# 7x7RGB-IR-J010129A.net
KiCad netlist of a schematic drawn in EAGLE
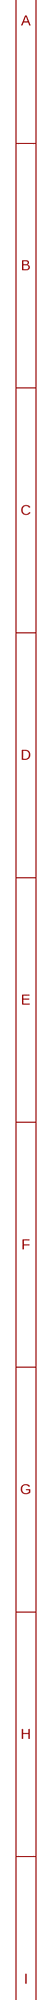
[diagram p0: schematic, sheet 1, part 1 of 2]
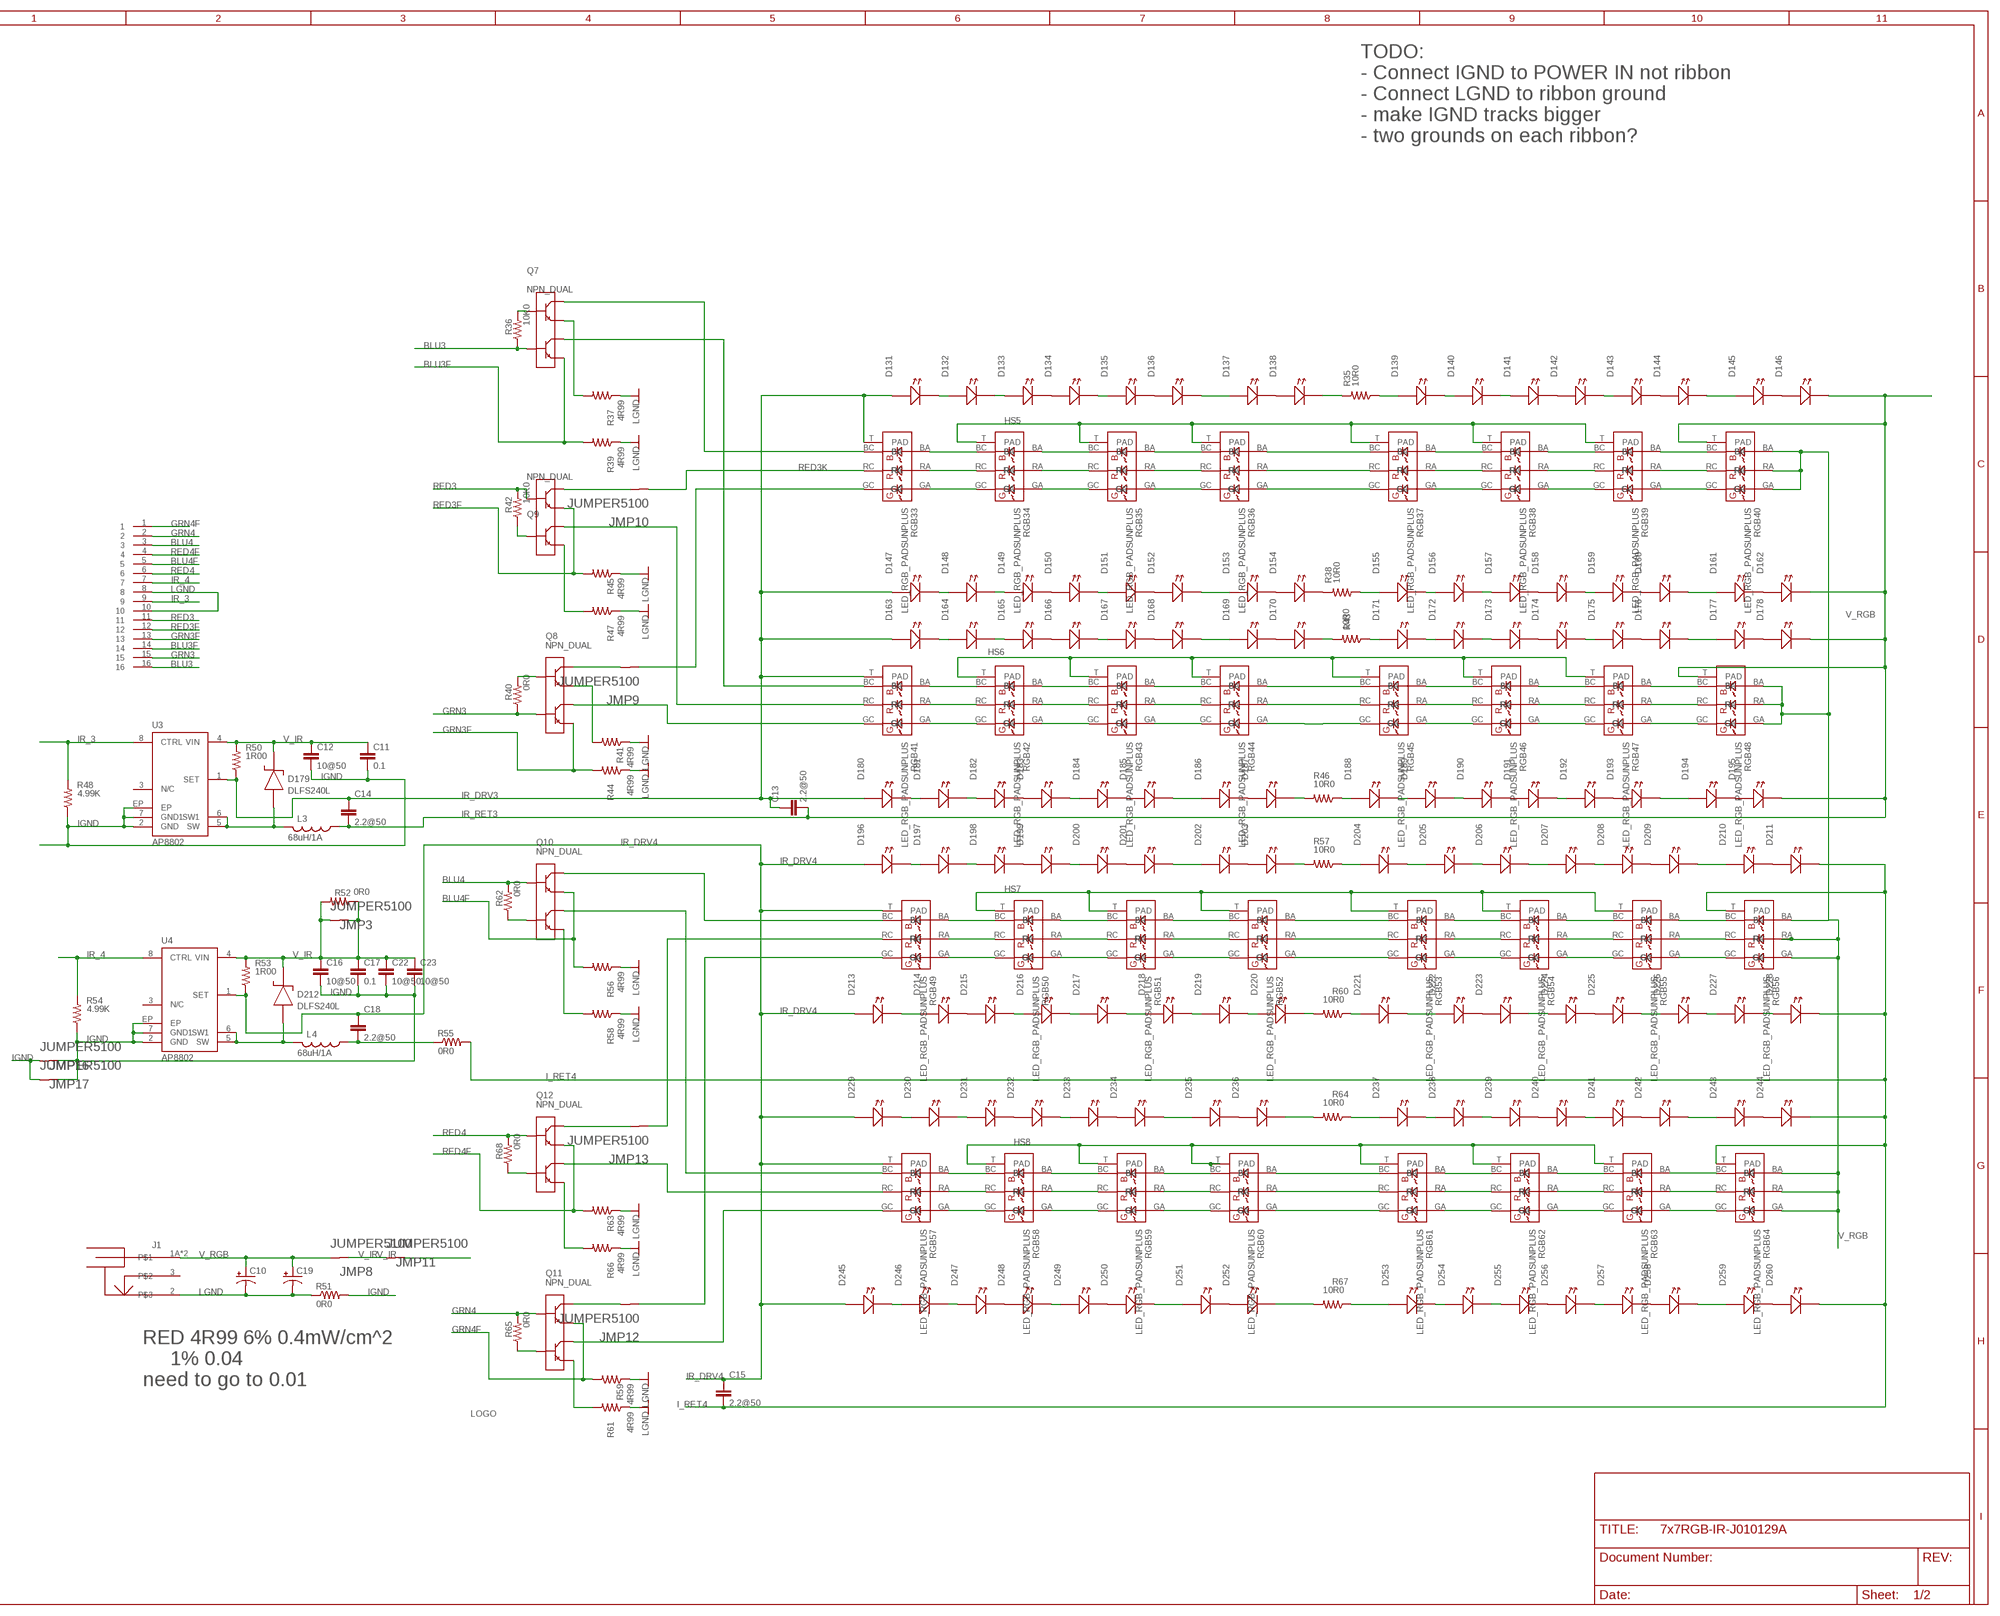
[diagram p1: schematic, sheet 1, part 2 of 2]
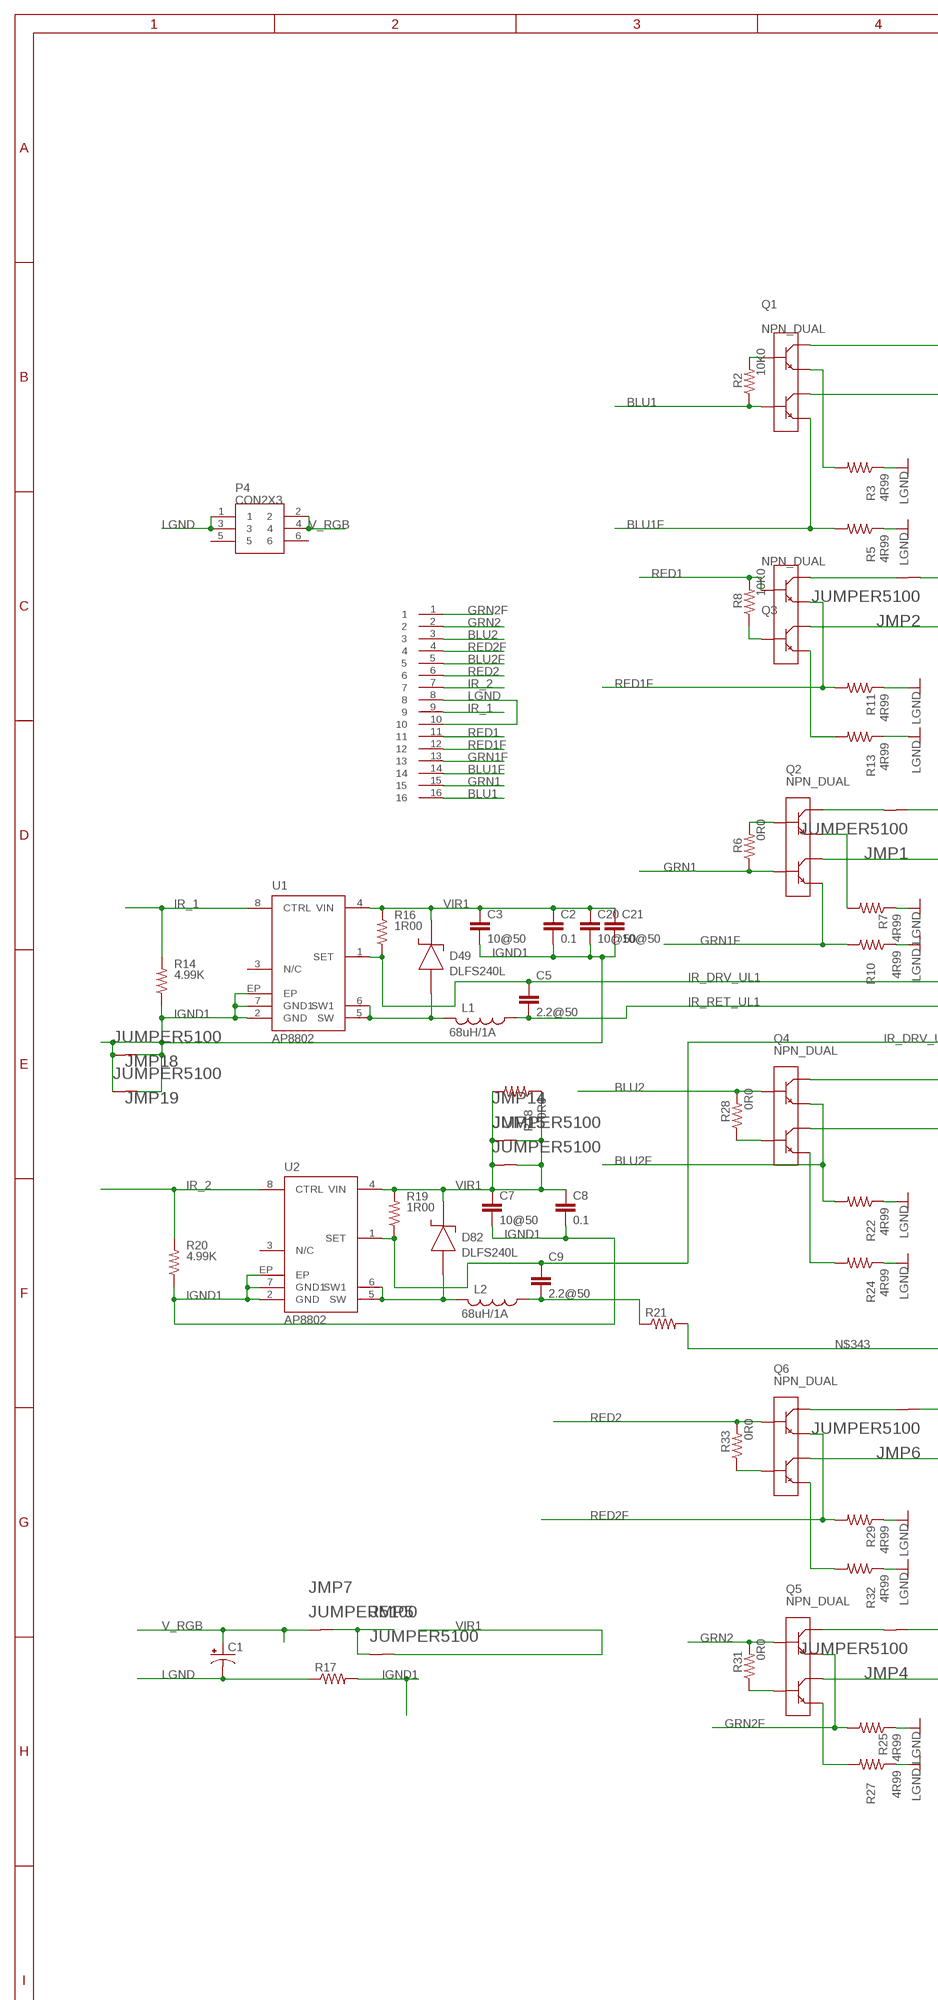
[diagram p2: schematic, sheet 2, part 1 of 2]
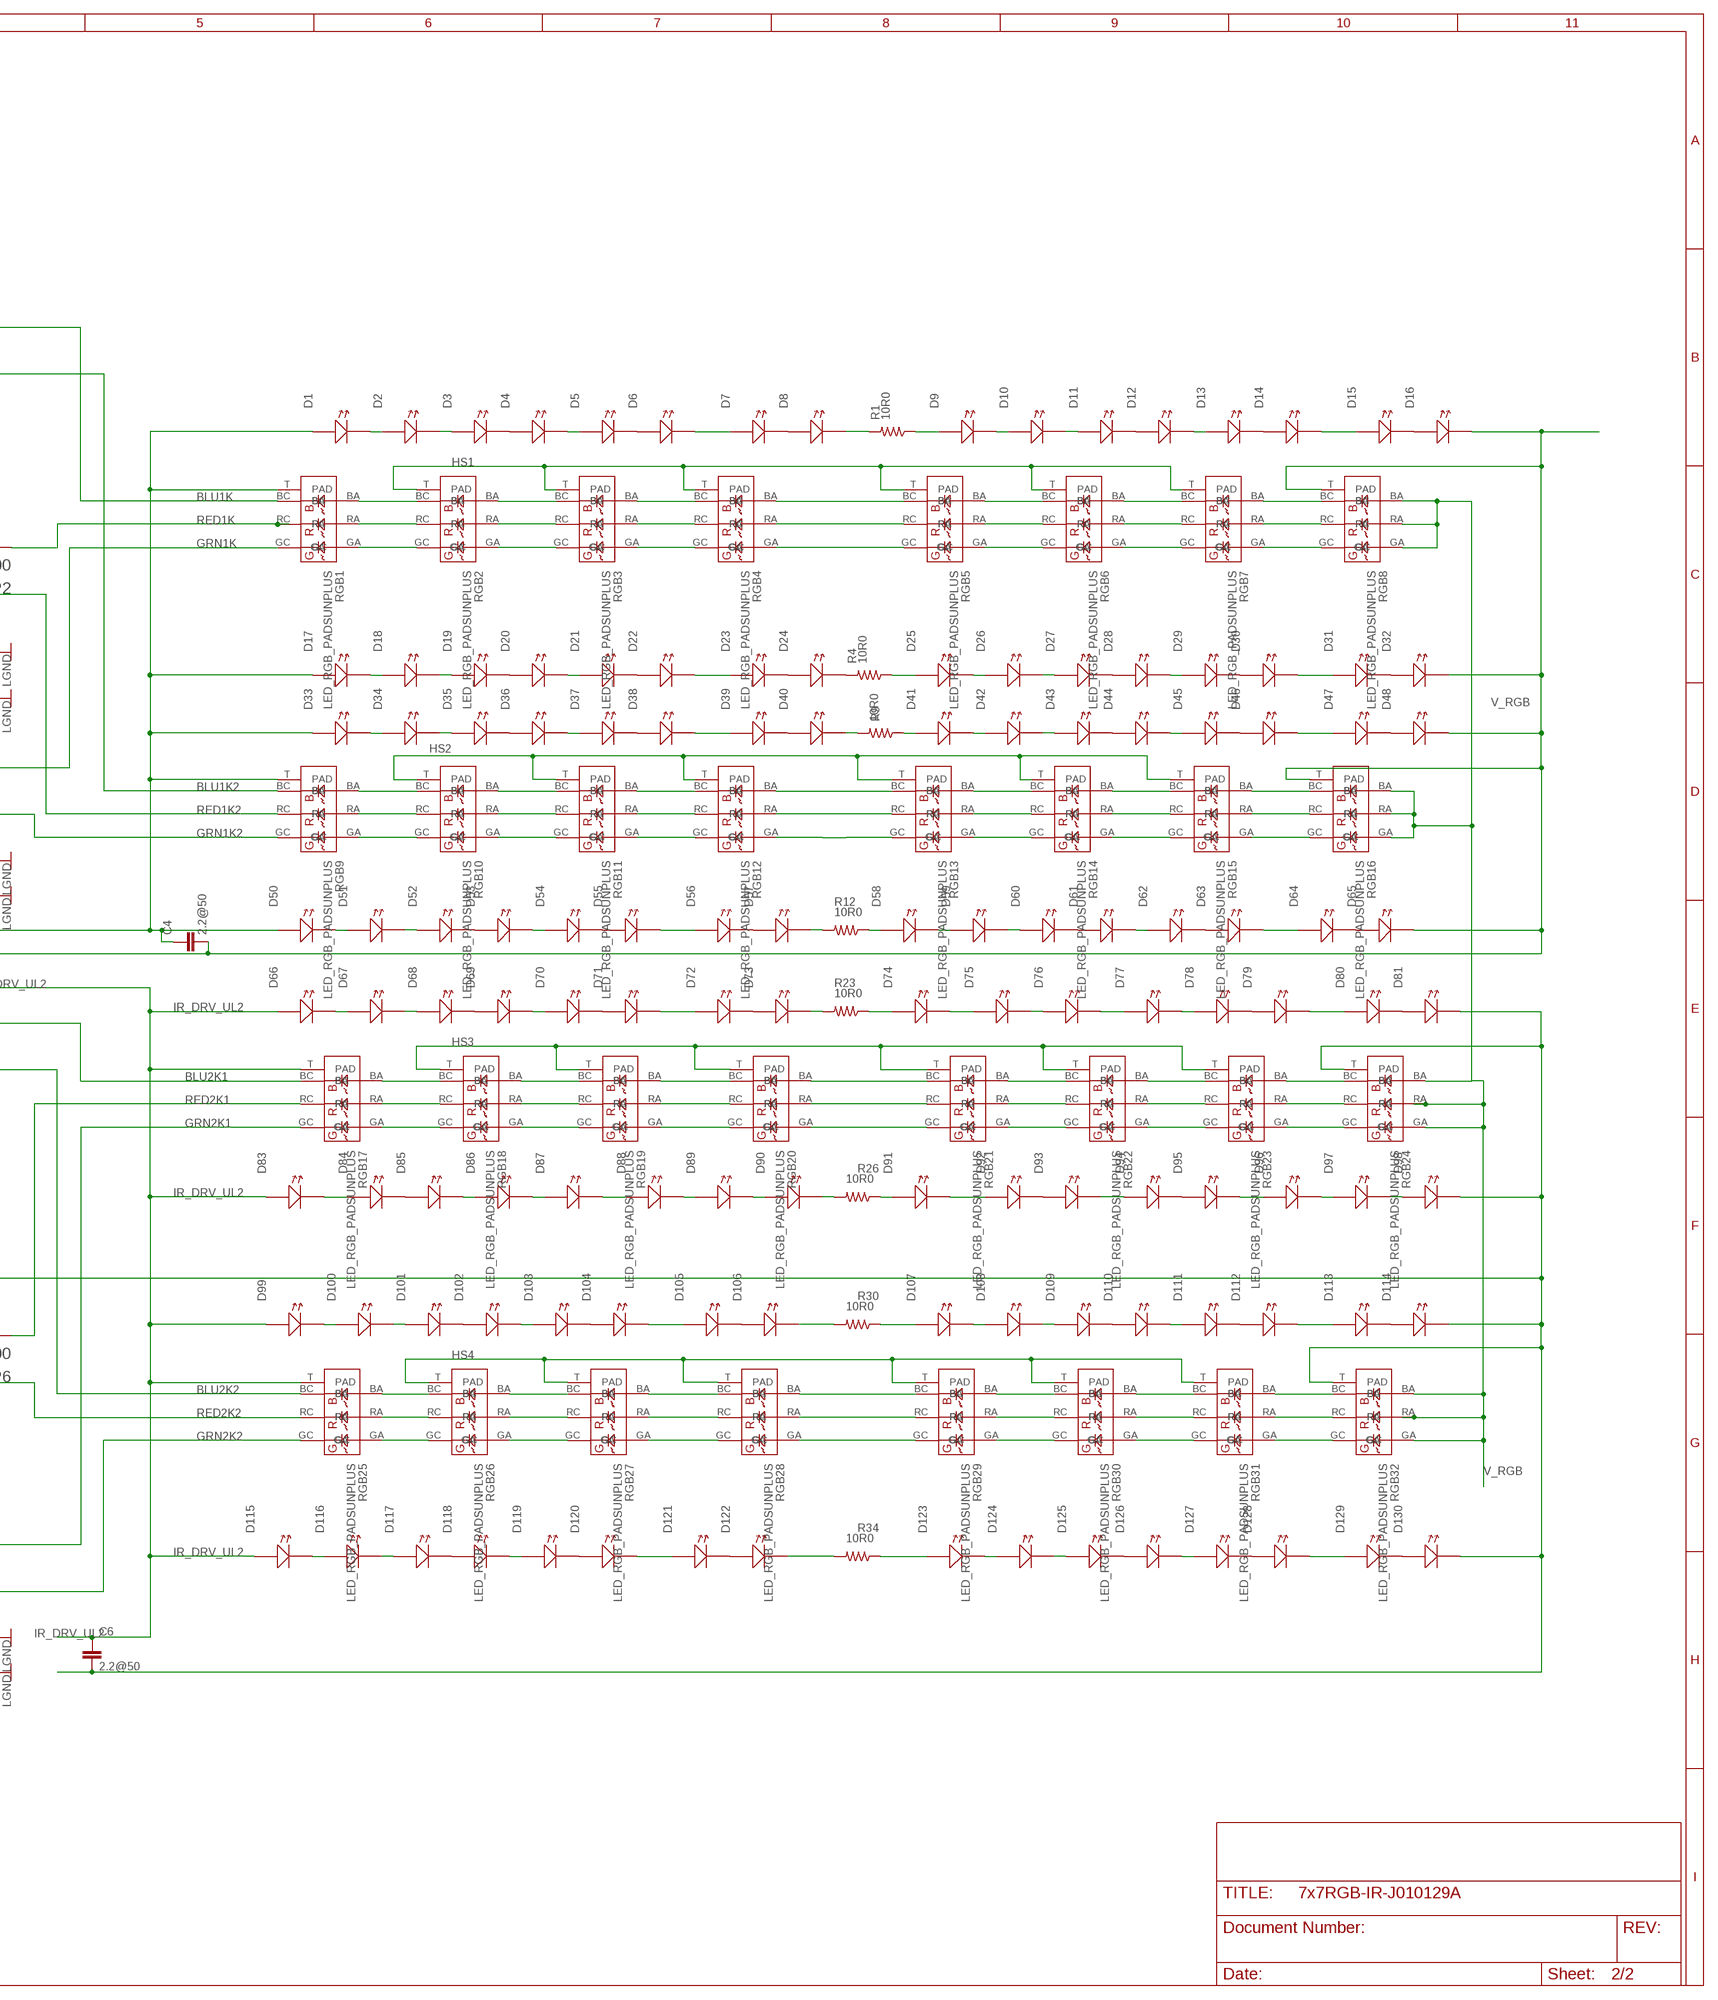
[diagram p3: schematic, sheet 2, part 2 of 2]

(export (version "E")
  (design (tool "Eeschema 10.0.6"))
  (components
    (comp (ref "C1")
      (value "CPOL-US153CLV-0810")
      (footprint "eagle-import:153CLV-0810")
      (libsource (lib "eagle-import") (part "CPOL-US153CLV-0810"))
    )
    (comp (ref "C2")
      (value "0.1")
      (footprint "eagle-import:0805S")
      (libsource (lib "eagle-import") (part "CAPS0805S"))
    )
    (comp (ref "C3")
      (value "10@50")
      (footprint "eagle-import:1210S")
      (libsource (lib "eagle-import") (part "CAPS1210S"))
    )
    (comp (ref "C4")
      (value "2.2@50")
      (footprint "eagle-import:1206S")
      (libsource (lib "eagle-import") (part "CAPS1206S"))
    )
    (comp (ref "C5")
      (value "2.2@50")
      (footprint "eagle-import:1206S")
      (libsource (lib "eagle-import") (part "CAPS1206S"))
    )
    (comp (ref "C6")
      (value "2.2@50")
      (footprint "eagle-import:1206S")
      (libsource (lib "eagle-import") (part "CAPS1206S"))
    )
    (comp (ref "C7")
      (value "10@50")
      (footprint "eagle-import:1210S")
      (libsource (lib "eagle-import") (part "CAPS1210S"))
    )
    (comp (ref "C8")
      (value "0.1")
      (footprint "eagle-import:0805S")
      (libsource (lib "eagle-import") (part "CAPS0805S"))
    )
    (comp (ref "C9")
      (value "2.2@50")
      (footprint "eagle-import:1206S")
      (libsource (lib "eagle-import") (part "CAPS1206S"))
    )
    (comp (ref "C20")
      (value "10@50")
      (footprint "eagle-import:1210S")
      (libsource (lib "eagle-import") (part "CAPS1210S"))
    )
    (comp (ref "C21")
      (value "10@50")
      (footprint "eagle-import:1210S")
      (libsource (lib "eagle-import") (part "CAPS1210S"))
    )
    (comp (ref "D1")
      (value "LEDLED_SFH4050")
      (footprint "eagle-import:LED_SFH4050")
      (libsource (lib "eagle-import") (part "LEDLED_SFH4050"))
    )
    (comp (ref "D2")
      (value "LEDLED_SFH4050")
      (footprint "eagle-import:LED_SFH4050")
      (libsource (lib "eagle-import") (part "LEDLED_SFH4050"))
    )
    (comp (ref "D3")
      (value "LEDLED_SFH4050")
      (footprint "eagle-import:LED_SFH4050")
      (libsource (lib "eagle-import") (part "LEDLED_SFH4050"))
    )
    (comp (ref "D4")
      (value "LEDLED_SFH4050")
      (footprint "eagle-import:LED_SFH4050")
      (libsource (lib "eagle-import") (part "LEDLED_SFH4050"))
    )
    (comp (ref "D5")
      (value "LEDLED_SFH4050")
      (footprint "eagle-import:LED_SFH4050")
      (libsource (lib "eagle-import") (part "LEDLED_SFH4050"))
    )
    (comp (ref "D6")
      (value "LEDLED_SFH4050")
      (footprint "eagle-import:LED_SFH4050")
      (libsource (lib "eagle-import") (part "LEDLED_SFH4050"))
    )
    (comp (ref "D7")
      (value "LEDLED_SFH4050")
      (footprint "eagle-import:LED_SFH4050")
      (libsource (lib "eagle-import") (part "LEDLED_SFH4050"))
    )
    (comp (ref "D8")
      (value "LEDLED_SFH4050")
      (footprint "eagle-import:LED_SFH4050")
      (libsource (lib "eagle-import") (part "LEDLED_SFH4050"))
    )
    (comp (ref "D9")
      (value "LEDLED_SFH4050")
      (footprint "eagle-import:LED_SFH4050")
      (libsource (lib "eagle-import") (part "LEDLED_SFH4050"))
    )
    (comp (ref "D10")
      (value "LEDLED_SFH4050")
      (footprint "eagle-import:LED_SFH4050")
      (libsource (lib "eagle-import") (part "LEDLED_SFH4050"))
    )
    (comp (ref "D11")
      (value "LEDLED_SFH4050")
      (footprint "eagle-import:LED_SFH4050")
      (libsource (lib "eagle-import") (part "LEDLED_SFH4050"))
    )
    (comp (ref "D12")
      (value "LEDLED_SFH4050")
      (footprint "eagle-import:LED_SFH4050")
      (libsource (lib "eagle-import") (part "LEDLED_SFH4050"))
    )
    (comp (ref "D13")
      (value "LEDLED_SFH4050")
      (footprint "eagle-import:LED_SFH4050")
      (libsource (lib "eagle-import") (part "LEDLED_SFH4050"))
    )
    (comp (ref "D14")
      (value "LEDLED_SFH4050")
      (footprint "eagle-import:LED_SFH4050")
      (libsource (lib "eagle-import") (part "LEDLED_SFH4050"))
    )
    (comp (ref "D15")
      (value "LEDLED_SFH4050")
      (footprint "eagle-import:LED_SFH4050")
      (libsource (lib "eagle-import") (part "LEDLED_SFH4050"))
    )
    (comp (ref "D16")
      (value "LEDLED_SFH4050")
      (footprint "eagle-import:LED_SFH4050")
      (libsource (lib "eagle-import") (part "LEDLED_SFH4050"))
    )
    (comp (ref "D17")
      (value "LEDLED_SFH4050")
      (footprint "eagle-import:LED_SFH4050")
      (libsource (lib "eagle-import") (part "LEDLED_SFH4050"))
    )
    (comp (ref "D18")
      (value "LEDLED_SFH4050")
      (footprint "eagle-import:LED_SFH4050")
      (libsource (lib "eagle-import") (part "LEDLED_SFH4050"))
    )
    (comp (ref "D19")
      (value "LEDLED_SFH4050")
      (footprint "eagle-import:LED_SFH4050")
      (libsource (lib "eagle-import") (part "LEDLED_SFH4050"))
    )
    (comp (ref "D20")
      (value "LEDLED_SFH4050")
      (footprint "eagle-import:LED_SFH4050")
      (libsource (lib "eagle-import") (part "LEDLED_SFH4050"))
    )
    (comp (ref "D21")
      (value "LEDLED_SFH4050")
      (footprint "eagle-import:LED_SFH4050")
      (libsource (lib "eagle-import") (part "LEDLED_SFH4050"))
    )
    (comp (ref "D22")
      (value "LEDLED_SFH4050")
      (footprint "eagle-import:LED_SFH4050")
      (libsource (lib "eagle-import") (part "LEDLED_SFH4050"))
    )
    (comp (ref "D23")
      (value "LEDLED_SFH4050")
      (footprint "eagle-import:LED_SFH4050")
      (libsource (lib "eagle-import") (part "LEDLED_SFH4050"))
    )
    (comp (ref "D24")
      (value "LEDLED_SFH4050")
      (footprint "eagle-import:LED_SFH4050")
      (libsource (lib "eagle-import") (part "LEDLED_SFH4050"))
    )
    (comp (ref "D25")
      (value "LEDLED_SFH4050")
      (footprint "eagle-import:LED_SFH4050")
      (libsource (lib "eagle-import") (part "LEDLED_SFH4050"))
    )
    (comp (ref "D26")
      (value "LEDLED_SFH4050")
      (footprint "eagle-import:LED_SFH4050")
      (libsource (lib "eagle-import") (part "LEDLED_SFH4050"))
    )
    (comp (ref "D27")
      (value "LEDLED_SFH4050")
      (footprint "eagle-import:LED_SFH4050")
      (libsource (lib "eagle-import") (part "LEDLED_SFH4050"))
    )
    (comp (ref "D28")
      (value "LEDLED_SFH4050")
      (footprint "eagle-import:LED_SFH4050")
      (libsource (lib "eagle-import") (part "LEDLED_SFH4050"))
    )
    (comp (ref "D29")
      (value "LEDLED_SFH4050")
      (footprint "eagle-import:LED_SFH4050")
      (libsource (lib "eagle-import") (part "LEDLED_SFH4050"))
    )
    (comp (ref "D30")
      (value "LEDLED_SFH4050")
      (footprint "eagle-import:LED_SFH4050")
      (libsource (lib "eagle-import") (part "LEDLED_SFH4050"))
    )
    (comp (ref "D31")
      (value "LEDLED_SFH4050")
      (footprint "eagle-import:LED_SFH4050")
      (libsource (lib "eagle-import") (part "LEDLED_SFH4050"))
    )
    (comp (ref "D32")
      (value "LEDLED_SFH4050")
      (footprint "eagle-import:LED_SFH4050")
      (libsource (lib "eagle-import") (part "LEDLED_SFH4050"))
    )
    (comp (ref "D33")
      (value "LEDLED_SFH4050")
      (footprint "eagle-import:LED_SFH4050")
      (libsource (lib "eagle-import") (part "LEDLED_SFH4050"))
    )
    (comp (ref "D34")
      (value "LEDLED_SFH4050")
      (footprint "eagle-import:LED_SFH4050")
      (libsource (lib "eagle-import") (part "LEDLED_SFH4050"))
    )
    (comp (ref "D35")
      (value "LEDLED_SFH4050")
      (footprint "eagle-import:LED_SFH4050")
      (libsource (lib "eagle-import") (part "LEDLED_SFH4050"))
    )
    (comp (ref "D36")
      (value "LEDLED_SFH4050")
      (footprint "eagle-import:LED_SFH4050")
      (libsource (lib "eagle-import") (part "LEDLED_SFH4050"))
    )
    (comp (ref "D37")
      (value "LEDLED_SFH4050")
      (footprint "eagle-import:LED_SFH4050")
      (libsource (lib "eagle-import") (part "LEDLED_SFH4050"))
    )
    (comp (ref "D38")
      (value "LEDLED_SFH4050")
      (footprint "eagle-import:LED_SFH4050")
      (libsource (lib "eagle-import") (part "LEDLED_SFH4050"))
    )
    (comp (ref "D39")
      (value "LEDLED_SFH4050")
      (footprint "eagle-import:LED_SFH4050")
      (libsource (lib "eagle-import") (part "LEDLED_SFH4050"))
    )
    (comp (ref "D40")
      (value "LEDLED_SFH4050")
      (footprint "eagle-import:LED_SFH4050")
      (libsource (lib "eagle-import") (part "LEDLED_SFH4050"))
    )
    (comp (ref "D41")
      (value "LEDLED_SFH4050")
      (footprint "eagle-import:LED_SFH4050")
      (libsource (lib "eagle-import") (part "LEDLED_SFH4050"))
    )
    (comp (ref "D42")
      (value "LEDLED_SFH4050")
      (footprint "eagle-import:LED_SFH4050")
      (libsource (lib "eagle-import") (part "LEDLED_SFH4050"))
    )
    (comp (ref "D43")
      (value "LEDLED_SFH4050")
      (footprint "eagle-import:LED_SFH4050")
      (libsource (lib "eagle-import") (part "LEDLED_SFH4050"))
    )
    (comp (ref "D44")
      (value "LEDLED_SFH4050")
      (footprint "eagle-import:LED_SFH4050")
      (libsource (lib "eagle-import") (part "LEDLED_SFH4050"))
    )
    (comp (ref "D45")
      (value "LEDLED_SFH4050")
      (footprint "eagle-import:LED_SFH4050")
      (libsource (lib "eagle-import") (part "LEDLED_SFH4050"))
    )
    (comp (ref "D46")
      (value "LEDLED_SFH4050")
      (footprint "eagle-import:LED_SFH4050")
      (libsource (lib "eagle-import") (part "LEDLED_SFH4050"))
    )
    (comp (ref "D47")
      (value "LEDLED_SFH4050")
      (footprint "eagle-import:LED_SFH4050")
      (libsource (lib "eagle-import") (part "LEDLED_SFH4050"))
    )
    (comp (ref "D48")
      (value "LEDLED_SFH4050")
      (footprint "eagle-import:LED_SFH4050")
      (libsource (lib "eagle-import") (part "LEDLED_SFH4050"))
    )
    (comp (ref "D49")
      (value "DLFS240L")
      (footprint "eagle-import:PWRDI-123")
      (libsource (lib "eagle-import") (part "DIODE_SCHOTTKYPWRDI-123"))
    )
    (comp (ref "D50")
      (value "LEDLED_SFH4050")
      (footprint "eagle-import:LED_SFH4050")
      (libsource (lib "eagle-import") (part "LEDLED_SFH4050"))
    )
    (comp (ref "D51")
      (value "LEDLED_SFH4050")
      (footprint "eagle-import:LED_SFH4050")
      (libsource (lib "eagle-import") (part "LEDLED_SFH4050"))
    )
    (comp (ref "D52")
      (value "LEDLED_SFH4050")
      (footprint "eagle-import:LED_SFH4050")
      (libsource (lib "eagle-import") (part "LEDLED_SFH4050"))
    )
    (comp (ref "D53")
      (value "LEDLED_SFH4050")
      (footprint "eagle-import:LED_SFH4050")
      (libsource (lib "eagle-import") (part "LEDLED_SFH4050"))
    )
    (comp (ref "D54")
      (value "LEDLED_SFH4050")
      (footprint "eagle-import:LED_SFH4050")
      (libsource (lib "eagle-import") (part "LEDLED_SFH4050"))
    )
    (comp (ref "D55")
      (value "LEDLED_SFH4050")
      (footprint "eagle-import:LED_SFH4050")
      (libsource (lib "eagle-import") (part "LEDLED_SFH4050"))
    )
    (comp (ref "D56")
      (value "LEDLED_SFH4050")
      (footprint "eagle-import:LED_SFH4050")
      (libsource (lib "eagle-import") (part "LEDLED_SFH4050"))
    )
    (comp (ref "D57")
      (value "LEDLED_SFH4050")
      (footprint "eagle-import:LED_SFH4050")
      (libsource (lib "eagle-import") (part "LEDLED_SFH4050"))
    )
    (comp (ref "D58")
      (value "LEDLED_SFH4050")
      (footprint "eagle-import:LED_SFH4050")
      (libsource (lib "eagle-import") (part "LEDLED_SFH4050"))
    )
    (comp (ref "D59")
      (value "LEDLED_SFH4050")
      (footprint "eagle-import:LED_SFH4050")
      (libsource (lib "eagle-import") (part "LEDLED_SFH4050"))
    )
    (comp (ref "D60")
      (value "LEDLED_SFH4050")
      (footprint "eagle-import:LED_SFH4050")
      (libsource (lib "eagle-import") (part "LEDLED_SFH4050"))
    )
    (comp (ref "D61")
      (value "LEDLED_SFH4050")
      (footprint "eagle-import:LED_SFH4050")
      (libsource (lib "eagle-import") (part "LEDLED_SFH4050"))
    )
    (comp (ref "D62")
      (value "LEDLED_SFH4050")
      (footprint "eagle-import:LED_SFH4050")
      (libsource (lib "eagle-import") (part "LEDLED_SFH4050"))
    )
    (comp (ref "D63")
      (value "LEDLED_SFH4050")
      (footprint "eagle-import:LED_SFH4050")
      (libsource (lib "eagle-import") (part "LEDLED_SFH4050"))
    )
    (comp (ref "D64")
      (value "LEDLED_SFH4050")
      (footprint "eagle-import:LED_SFH4050")
      (libsource (lib "eagle-import") (part "LEDLED_SFH4050"))
    )
    (comp (ref "D65")
      (value "LEDLED_SFH4050")
      (footprint "eagle-import:LED_SFH4050")
      (libsource (lib "eagle-import") (part "LEDLED_SFH4050"))
    )
    (comp (ref "D66")
      (value "LEDLED_SFH4050")
      (footprint "eagle-import:LED_SFH4050")
      (libsource (lib "eagle-import") (part "LEDLED_SFH4050"))
    )
    (comp (ref "D67")
      (value "LEDLED_SFH4050")
      (footprint "eagle-import:LED_SFH4050")
      (libsource (lib "eagle-import") (part "LEDLED_SFH4050"))
    )
    (comp (ref "D68")
      (value "LEDLED_SFH4050")
      (footprint "eagle-import:LED_SFH4050")
      (libsource (lib "eagle-import") (part "LEDLED_SFH4050"))
    )
    (comp (ref "D69")
      (value "LEDLED_SFH4050")
      (footprint "eagle-import:LED_SFH4050")
      (libsource (lib "eagle-import") (part "LEDLED_SFH4050"))
    )
    (comp (ref "D70")
      (value "LEDLED_SFH4050")
      (footprint "eagle-import:LED_SFH4050")
      (libsource (lib "eagle-import") (part "LEDLED_SFH4050"))
    )
    (comp (ref "D71")
      (value "LEDLED_SFH4050")
      (footprint "eagle-import:LED_SFH4050")
      (libsource (lib "eagle-import") (part "LEDLED_SFH4050"))
    )
    (comp (ref "D72")
      (value "LEDLED_SFH4050")
      (footprint "eagle-import:LED_SFH4050")
      (libsource (lib "eagle-import") (part "LEDLED_SFH4050"))
    )
    (comp (ref "D73")
      (value "LEDLED_SFH4050")
      (footprint "eagle-import:LED_SFH4050")
      (libsource (lib "eagle-import") (part "LEDLED_SFH4050"))
    )
    (comp (ref "D74")
      (value "LEDLED_SFH4050")
      (footprint "eagle-import:LED_SFH4050")
      (libsource (lib "eagle-import") (part "LEDLED_SFH4050"))
    )
    (comp (ref "D75")
      (value "LEDLED_SFH4050")
      (footprint "eagle-import:LED_SFH4050")
      (libsource (lib "eagle-import") (part "LEDLED_SFH4050"))
    )
    (comp (ref "D76")
      (value "LEDLED_SFH4050")
      (footprint "eagle-import:LED_SFH4050")
      (libsource (lib "eagle-import") (part "LEDLED_SFH4050"))
    )
    (comp (ref "D77")
      (value "LEDLED_SFH4050")
      (footprint "eagle-import:LED_SFH4050")
      (libsource (lib "eagle-import") (part "LEDLED_SFH4050"))
    )
    (comp (ref "D78")
      (value "LEDLED_SFH4050")
      (footprint "eagle-import:LED_SFH4050")
      (libsource (lib "eagle-import") (part "LEDLED_SFH4050"))
    )
    (comp (ref "D79")
      (value "LEDLED_SFH4050")
      (footprint "eagle-import:LED_SFH4050")
      (libsource (lib "eagle-import") (part "LEDLED_SFH4050"))
    )
    (comp (ref "D80")
      (value "LEDLED_SFH4050")
      (footprint "eagle-import:LED_SFH4050")
      (libsource (lib "eagle-import") (part "LEDLED_SFH4050"))
    )
    (comp (ref "D81")
      (value "LEDLED_SFH4050")
      (footprint "eagle-import:LED_SFH4050")
      (libsource (lib "eagle-import") (part "LEDLED_SFH4050"))
    )
    (comp (ref "D82")
      (value "DLFS240L")
      (footprint "eagle-import:PWRDI-123")
      (libsource (lib "eagle-import") (part "DIODE_SCHOTTKYPWRDI-123"))
    )
    (comp (ref "D83")
      (value "LEDLED_SFH4050")
      (footprint "eagle-import:LED_SFH4050")
      (libsource (lib "eagle-import") (part "LEDLED_SFH4050"))
    )
    (comp (ref "D84")
      (value "LEDLED_SFH4050")
      (footprint "eagle-import:LED_SFH4050")
      (libsource (lib "eagle-import") (part "LEDLED_SFH4050"))
    )
    (comp (ref "D85")
      (value "LEDLED_SFH4050")
      (footprint "eagle-import:LED_SFH4050")
      (libsource (lib "eagle-import") (part "LEDLED_SFH4050"))
    )
    (comp (ref "D86")
      (value "LEDLED_SFH4050")
      (footprint "eagle-import:LED_SFH4050")
      (libsource (lib "eagle-import") (part "LEDLED_SFH4050"))
    )
    (comp (ref "D87")
      (value "LEDLED_SFH4050")
      (footprint "eagle-import:LED_SFH4050")
      (libsource (lib "eagle-import") (part "LEDLED_SFH4050"))
    )
    (comp (ref "D88")
      (value "LEDLED_SFH4050")
      (footprint "eagle-import:LED_SFH4050")
      (libsource (lib "eagle-import") (part "LEDLED_SFH4050"))
    )
    (comp (ref "D89")
      (value "LEDLED_SFH4050")
      (footprint "eagle-import:LED_SFH4050")
      (libsource (lib "eagle-import") (part "LEDLED_SFH4050"))
    )
    (comp (ref "D90")
      (value "LEDLED_SFH4050")
      (footprint "eagle-import:LED_SFH4050")
      (libsource (lib "eagle-import") (part "LEDLED_SFH4050"))
    )
    (comp (ref "D91")
      (value "LEDLED_SFH4050")
      (footprint "eagle-import:LED_SFH4050")
      (libsource (lib "eagle-import") (part "LEDLED_SFH4050"))
    )
    (comp (ref "D92")
      (value "LEDLED_SFH4050")
      (footprint "eagle-import:LED_SFH4050")
      (libsource (lib "eagle-import") (part "LEDLED_SFH4050"))
    )
    (comp (ref "D93")
      (value "LEDLED_SFH4050")
      (footprint "eagle-import:LED_SFH4050")
      (libsource (lib "eagle-import") (part "LEDLED_SFH4050"))
    )
    (comp (ref "D94")
      (value "LEDLED_SFH4050")
      (footprint "eagle-import:LED_SFH4050")
      (libsource (lib "eagle-import") (part "LEDLED_SFH4050"))
    )
    (comp (ref "D95")
      (value "LEDLED_SFH4050")
      (footprint "eagle-import:LED_SFH4050")
      (libsource (lib "eagle-import") (part "LEDLED_SFH4050"))
    )
    (comp (ref "D96")
      (value "LEDLED_SFH4050")
      (footprint "eagle-import:LED_SFH4050")
      (libsource (lib "eagle-import") (part "LEDLED_SFH4050"))
    )
    (comp (ref "D97")
      (value "LEDLED_SFH4050")
      (footprint "eagle-import:LED_SFH4050")
      (libsource (lib "eagle-import") (part "LEDLED_SFH4050"))
    )
    (comp (ref "D98")
      (value "LEDLED_SFH4050")
      (footprint "eagle-import:LED_SFH4050")
      (libsource (lib "eagle-import") (part "LEDLED_SFH4050"))
    )
    (comp (ref "D99")
      (value "LEDLED_SFH4050")
      (footprint "eagle-import:LED_SFH4050")
      (libsource (lib "eagle-import") (part "LEDLED_SFH4050"))
    )
    (comp (ref "D100")
      (value "LEDLED_SFH4050")
      (footprint "eagle-import:LED_SFH4050")
      (libsource (lib "eagle-import") (part "LEDLED_SFH4050"))
    )
    (comp (ref "D101")
      (value "LEDLED_SFH4050")
      (footprint "eagle-import:LED_SFH4050")
      (libsource (lib "eagle-import") (part "LEDLED_SFH4050"))
    )
    (comp (ref "D102")
      (value "LEDLED_SFH4050")
      (footprint "eagle-import:LED_SFH4050")
      (libsource (lib "eagle-import") (part "LEDLED_SFH4050"))
    )
    (comp (ref "D103")
      (value "LEDLED_SFH4050")
      (footprint "eagle-import:LED_SFH4050")
      (libsource (lib "eagle-import") (part "LEDLED_SFH4050"))
    )
    (comp (ref "D104")
      (value "LEDLED_SFH4050")
      (footprint "eagle-import:LED_SFH4050")
      (libsource (lib "eagle-import") (part "LEDLED_SFH4050"))
    )
    (comp (ref "D105")
      (value "LEDLED_SFH4050")
      (footprint "eagle-import:LED_SFH4050")
      (libsource (lib "eagle-import") (part "LEDLED_SFH4050"))
    )
    (comp (ref "D106")
      (value "LEDLED_SFH4050")
      (footprint "eagle-import:LED_SFH4050")
      (libsource (lib "eagle-import") (part "LEDLED_SFH4050"))
    )
    (comp (ref "D107")
      (value "LEDLED_SFH4050")
      (footprint "eagle-import:LED_SFH4050")
      (libsource (lib "eagle-import") (part "LEDLED_SFH4050"))
    )
    (comp (ref "D108")
      (value "LEDLED_SFH4050")
      (footprint "eagle-import:LED_SFH4050")
      (libsource (lib "eagle-import") (part "LEDLED_SFH4050"))
    )
    (comp (ref "D109")
      (value "LEDLED_SFH4050")
      (footprint "eagle-import:LED_SFH4050")
      (libsource (lib "eagle-import") (part "LEDLED_SFH4050"))
    )
    (comp (ref "D110")
      (value "LEDLED_SFH4050")
      (footprint "eagle-import:LED_SFH4050")
      (libsource (lib "eagle-import") (part "LEDLED_SFH4050"))
    )
    (comp (ref "D111")
      (value "LEDLED_SFH4050")
      (footprint "eagle-import:LED_SFH4050")
      (libsource (lib "eagle-import") (part "LEDLED_SFH4050"))
    )
    (comp (ref "D112")
      (value "LEDLED_SFH4050")
      (footprint "eagle-import:LED_SFH4050")
      (libsource (lib "eagle-import") (part "LEDLED_SFH4050"))
    )
    (comp (ref "D113")
      (value "LEDLED_SFH4050")
      (footprint "eagle-import:LED_SFH4050")
      (libsource (lib "eagle-import") (part "LEDLED_SFH4050"))
    )
    (comp (ref "D114")
      (value "LEDLED_SFH4050")
      (footprint "eagle-import:LED_SFH4050")
      (libsource (lib "eagle-import") (part "LEDLED_SFH4050"))
    )
    (comp (ref "D115")
      (value "LEDLED_SFH4050")
      (footprint "eagle-import:LED_SFH4050")
      (libsource (lib "eagle-import") (part "LEDLED_SFH4050"))
    )
    (comp (ref "D116")
      (value "LEDLED_SFH4050")
      (footprint "eagle-import:LED_SFH4050")
      (libsource (lib "eagle-import") (part "LEDLED_SFH4050"))
    )
    (comp (ref "D117")
      (value "LEDLED_SFH4050")
      (footprint "eagle-import:LED_SFH4050")
      (libsource (lib "eagle-import") (part "LEDLED_SFH4050"))
    )
    (comp (ref "D118")
      (value "LEDLED_SFH4050")
      (footprint "eagle-import:LED_SFH4050")
      (libsource (lib "eagle-import") (part "LEDLED_SFH4050"))
    )
    (comp (ref "D119")
      (value "LEDLED_SFH4050")
      (footprint "eagle-import:LED_SFH4050")
      (libsource (lib "eagle-import") (part "LEDLED_SFH4050"))
    )
    (comp (ref "D120")
      (value "LEDLED_SFH4050")
      (footprint "eagle-import:LED_SFH4050")
      (libsource (lib "eagle-import") (part "LEDLED_SFH4050"))
    )
    (comp (ref "D121")
      (value "LEDLED_SFH4050")
      (footprint "eagle-import:LED_SFH4050")
      (libsource (lib "eagle-import") (part "LEDLED_SFH4050"))
    )
    (comp (ref "D122")
      (value "LEDLED_SFH4050")
      (footprint "eagle-import:LED_SFH4050")
      (libsource (lib "eagle-import") (part "LEDLED_SFH4050"))
    )
    (comp (ref "D123")
      (value "LEDLED_SFH4050")
      (footprint "eagle-import:LED_SFH4050")
      (libsource (lib "eagle-import") (part "LEDLED_SFH4050"))
    )
    (comp (ref "D124")
      (value "LEDLED_SFH4050")
      (footprint "eagle-import:LED_SFH4050")
      (libsource (lib "eagle-import") (part "LEDLED_SFH4050"))
    )
    (comp (ref "D125")
      (value "LEDLED_SFH4050")
      (footprint "eagle-import:LED_SFH4050")
      (libsource (lib "eagle-import") (part "LEDLED_SFH4050"))
    )
    (comp (ref "D126")
      (value "LEDLED_SFH4050")
      (footprint "eagle-import:LED_SFH4050")
      (libsource (lib "eagle-import") (part "LEDLED_SFH4050"))
    )
    (comp (ref "D127")
      (value "LEDLED_SFH4050")
      (footprint "eagle-import:LED_SFH4050")
      (libsource (lib "eagle-import") (part "LEDLED_SFH4050"))
    )
    (comp (ref "D128")
      (value "LEDLED_SFH4050")
      (footprint "eagle-import:LED_SFH4050")
      (libsource (lib "eagle-import") (part "LEDLED_SFH4050"))
    )
    (comp (ref "D129")
      (value "LEDLED_SFH4050")
      (footprint "eagle-import:LED_SFH4050")
      (libsource (lib "eagle-import") (part "LEDLED_SFH4050"))
    )
    (comp (ref "D130")
      (value "LEDLED_SFH4050")
      (footprint "eagle-import:LED_SFH4050")
      (libsource (lib "eagle-import") (part "LEDLED_SFH4050"))
    )
    (comp (ref "JMP1")
      (value "JUMPER5100")
      (footprint "eagle-import:5100")
      (libsource (lib "eagle-import") (part "JUMPER5100"))
    )
    (comp (ref "JMP2")
      (value "JUMPER5100")
      (footprint "eagle-import:5100")
      (libsource (lib "eagle-import") (part "JUMPER5100"))
    )
    (comp (ref "JMP4")
      (value "JUMPER5100")
      (footprint "eagle-import:5100")
      (libsource (lib "eagle-import") (part "JUMPER5100"))
    )
    (comp (ref "JMP5")
      (value "JUMPER5100")
      (footprint "eagle-import:5100")
      (libsource (lib "eagle-import") (part "JUMPER5100"))
    )
    (comp (ref "JMP6")
      (value "JUMPER5100")
      (footprint "eagle-import:5100")
      (libsource (lib "eagle-import") (part "JUMPER5100"))
    )
    (comp (ref "JMP7")
      (value "JUMPER5100")
      (footprint "eagle-import:5100")
      (libsource (lib "eagle-import") (part "JUMPER5100"))
    )
    (comp (ref "JMP14")
      (value "JUMPER5100")
      (footprint "eagle-import:5100")
      (libsource (lib "eagle-import") (part "JUMPER5100"))
    )
    (comp (ref "JMP15")
      (value "JUMPER5100")
      (footprint "eagle-import:5100")
      (libsource (lib "eagle-import") (part "JUMPER5100"))
    )
    (comp (ref "JMP18")
      (value "JUMPER5100")
      (footprint "eagle-import:5100")
      (libsource (lib "eagle-import") (part "JUMPER5100"))
    )
    (comp (ref "JMP19")
      (value "JUMPER5100")
      (footprint "eagle-import:5100")
      (libsource (lib "eagle-import") (part "JUMPER5100"))
    )
    (comp (ref "L1")
      (value "68uH/1A")
      (footprint "eagle-import:SRU8043")
      (libsource (lib "eagle-import") (part "INDUCTOR_SMSRU8043"))
    )
    (comp (ref "L2")
      (value "68uH/1A")
      (footprint "eagle-import:SRU8043")
      (libsource (lib "eagle-import") (part "INDUCTOR_SMSRU8043"))
    )
    (comp (ref "P1")
      (value "CON162X8SM-SMALL")
      (footprint "eagle-import:HEADER2X8_SM_SMALL")
      (libsource (lib "eagle-import") (part "CON162X8SM-SMALL"))
    )
    (comp (ref "P4")
      (value "CON2X3")
      (footprint "eagle-import:2X3_SHROUDED_SMT")
      (libsource (lib "eagle-import") (part "CON2X3"))
    )
    (comp (ref "Q1")
      (value "NPN_DUAL")
      (footprint "eagle-import:LFPAK56D")
      (libsource (lib "eagle-import") (part "NPN_DUAL"))
    )
    (comp (ref "Q2")
      (value "NPN_DUAL")
      (footprint "eagle-import:LFPAK56D")
      (libsource (lib "eagle-import") (part "NPN_DUAL"))
    )
    (comp (ref "Q3")
      (value "NPN_DUAL")
      (footprint "eagle-import:LFPAK56D")
      (libsource (lib "eagle-import") (part "NPN_DUAL"))
    )
    (comp (ref "Q4")
      (value "NPN_DUAL")
      (footprint "eagle-import:LFPAK56D")
      (libsource (lib "eagle-import") (part "NPN_DUAL"))
    )
    (comp (ref "Q5")
      (value "NPN_DUAL")
      (footprint "eagle-import:LFPAK56D")
      (libsource (lib "eagle-import") (part "NPN_DUAL"))
    )
    (comp (ref "Q6")
      (value "NPN_DUAL")
      (footprint "eagle-import:LFPAK56D")
      (libsource (lib "eagle-import") (part "NPN_DUAL"))
    )
    (comp (ref "R1")
      (value "10R0")
      (footprint "eagle-import:1206S")
      (libsource (lib "eagle-import") (part "RESISTOR_SM1206S"))
    )
    (comp (ref "R2")
      (value "10K0")
      (footprint "eagle-import:1206S")
      (libsource (lib "eagle-import") (part "RESISTOR_SM1206S"))
    )
    (comp (ref "R3")
      (value "4R99")
      (footprint "eagle-import:R2512")
      (libsource (lib "eagle-import") (part "R-US_R2512"))
    )
    (comp (ref "R4")
      (value "10R0")
      (footprint "eagle-import:1206S")
      (libsource (lib "eagle-import") (part "RESISTOR_SM1206S"))
    )
    (comp (ref "R5")
      (value "4R99")
      (footprint "eagle-import:R2512")
      (libsource (lib "eagle-import") (part "R-US_R2512"))
    )
    (comp (ref "R6")
      (value "0R0")
      (footprint "eagle-import:1206S")
      (libsource (lib "eagle-import") (part "RESISTOR_SM1206S"))
    )
    (comp (ref "R7")
      (value "4R99")
      (footprint "eagle-import:R2512")
      (libsource (lib "eagle-import") (part "R-US_R2512"))
    )
    (comp (ref "R8")
      (value "10K0")
      (footprint "eagle-import:1206S")
      (libsource (lib "eagle-import") (part "RESISTOR_SM1206S"))
    )
    (comp (ref "R9")
      (value "10R0")
      (footprint "eagle-import:1206S")
      (libsource (lib "eagle-import") (part "RESISTOR_SM1206S"))
    )
    (comp (ref "R10")
      (value "4R99")
      (footprint "eagle-import:R2512")
      (libsource (lib "eagle-import") (part "R-US_R2512"))
    )
    (comp (ref "R11")
      (value "4R99")
      (footprint "eagle-import:R2512")
      (libsource (lib "eagle-import") (part "R-US_R2512"))
    )
    (comp (ref "R12")
      (value "10R0")
      (footprint "eagle-import:1206S")
      (libsource (lib "eagle-import") (part "RESISTOR_SM1206S"))
    )
    (comp (ref "R13")
      (value "4R99")
      (footprint "eagle-import:R2512")
      (libsource (lib "eagle-import") (part "R-US_R2512"))
    )
    (comp (ref "R14")
      (value "4.99K")
      (footprint "eagle-import:0805S")
      (libsource (lib "eagle-import") (part "RESISTOR_SM0805S"))
    )
    (comp (ref "R16")
      (value "1R00")
      (footprint "eagle-import:1206S")
      (libsource (lib "eagle-import") (part "RESISTOR_SM1206S"))
    )
    (comp (ref "R17")
      (value "RESISTOR_SM1206S")
      (footprint "eagle-import:1206S")
      (libsource (lib "eagle-import") (part "RESISTOR_SM1206S"))
    )
    (comp (ref "R18")
      (value "0R0")
      (footprint "eagle-import:R1206")
      (libsource (lib "eagle-import") (part "R-US_R1206"))
    )
    (comp (ref "R19")
      (value "1R00")
      (footprint "eagle-import:1206S")
      (libsource (lib "eagle-import") (part "RESISTOR_SM1206S"))
    )
    (comp (ref "R20")
      (value "4.99K")
      (footprint "eagle-import:0805S")
      (libsource (lib "eagle-import") (part "RESISTOR_SM0805S"))
    )
    (comp (ref "R21")
      (value "RESISTOR_SM1206S")
      (footprint "eagle-import:1206S")
      (libsource (lib "eagle-import") (part "RESISTOR_SM1206S"))
    )
    (comp (ref "R22")
      (value "4R99")
      (footprint "eagle-import:R2512")
      (libsource (lib "eagle-import") (part "R-US_R2512"))
    )
    (comp (ref "R23")
      (value "10R0")
      (footprint "eagle-import:1206S")
      (libsource (lib "eagle-import") (part "RESISTOR_SM1206S"))
    )
    (comp (ref "R24")
      (value "4R99")
      (footprint "eagle-import:R2512")
      (libsource (lib "eagle-import") (part "R-US_R2512"))
    )
    (comp (ref "R25")
      (value "4R99")
      (footprint "eagle-import:R2512")
      (libsource (lib "eagle-import") (part "R-US_R2512"))
    )
    (comp (ref "R26")
      (value "10R0")
      (footprint "eagle-import:1206S")
      (libsource (lib "eagle-import") (part "RESISTOR_SM1206S"))
    )
    (comp (ref "R27")
      (value "4R99")
      (footprint "eagle-import:R2512")
      (libsource (lib "eagle-import") (part "R-US_R2512"))
    )
    (comp (ref "R28")
      (value "0R0")
      (footprint "eagle-import:1206S")
      (libsource (lib "eagle-import") (part "RESISTOR_SM1206S"))
    )
    (comp (ref "R29")
      (value "4R99")
      (footprint "eagle-import:R2512")
      (libsource (lib "eagle-import") (part "R-US_R2512"))
    )
    (comp (ref "R30")
      (value "10R0")
      (footprint "eagle-import:1206S")
      (libsource (lib "eagle-import") (part "RESISTOR_SM1206S"))
    )
    (comp (ref "R31")
      (value "0R0")
      (footprint "eagle-import:1206S")
      (libsource (lib "eagle-import") (part "RESISTOR_SM1206S"))
    )
    (comp (ref "R32")
      (value "4R99")
      (footprint "eagle-import:R2512")
      (libsource (lib "eagle-import") (part "R-US_R2512"))
    )
    (comp (ref "R33")
      (value "0R0")
      (footprint "eagle-import:1206S")
      (libsource (lib "eagle-import") (part "RESISTOR_SM1206S"))
    )
    (comp (ref "R34")
      (value "10R0")
      (footprint "eagle-import:1206S")
      (libsource (lib "eagle-import") (part "RESISTOR_SM1206S"))
    )
    (comp (ref "RGB1")
      (value "LED_RGB_PADSUNPLUS")
      (footprint "eagle-import:SUNPLUS_RGB")
      (libsource (lib "eagle-import") (part "LED_RGB_PADSUNPLUS"))
    )
    (comp (ref "RGB2")
      (value "LED_RGB_PADSUNPLUS")
      (footprint "eagle-import:SUNPLUS_RGB")
      (libsource (lib "eagle-import") (part "LED_RGB_PADSUNPLUS"))
    )
    (comp (ref "RGB3")
      (value "LED_RGB_PADSUNPLUS")
      (footprint "eagle-import:SUNPLUS_RGB")
      (libsource (lib "eagle-import") (part "LED_RGB_PADSUNPLUS"))
    )
    (comp (ref "RGB4")
      (value "LED_RGB_PADSUNPLUS")
      (footprint "eagle-import:SUNPLUS_RGB")
      (libsource (lib "eagle-import") (part "LED_RGB_PADSUNPLUS"))
    )
    (comp (ref "RGB5")
      (value "LED_RGB_PADSUNPLUS")
      (footprint "eagle-import:SUNPLUS_RGB")
      (libsource (lib "eagle-import") (part "LED_RGB_PADSUNPLUS"))
    )
    (comp (ref "RGB6")
      (value "LED_RGB_PADSUNPLUS")
      (footprint "eagle-import:SUNPLUS_RGB")
      (libsource (lib "eagle-import") (part "LED_RGB_PADSUNPLUS"))
    )
    (comp (ref "RGB7")
      (value "LED_RGB_PADSUNPLUS")
      (footprint "eagle-import:SUNPLUS_RGB")
      (libsource (lib "eagle-import") (part "LED_RGB_PADSUNPLUS"))
    )
    (comp (ref "RGB8")
      (value "LED_RGB_PADSUNPLUS")
      (footprint "eagle-import:SUNPLUS_RGB")
      (libsource (lib "eagle-import") (part "LED_RGB_PADSUNPLUS"))
    )
    (comp (ref "RGB9")
      (value "LED_RGB_PADSUNPLUS")
      (footprint "eagle-import:SUNPLUS_RGB")
      (libsource (lib "eagle-import") (part "LED_RGB_PADSUNPLUS"))
    )
    (comp (ref "RGB10")
      (value "LED_RGB_PADSUNPLUS")
      (footprint "eagle-import:SUNPLUS_RGB")
      (libsource (lib "eagle-import") (part "LED_RGB_PADSUNPLUS"))
    )
    (comp (ref "RGB11")
      (value "LED_RGB_PADSUNPLUS")
      (footprint "eagle-import:SUNPLUS_RGB")
      (libsource (lib "eagle-import") (part "LED_RGB_PADSUNPLUS"))
    )
    (comp (ref "RGB12")
      (value "LED_RGB_PADSUNPLUS")
      (footprint "eagle-import:SUNPLUS_RGB")
      (libsource (lib "eagle-import") (part "LED_RGB_PADSUNPLUS"))
    )
    (comp (ref "RGB13")
      (value "LED_RGB_PADSUNPLUS")
      (footprint "eagle-import:SUNPLUS_RGB")
      (libsource (lib "eagle-import") (part "LED_RGB_PADSUNPLUS"))
    )
    (comp (ref "RGB14")
      (value "LED_RGB_PADSUNPLUS")
      (footprint "eagle-import:SUNPLUS_RGB")
      (libsource (lib "eagle-import") (part "LED_RGB_PADSUNPLUS"))
    )
    (comp (ref "RGB15")
      (value "LED_RGB_PADSUNPLUS")
      (footprint "eagle-import:SUNPLUS_RGB")
      (libsource (lib "eagle-import") (part "LED_RGB_PADSUNPLUS"))
    )
    (comp (ref "RGB16")
      (value "LED_RGB_PADSUNPLUS")
      (footprint "eagle-import:SUNPLUS_RGB")
      (libsource (lib "eagle-import") (part "LED_RGB_PADSUNPLUS"))
    )
    (comp (ref "RGB17")
      (value "LED_RGB_PADSUNPLUS")
      (footprint "eagle-import:SUNPLUS_RGB")
      (libsource (lib "eagle-import") (part "LED_RGB_PADSUNPLUS"))
    )
    (comp (ref "RGB18")
      (value "LED_RGB_PADSUNPLUS")
      (footprint "eagle-import:SUNPLUS_RGB")
      (libsource (lib "eagle-import") (part "LED_RGB_PADSUNPLUS"))
    )
    (comp (ref "RGB19")
      (value "LED_RGB_PADSUNPLUS")
      (footprint "eagle-import:SUNPLUS_RGB")
      (libsource (lib "eagle-import") (part "LED_RGB_PADSUNPLUS"))
    )
    (comp (ref "RGB20")
      (value "LED_RGB_PADSUNPLUS")
      (footprint "eagle-import:SUNPLUS_RGB")
      (libsource (lib "eagle-import") (part "LED_RGB_PADSUNPLUS"))
    )
    (comp (ref "RGB21")
      (value "LED_RGB_PADSUNPLUS")
      (footprint "eagle-import:SUNPLUS_RGB")
      (libsource (lib "eagle-import") (part "LED_RGB_PADSUNPLUS"))
    )
    (comp (ref "RGB22")
      (value "LED_RGB_PADSUNPLUS")
      (footprint "eagle-import:SUNPLUS_RGB")
      (libsource (lib "eagle-import") (part "LED_RGB_PADSUNPLUS"))
    )
    (comp (ref "RGB23")
      (value "LED_RGB_PADSUNPLUS")
      (footprint "eagle-import:SUNPLUS_RGB")
      (libsource (lib "eagle-import") (part "LED_RGB_PADSUNPLUS"))
    )
    (comp (ref "RGB24")
      (value "LED_RGB_PADSUNPLUS")
      (footprint "eagle-import:SUNPLUS_RGB")
      (libsource (lib "eagle-import") (part "LED_RGB_PADSUNPLUS"))
    )
    (comp (ref "RGB25")
      (value "LED_RGB_PADSUNPLUS")
      (footprint "eagle-import:SUNPLUS_RGB")
      (libsource (lib "eagle-import") (part "LED_RGB_PADSUNPLUS"))
    )
    (comp (ref "RGB26")
      (value "LED_RGB_PADSUNPLUS")
      (footprint "eagle-import:SUNPLUS_RGB")
      (libsource (lib "eagle-import") (part "LED_RGB_PADSUNPLUS"))
    )
    (comp (ref "RGB27")
      (value "LED_RGB_PADSUNPLUS")
      (footprint "eagle-import:SUNPLUS_RGB")
      (libsource (lib "eagle-import") (part "LED_RGB_PADSUNPLUS"))
    )
    (comp (ref "RGB28")
      (value "LED_RGB_PADSUNPLUS")
      (footprint "eagle-import:SUNPLUS_RGB")
      (libsource (lib "eagle-import") (part "LED_RGB_PADSUNPLUS"))
    )
    (comp (ref "RGB29")
      (value "LED_RGB_PADSUNPLUS")
      (footprint "eagle-import:SUNPLUS_RGB")
      (libsource (lib "eagle-import") (part "LED_RGB_PADSUNPLUS"))
    )
    (comp (ref "RGB30")
      (value "LED_RGB_PADSUNPLUS")
      (footprint "eagle-import:SUNPLUS_RGB")
      (libsource (lib "eagle-import") (part "LED_RGB_PADSUNPLUS"))
    )
    (comp (ref "RGB31")
      (value "LED_RGB_PADSUNPLUS")
      (footprint "eagle-import:SUNPLUS_RGB")
      (libsource (lib "eagle-import") (part "LED_RGB_PADSUNPLUS"))
    )
    (comp (ref "RGB32")
      (value "LED_RGB_PADSUNPLUS")
      (footprint "eagle-import:SUNPLUS_RGB")
      (libsource (lib "eagle-import") (part "LED_RGB_PADSUNPLUS"))
    )
    (comp (ref "U1")
      (value "AP8802")
      (footprint "eagle-import:SOIC8-EP")
      (libsource (lib "eagle-import") (part "AP8802"))
    )
    (comp (ref "U2")
      (value "AP8802")
      (footprint "eagle-import:SOIC8-EP")
      (libsource (lib "eagle-import") (part "AP8802"))
    )
    (comp (ref "C10")
      (value "CPOL-US153CLV-0810")
      (footprint "eagle-import:153CLV-0810")
      (libsource (lib "eagle-import") (part "CPOL-US153CLV-0810"))
    )
    (comp (ref "C11")
      (value "0.1")
      (footprint "eagle-import:0805S")
      (libsource (lib "eagle-import") (part "CAPS0805S"))
    )
    (comp (ref "C12")
      (value "10@50")
      (footprint "eagle-import:1210S")
      (libsource (lib "eagle-import") (part "CAPS1210S"))
    )
    (comp (ref "C13")
      (value "2.2@50")
      (footprint "eagle-import:1206S")
      (libsource (lib "eagle-import") (part "CAPS1206S"))
    )
    (comp (ref "C14")
      (value "2.2@50")
      (footprint "eagle-import:1206S")
      (libsource (lib "eagle-import") (part "CAPS1206S"))
    )
    (comp (ref "C15")
      (value "2.2@50")
      (footprint "eagle-import:1206S")
      (libsource (lib "eagle-import") (part "CAPS1206S"))
    )
    (comp (ref "C16")
      (value "10@50")
      (footprint "eagle-import:1210S")
      (libsource (lib "eagle-import") (part "CAPS1210S"))
    )
    (comp (ref "C17")
      (value "0.1")
      (footprint "eagle-import:0805S")
      (libsource (lib "eagle-import") (part "CAPS0805S"))
    )
    (comp (ref "C18")
      (value "2.2@50")
      (footprint "eagle-import:1206S")
      (libsource (lib "eagle-import") (part "CAPS1206S"))
    )
    (comp (ref "C19")
      (value "CPOL-US153CLV-0810")
      (footprint "eagle-import:153CLV-0810")
      (libsource (lib "eagle-import") (part "CPOL-US153CLV-0810"))
    )
    (comp (ref "C22")
      (value "10@50")
      (footprint "eagle-import:1210S")
      (libsource (lib "eagle-import") (part "CAPS1210S"))
    )
    (comp (ref "C23")
      (value "10@50")
      (footprint "eagle-import:1210S")
      (libsource (lib "eagle-import") (part "CAPS1210S"))
    )
    (comp (ref "D131")
      (value "LEDLED_SFH4050")
      (footprint "eagle-import:LED_SFH4050")
      (libsource (lib "eagle-import") (part "LEDLED_SFH4050"))
    )
    (comp (ref "D132")
      (value "LEDLED_SFH4050")
      (footprint "eagle-import:LED_SFH4050")
      (libsource (lib "eagle-import") (part "LEDLED_SFH4050"))
    )
    (comp (ref "D133")
      (value "LEDLED_SFH4050")
      (footprint "eagle-import:LED_SFH4050")
      (libsource (lib "eagle-import") (part "LEDLED_SFH4050"))
    )
    (comp (ref "D134")
      (value "LEDLED_SFH4050")
      (footprint "eagle-import:LED_SFH4050")
      (libsource (lib "eagle-import") (part "LEDLED_SFH4050"))
    )
    (comp (ref "D135")
      (value "LEDLED_SFH4050")
      (footprint "eagle-import:LED_SFH4050")
      (libsource (lib "eagle-import") (part "LEDLED_SFH4050"))
    )
    (comp (ref "D136")
      (value "LEDLED_SFH4050")
      (footprint "eagle-import:LED_SFH4050")
      (libsource (lib "eagle-import") (part "LEDLED_SFH4050"))
    )
    (comp (ref "D137")
      (value "LEDLED_SFH4050")
      (footprint "eagle-import:LED_SFH4050")
      (libsource (lib "eagle-import") (part "LEDLED_SFH4050"))
    )
    (comp (ref "D138")
      (value "LEDLED_SFH4050")
      (footprint "eagle-import:LED_SFH4050")
      (libsource (lib "eagle-import") (part "LEDLED_SFH4050"))
    )
    (comp (ref "D139")
      (value "LEDLED_SFH4050")
      (footprint "eagle-import:LED_SFH4050")
      (libsource (lib "eagle-import") (part "LEDLED_SFH4050"))
    )
    (comp (ref "D140")
      (value "LEDLED_SFH4050")
      (footprint "eagle-import:LED_SFH4050")
      (libsource (lib "eagle-import") (part "LEDLED_SFH4050"))
    )
    (comp (ref "D141")
      (value "LEDLED_SFH4050")
      (footprint "eagle-import:LED_SFH4050")
      (libsource (lib "eagle-import") (part "LEDLED_SFH4050"))
    )
    (comp (ref "D142")
      (value "LEDLED_SFH4050")
      (footprint "eagle-import:LED_SFH4050")
      (libsource (lib "eagle-import") (part "LEDLED_SFH4050"))
    )
    (comp (ref "D143")
      (value "LEDLED_SFH4050")
      (footprint "eagle-import:LED_SFH4050")
      (libsource (lib "eagle-import") (part "LEDLED_SFH4050"))
    )
    (comp (ref "D144")
      (value "LEDLED_SFH4050")
      (footprint "eagle-import:LED_SFH4050")
      (libsource (lib "eagle-import") (part "LEDLED_SFH4050"))
    )
    (comp (ref "D145")
      (value "LEDLED_SFH4050")
      (footprint "eagle-import:LED_SFH4050")
      (libsource (lib "eagle-import") (part "LEDLED_SFH4050"))
    )
    (comp (ref "D146")
      (value "LEDLED_SFH4050")
      (footprint "eagle-import:LED_SFH4050")
      (libsource (lib "eagle-import") (part "LEDLED_SFH4050"))
    )
    (comp (ref "D147")
      (value "LEDLED_SFH4050")
      (footprint "eagle-import:LED_SFH4050")
      (libsource (lib "eagle-import") (part "LEDLED_SFH4050"))
    )
    (comp (ref "D148")
      (value "LEDLED_SFH4050")
      (footprint "eagle-import:LED_SFH4050")
      (libsource (lib "eagle-import") (part "LEDLED_SFH4050"))
    )
    (comp (ref "D149")
      (value "LEDLED_SFH4050")
      (footprint "eagle-import:LED_SFH4050")
      (libsource (lib "eagle-import") (part "LEDLED_SFH4050"))
    )
    (comp (ref "D150")
      (value "LEDLED_SFH4050")
      (footprint "eagle-import:LED_SFH4050")
      (libsource (lib "eagle-import") (part "LEDLED_SFH4050"))
    )
    (comp (ref "D151")
      (value "LEDLED_SFH4050")
      (footprint "eagle-import:LED_SFH4050")
      (libsource (lib "eagle-import") (part "LEDLED_SFH4050"))
    )
    (comp (ref "D152")
      (value "LEDLED_SFH4050")
      (footprint "eagle-import:LED_SFH4050")
      (libsource (lib "eagle-import") (part "LEDLED_SFH4050"))
    )
    (comp (ref "D153")
      (value "LEDLED_SFH4050")
      (footprint "eagle-import:LED_SFH4050")
      (libsource (lib "eagle-import") (part "LEDLED_SFH4050"))
    )
    (comp (ref "D154")
      (value "LEDLED_SFH4050")
      (footprint "eagle-import:LED_SFH4050")
      (libsource (lib "eagle-import") (part "LEDLED_SFH4050"))
    )
    (comp (ref "D155")
      (value "LEDLED_SFH4050")
      (footprint "eagle-import:LED_SFH4050")
      (libsource (lib "eagle-import") (part "LEDLED_SFH4050"))
    )
    (comp (ref "D156")
      (value "LEDLED_SFH4050")
      (footprint "eagle-import:LED_SFH4050")
      (libsource (lib "eagle-import") (part "LEDLED_SFH4050"))
    )
    (comp (ref "D157")
      (value "LEDLED_SFH4050")
      (footprint "eagle-import:LED_SFH4050")
      (libsource (lib "eagle-import") (part "LEDLED_SFH4050"))
    )
    (comp (ref "D158")
      (value "LEDLED_SFH4050")
      (footprint "eagle-import:LED_SFH4050")
      (libsource (lib "eagle-import") (part "LEDLED_SFH4050"))
    )
    (comp (ref "D159")
      (value "LEDLED_SFH4050")
      (footprint "eagle-import:LED_SFH4050")
      (libsource (lib "eagle-import") (part "LEDLED_SFH4050"))
    )
    (comp (ref "D160")
      (value "LEDLED_SFH4050")
      (footprint "eagle-import:LED_SFH4050")
      (libsource (lib "eagle-import") (part "LEDLED_SFH4050"))
    )
    (comp (ref "D161")
      (value "LEDLED_SFH4050")
      (footprint "eagle-import:LED_SFH4050")
      (libsource (lib "eagle-import") (part "LEDLED_SFH4050"))
    )
    (comp (ref "D162")
      (value "LEDLED_SFH4050")
      (footprint "eagle-import:LED_SFH4050")
      (libsource (lib "eagle-import") (part "LEDLED_SFH4050"))
    )
    (comp (ref "D163")
      (value "LEDLED_SFH4050")
      (footprint "eagle-import:LED_SFH4050")
      (libsource (lib "eagle-import") (part "LEDLED_SFH4050"))
    )
    (comp (ref "D164")
      (value "LEDLED_SFH4050")
      (footprint "eagle-import:LED_SFH4050")
      (libsource (lib "eagle-import") (part "LEDLED_SFH4050"))
    )
    (comp (ref "D165")
      (value "LEDLED_SFH4050")
      (footprint "eagle-import:LED_SFH4050")
      (libsource (lib "eagle-import") (part "LEDLED_SFH4050"))
    )
    (comp (ref "D166")
      (value "LEDLED_SFH4050")
      (footprint "eagle-import:LED_SFH4050")
      (libsource (lib "eagle-import") (part "LEDLED_SFH4050"))
    )
    (comp (ref "D167")
      (value "LEDLED_SFH4050")
      (footprint "eagle-import:LED_SFH4050")
      (libsource (lib "eagle-import") (part "LEDLED_SFH4050"))
    )
    (comp (ref "D168")
      (value "LEDLED_SFH4050")
      (footprint "eagle-import:LED_SFH4050")
      (libsource (lib "eagle-import") (part "LEDLED_SFH4050"))
    )
    (comp (ref "D169")
      (value "LEDLED_SFH4050")
      (footprint "eagle-import:LED_SFH4050")
      (libsource (lib "eagle-import") (part "LEDLED_SFH4050"))
    )
    (comp (ref "D170")
      (value "LEDLED_SFH4050")
      (footprint "eagle-import:LED_SFH4050")
      (libsource (lib "eagle-import") (part "LEDLED_SFH4050"))
    )
    (comp (ref "D171")
      (value "LEDLED_SFH4050")
      (footprint "eagle-import:LED_SFH4050")
      (libsource (lib "eagle-import") (part "LEDLED_SFH4050"))
    )
    (comp (ref "D172")
      (value "LEDLED_SFH4050")
      (footprint "eagle-import:LED_SFH4050")
      (libsource (lib "eagle-import") (part "LEDLED_SFH4050"))
    )
    (comp (ref "D173")
      (value "LEDLED_SFH4050")
      (footprint "eagle-import:LED_SFH4050")
      (libsource (lib "eagle-import") (part "LEDLED_SFH4050"))
    )
    (comp (ref "D174")
      (value "LEDLED_SFH4050")
      (footprint "eagle-import:LED_SFH4050")
      (libsource (lib "eagle-import") (part "LEDLED_SFH4050"))
    )
    (comp (ref "D175")
      (value "LEDLED_SFH4050")
      (footprint "eagle-import:LED_SFH4050")
      (libsource (lib "eagle-import") (part "LEDLED_SFH4050"))
    )
    (comp (ref "D176")
      (value "LEDLED_SFH4050")
      (footprint "eagle-import:LED_SFH4050")
      (libsource (lib "eagle-import") (part "LEDLED_SFH4050"))
    )
    (comp (ref "D177")
      (value "LEDLED_SFH4050")
      (footprint "eagle-import:LED_SFH4050")
      (libsource (lib "eagle-import") (part "LEDLED_SFH4050"))
    )
    (comp (ref "D178")
      (value "LEDLED_SFH4050")
      (footprint "eagle-import:LED_SFH4050")
      (libsource (lib "eagle-import") (part "LEDLED_SFH4050"))
    )
    (comp (ref "D179")
      (value "DLFS240L")
      (footprint "eagle-import:PWRDI-123")
      (libsource (lib "eagle-import") (part "DIODE_SCHOTTKYPWRDI-123"))
    )
    (comp (ref "D180")
      (value "LEDLED_SFH4050")
      (footprint "eagle-import:LED_SFH4050")
      (libsource (lib "eagle-import") (part "LEDLED_SFH4050"))
    )
    (comp (ref "D181")
      (value "LEDLED_SFH4050")
      (footprint "eagle-import:LED_SFH4050")
      (libsource (lib "eagle-import") (part "LEDLED_SFH4050"))
    )
    (comp (ref "D182")
      (value "LEDLED_SFH4050")
      (footprint "eagle-import:LED_SFH4050")
      (libsource (lib "eagle-import") (part "LEDLED_SFH4050"))
    )
    (comp (ref "D183")
      (value "LEDLED_SFH4050")
      (footprint "eagle-import:LED_SFH4050")
      (libsource (lib "eagle-import") (part "LEDLED_SFH4050"))
    )
    (comp (ref "D184")
      (value "LEDLED_SFH4050")
      (footprint "eagle-import:LED_SFH4050")
      (libsource (lib "eagle-import") (part "LEDLED_SFH4050"))
    )
    (comp (ref "D185")
      (value "LEDLED_SFH4050")
      (footprint "eagle-import:LED_SFH4050")
      (libsource (lib "eagle-import") (part "LEDLED_SFH4050"))
    )
    (comp (ref "D186")
      (value "LEDLED_SFH4050")
      (footprint "eagle-import:LED_SFH4050")
      (libsource (lib "eagle-import") (part "LEDLED_SFH4050"))
    )
    (comp (ref "D187")
      (value "LEDLED_SFH4050")
      (footprint "eagle-import:LED_SFH4050")
      (libsource (lib "eagle-import") (part "LEDLED_SFH4050"))
    )
    (comp (ref "D188")
      (value "LEDLED_SFH4050")
      (footprint "eagle-import:LED_SFH4050")
      (libsource (lib "eagle-import") (part "LEDLED_SFH4050"))
    )
    (comp (ref "D189")
      (value "LEDLED_SFH4050")
      (footprint "eagle-import:LED_SFH4050")
      (libsource (lib "eagle-import") (part "LEDLED_SFH4050"))
    )
    (comp (ref "D190")
      (value "LEDLED_SFH4050")
      (footprint "eagle-import:LED_SFH4050")
      (libsource (lib "eagle-import") (part "LEDLED_SFH4050"))
    )
    (comp (ref "D191")
      (value "LEDLED_SFH4050")
      (footprint "eagle-import:LED_SFH4050")
      (libsource (lib "eagle-import") (part "LEDLED_SFH4050"))
    )
    (comp (ref "D192")
      (value "LEDLED_SFH4050")
      (footprint "eagle-import:LED_SFH4050")
      (libsource (lib "eagle-import") (part "LEDLED_SFH4050"))
    )
    (comp (ref "D193")
      (value "LEDLED_SFH4050")
      (footprint "eagle-import:LED_SFH4050")
      (libsource (lib "eagle-import") (part "LEDLED_SFH4050"))
    )
    (comp (ref "D194")
      (value "LEDLED_SFH4050")
      (footprint "eagle-import:LED_SFH4050")
      (libsource (lib "eagle-import") (part "LEDLED_SFH4050"))
    )
    (comp (ref "D195")
      (value "LEDLED_SFH4050")
      (footprint "eagle-import:LED_SFH4050")
      (libsource (lib "eagle-import") (part "LEDLED_SFH4050"))
    )
    (comp (ref "D196")
      (value "LEDLED_SFH4050")
      (footprint "eagle-import:LED_SFH4050")
      (libsource (lib "eagle-import") (part "LEDLED_SFH4050"))
    )
    (comp (ref "D197")
      (value "LEDLED_SFH4050")
      (footprint "eagle-import:LED_SFH4050")
      (libsource (lib "eagle-import") (part "LEDLED_SFH4050"))
    )
    (comp (ref "D198")
      (value "LEDLED_SFH4050")
      (footprint "eagle-import:LED_SFH4050")
      (libsource (lib "eagle-import") (part "LEDLED_SFH4050"))
    )
    (comp (ref "D199")
      (value "LEDLED_SFH4050")
      (footprint "eagle-import:LED_SFH4050")
      (libsource (lib "eagle-import") (part "LEDLED_SFH4050"))
    )
    (comp (ref "D200")
      (value "LEDLED_SFH4050")
      (footprint "eagle-import:LED_SFH4050")
      (libsource (lib "eagle-import") (part "LEDLED_SFH4050"))
    )
    (comp (ref "D201")
      (value "LEDLED_SFH4050")
      (footprint "eagle-import:LED_SFH4050")
      (libsource (lib "eagle-import") (part "LEDLED_SFH4050"))
    )
    (comp (ref "D202")
      (value "LEDLED_SFH4050")
      (footprint "eagle-import:LED_SFH4050")
      (libsource (lib "eagle-import") (part "LEDLED_SFH4050"))
    )
    (comp (ref "D203")
      (value "LEDLED_SFH4050")
      (footprint "eagle-import:LED_SFH4050")
      (libsource (lib "eagle-import") (part "LEDLED_SFH4050"))
    )
    (comp (ref "D204")
      (value "LEDLED_SFH4050")
      (footprint "eagle-import:LED_SFH4050")
      (libsource (lib "eagle-import") (part "LEDLED_SFH4050"))
    )
    (comp (ref "D205")
      (value "LEDLED_SFH4050")
      (footprint "eagle-import:LED_SFH4050")
      (libsource (lib "eagle-import") (part "LEDLED_SFH4050"))
    )
    (comp (ref "D206")
      (value "LEDLED_SFH4050")
      (footprint "eagle-import:LED_SFH4050")
      (libsource (lib "eagle-import") (part "LEDLED_SFH4050"))
    )
    (comp (ref "D207")
      (value "LEDLED_SFH4050")
      (footprint "eagle-import:LED_SFH4050")
      (libsource (lib "eagle-import") (part "LEDLED_SFH4050"))
    )
    (comp (ref "D208")
      (value "LEDLED_SFH4050")
      (footprint "eagle-import:LED_SFH4050")
      (libsource (lib "eagle-import") (part "LEDLED_SFH4050"))
    )
    (comp (ref "D209")
      (value "LEDLED_SFH4050")
      (footprint "eagle-import:LED_SFH4050")
      (libsource (lib "eagle-import") (part "LEDLED_SFH4050"))
    )
    (comp (ref "D210")
      (value "LEDLED_SFH4050")
      (footprint "eagle-import:LED_SFH4050")
      (libsource (lib "eagle-import") (part "LEDLED_SFH4050"))
    )
    (comp (ref "D211")
      (value "LEDLED_SFH4050")
      (footprint "eagle-import:LED_SFH4050")
      (libsource (lib "eagle-import") (part "LEDLED_SFH4050"))
    )
    (comp (ref "D212")
      (value "DLFS240L")
      (footprint "eagle-import:PWRDI-123")
      (libsource (lib "eagle-import") (part "DIODE_SCHOTTKYPWRDI-123"))
    )
    (comp (ref "D213")
      (value "LEDLED_SFH4050")
      (footprint "eagle-import:LED_SFH4050")
      (libsource (lib "eagle-import") (part "LEDLED_SFH4050"))
    )
    (comp (ref "D214")
      (value "LEDLED_SFH4050")
      (footprint "eagle-import:LED_SFH4050")
      (libsource (lib "eagle-import") (part "LEDLED_SFH4050"))
    )
    (comp (ref "D215")
      (value "LEDLED_SFH4050")
      (footprint "eagle-import:LED_SFH4050")
      (libsource (lib "eagle-import") (part "LEDLED_SFH4050"))
    )
    (comp (ref "D216")
      (value "LEDLED_SFH4050")
      (footprint "eagle-import:LED_SFH4050")
      (libsource (lib "eagle-import") (part "LEDLED_SFH4050"))
    )
    (comp (ref "D217")
      (value "LEDLED_SFH4050")
      (footprint "eagle-import:LED_SFH4050")
      (libsource (lib "eagle-import") (part "LEDLED_SFH4050"))
    )
    (comp (ref "D218")
      (value "LEDLED_SFH4050")
      (footprint "eagle-import:LED_SFH4050")
      (libsource (lib "eagle-import") (part "LEDLED_SFH4050"))
    )
    (comp (ref "D219")
      (value "LEDLED_SFH4050")
      (footprint "eagle-import:LED_SFH4050")
      (libsource (lib "eagle-import") (part "LEDLED_SFH4050"))
    )
    (comp (ref "D220")
      (value "LEDLED_SFH4050")
      (footprint "eagle-import:LED_SFH4050")
      (libsource (lib "eagle-import") (part "LEDLED_SFH4050"))
    )
    (comp (ref "D221")
      (value "LEDLED_SFH4050")
      (footprint "eagle-import:LED_SFH4050")
      (libsource (lib "eagle-import") (part "LEDLED_SFH4050"))
    )
    (comp (ref "D222")
      (value "LEDLED_SFH4050")
      (footprint "eagle-import:LED_SFH4050")
      (libsource (lib "eagle-import") (part "LEDLED_SFH4050"))
    )
    (comp (ref "D223")
      (value "LEDLED_SFH4050")
      (footprint "eagle-import:LED_SFH4050")
      (libsource (lib "eagle-import") (part "LEDLED_SFH4050"))
    )
    (comp (ref "D224")
      (value "LEDLED_SFH4050")
      (footprint "eagle-import:LED_SFH4050")
      (libsource (lib "eagle-import") (part "LEDLED_SFH4050"))
    )
    (comp (ref "D225")
      (value "LEDLED_SFH4050")
      (footprint "eagle-import:LED_SFH4050")
      (libsource (lib "eagle-import") (part "LEDLED_SFH4050"))
    )
    (comp (ref "D226")
      (value "LEDLED_SFH4050")
      (footprint "eagle-import:LED_SFH4050")
      (libsource (lib "eagle-import") (part "LEDLED_SFH4050"))
    )
    (comp (ref "D227")
      (value "LEDLED_SFH4050")
      (footprint "eagle-import:LED_SFH4050")
      (libsource (lib "eagle-import") (part "LEDLED_SFH4050"))
    )
    (comp (ref "D228")
      (value "LEDLED_SFH4050")
      (footprint "eagle-import:LED_SFH4050")
      (libsource (lib "eagle-import") (part "LEDLED_SFH4050"))
    )
    (comp (ref "D229")
      (value "LEDLED_SFH4050")
      (footprint "eagle-import:LED_SFH4050")
      (libsource (lib "eagle-import") (part "LEDLED_SFH4050"))
    )
    (comp (ref "D230")
      (value "LEDLED_SFH4050")
      (footprint "eagle-import:LED_SFH4050")
      (libsource (lib "eagle-import") (part "LEDLED_SFH4050"))
    )
    (comp (ref "D231")
      (value "LEDLED_SFH4050")
      (footprint "eagle-import:LED_SFH4050")
      (libsource (lib "eagle-import") (part "LEDLED_SFH4050"))
    )
    (comp (ref "D232")
      (value "LEDLED_SFH4050")
      (footprint "eagle-import:LED_SFH4050")
      (libsource (lib "eagle-import") (part "LEDLED_SFH4050"))
    )
    (comp (ref "D233")
      (value "LEDLED_SFH4050")
      (footprint "eagle-import:LED_SFH4050")
      (libsource (lib "eagle-import") (part "LEDLED_SFH4050"))
    )
    (comp (ref "D234")
      (value "LEDLED_SFH4050")
      (footprint "eagle-import:LED_SFH4050")
      (libsource (lib "eagle-import") (part "LEDLED_SFH4050"))
    )
    (comp (ref "D235")
      (value "LEDLED_SFH4050")
      (footprint "eagle-import:LED_SFH4050")
      (libsource (lib "eagle-import") (part "LEDLED_SFH4050"))
    )
    (comp (ref "D236")
      (value "LEDLED_SFH4050")
      (footprint "eagle-import:LED_SFH4050")
      (libsource (lib "eagle-import") (part "LEDLED_SFH4050"))
    )
    (comp (ref "D237")
      (value "LEDLED_SFH4050")
      (footprint "eagle-import:LED_SFH4050")
      (libsource (lib "eagle-import") (part "LEDLED_SFH4050"))
    )
    (comp (ref "D238")
      (value "LEDLED_SFH4050")
      (footprint "eagle-import:LED_SFH4050")
      (libsource (lib "eagle-import") (part "LEDLED_SFH4050"))
    )
    (comp (ref "D239")
      (value "LEDLED_SFH4050")
      (footprint "eagle-import:LED_SFH4050")
      (libsource (lib "eagle-import") (part "LEDLED_SFH4050"))
    )
    (comp (ref "D240")
      (value "LEDLED_SFH4050")
      (footprint "eagle-import:LED_SFH4050")
      (libsource (lib "eagle-import") (part "LEDLED_SFH4050"))
    )
    (comp (ref "D241")
      (value "LEDLED_SFH4050")
      (footprint "eagle-import:LED_SFH4050")
      (libsource (lib "eagle-import") (part "LEDLED_SFH4050"))
    )
    (comp (ref "D242")
      (value "LEDLED_SFH4050")
      (footprint "eagle-import:LED_SFH4050")
      (libsource (lib "eagle-import") (part "LEDLED_SFH4050"))
    )
    (comp (ref "D243")
      (value "LEDLED_SFH4050")
      (footprint "eagle-import:LED_SFH4050")
      (libsource (lib "eagle-import") (part "LEDLED_SFH4050"))
    )
    (comp (ref "D244")
      (value "LEDLED_SFH4050")
      (footprint "eagle-import:LED_SFH4050")
      (libsource (lib "eagle-import") (part "LEDLED_SFH4050"))
    )
    (comp (ref "D245")
      (value "LEDLED_SFH4050")
      (footprint "eagle-import:LED_SFH4050")
      (libsource (lib "eagle-import") (part "LEDLED_SFH4050"))
    )
    (comp (ref "D246")
      (value "LEDLED_SFH4050")
      (footprint "eagle-import:LED_SFH4050")
      (libsource (lib "eagle-import") (part "LEDLED_SFH4050"))
    )
    (comp (ref "D247")
      (value "LEDLED_SFH4050")
      (footprint "eagle-import:LED_SFH4050")
      (libsource (lib "eagle-import") (part "LEDLED_SFH4050"))
    )
    (comp (ref "D248")
      (value "LEDLED_SFH4050")
      (footprint "eagle-import:LED_SFH4050")
      (libsource (lib "eagle-import") (part "LEDLED_SFH4050"))
    )
    (comp (ref "D249")
      (value "LEDLED_SFH4050")
      (footprint "eagle-import:LED_SFH4050")
      (libsource (lib "eagle-import") (part "LEDLED_SFH4050"))
    )
    (comp (ref "D250")
      (value "LEDLED_SFH4050")
      (footprint "eagle-import:LED_SFH4050")
      (libsource (lib "eagle-import") (part "LEDLED_SFH4050"))
    )
    (comp (ref "D251")
      (value "LEDLED_SFH4050")
      (footprint "eagle-import:LED_SFH4050")
      (libsource (lib "eagle-import") (part "LEDLED_SFH4050"))
    )
    (comp (ref "D252")
      (value "LEDLED_SFH4050")
      (footprint "eagle-import:LED_SFH4050")
      (libsource (lib "eagle-import") (part "LEDLED_SFH4050"))
    )
    (comp (ref "D253")
      (value "LEDLED_SFH4050")
      (footprint "eagle-import:LED_SFH4050")
      (libsource (lib "eagle-import") (part "LEDLED_SFH4050"))
    )
    (comp (ref "D254")
      (value "LEDLED_SFH4050")
      (footprint "eagle-import:LED_SFH4050")
      (libsource (lib "eagle-import") (part "LEDLED_SFH4050"))
    )
    (comp (ref "D255")
      (value "LEDLED_SFH4050")
      (footprint "eagle-import:LED_SFH4050")
      (libsource (lib "eagle-import") (part "LEDLED_SFH4050"))
    )
    (comp (ref "D256")
      (value "LEDLED_SFH4050")
      (footprint "eagle-import:LED_SFH4050")
      (libsource (lib "eagle-import") (part "LEDLED_SFH4050"))
    )
    (comp (ref "D257")
      (value "LEDLED_SFH4050")
      (footprint "eagle-import:LED_SFH4050")
      (libsource (lib "eagle-import") (part "LEDLED_SFH4050"))
    )
    (comp (ref "D258")
      (value "LEDLED_SFH4050")
      (footprint "eagle-import:LED_SFH4050")
      (libsource (lib "eagle-import") (part "LEDLED_SFH4050"))
    )
    (comp (ref "D259")
      (value "LEDLED_SFH4050")
      (footprint "eagle-import:LED_SFH4050")
      (libsource (lib "eagle-import") (part "LEDLED_SFH4050"))
    )
    (comp (ref "D260")
      (value "LEDLED_SFH4050")
      (footprint "eagle-import:LED_SFH4050")
      (libsource (lib "eagle-import") (part "LEDLED_SFH4050"))
    )
    (comp (ref "J1")
      (value "POWER_JACK_SHUNTPJ-002")
      (footprint "eagle-import:PJ-002")
      (libsource (lib "eagle-import") (part "POWER_JACK_SHUNTPJ-002"))
    )
    (comp (ref "JMP3")
      (value "JUMPER5100")
      (footprint "eagle-import:5100")
      (libsource (lib "eagle-import") (part "JUMPER5100"))
    )
    (comp (ref "JMP8")
      (value "JUMPER5100")
      (footprint "eagle-import:5100")
      (libsource (lib "eagle-import") (part "JUMPER5100"))
    )
    (comp (ref "JMP9")
      (value "JUMPER5100")
      (footprint "eagle-import:5100")
      (libsource (lib "eagle-import") (part "JUMPER5100"))
    )
    (comp (ref "JMP10")
      (value "JUMPER5100")
      (footprint "eagle-import:5100")
      (libsource (lib "eagle-import") (part "JUMPER5100"))
    )
    (comp (ref "JMP11")
      (value "JUMPER5100")
      (footprint "eagle-import:5100")
      (libsource (lib "eagle-import") (part "JUMPER5100"))
    )
    (comp (ref "JMP12")
      (value "JUMPER5100")
      (footprint "eagle-import:5100")
      (libsource (lib "eagle-import") (part "JUMPER5100"))
    )
    (comp (ref "JMP13")
      (value "JUMPER5100")
      (footprint "eagle-import:5100")
      (libsource (lib "eagle-import") (part "JUMPER5100"))
    )
    (comp (ref "JMP16")
      (value "JUMPER5100")
      (footprint "eagle-import:5100")
      (libsource (lib "eagle-import") (part "JUMPER5100"))
    )
    (comp (ref "JMP17")
      (value "JUMPER5100")
      (footprint "eagle-import:5100")
      (libsource (lib "eagle-import") (part "JUMPER5100"))
    )
    (comp (ref "L3")
      (value "68uH/1A")
      (footprint "eagle-import:SRU8043")
      (libsource (lib "eagle-import") (part "INDUCTOR_SMSRU8043"))
    )
    (comp (ref "L4")
      (value "68uH/1A")
      (footprint "eagle-import:SRU8043")
      (libsource (lib "eagle-import") (part "INDUCTOR_SMSRU8043"))
    )
    (comp (ref "P2")
      (value "CON162X8SM-SMALL")
      (footprint "eagle-import:HEADER2X8_SM_SMALL")
      (libsource (lib "eagle-import") (part "CON162X8SM-SMALL"))
    )
    (comp (ref "Q7")
      (value "NPN_DUAL")
      (footprint "eagle-import:LFPAK56D")
      (libsource (lib "eagle-import") (part "NPN_DUAL"))
    )
    (comp (ref "Q8")
      (value "NPN_DUAL")
      (footprint "eagle-import:LFPAK56D")
      (libsource (lib "eagle-import") (part "NPN_DUAL"))
    )
    (comp (ref "Q9")
      (value "NPN_DUAL")
      (footprint "eagle-import:LFPAK56D")
      (libsource (lib "eagle-import") (part "NPN_DUAL"))
    )
    (comp (ref "Q10")
      (value "NPN_DUAL")
      (footprint "eagle-import:LFPAK56D")
      (libsource (lib "eagle-import") (part "NPN_DUAL"))
    )
    (comp (ref "Q11")
      (value "NPN_DUAL")
      (footprint "eagle-import:LFPAK56D")
      (libsource (lib "eagle-import") (part "NPN_DUAL"))
    )
    (comp (ref "Q12")
      (value "NPN_DUAL")
      (footprint "eagle-import:LFPAK56D")
      (libsource (lib "eagle-import") (part "NPN_DUAL"))
    )
    (comp (ref "R35")
      (value "10R0")
      (footprint "eagle-import:1206S")
      (libsource (lib "eagle-import") (part "RESISTOR_SM1206S"))
    )
    (comp (ref "R36")
      (value "10K0")
      (footprint "eagle-import:1206S")
      (libsource (lib "eagle-import") (part "RESISTOR_SM1206S"))
    )
    (comp (ref "R37")
      (value "4R99")
      (footprint "eagle-import:R2512")
      (libsource (lib "eagle-import") (part "R-US_R2512"))
    )
    (comp (ref "R38")
      (value "10R0")
      (footprint "eagle-import:1206S")
      (libsource (lib "eagle-import") (part "RESISTOR_SM1206S"))
    )
    (comp (ref "R39")
      (value "4R99")
      (footprint "eagle-import:R2512")
      (libsource (lib "eagle-import") (part "R-US_R2512"))
    )
    (comp (ref "R40")
      (value "0R0")
      (footprint "eagle-import:1206S")
      (libsource (lib "eagle-import") (part "RESISTOR_SM1206S"))
    )
    (comp (ref "R41")
      (value "4R99")
      (footprint "eagle-import:R2512")
      (libsource (lib "eagle-import") (part "R-US_R2512"))
    )
    (comp (ref "R42")
      (value "10K0")
      (footprint "eagle-import:1206S")
      (libsource (lib "eagle-import") (part "RESISTOR_SM1206S"))
    )
    (comp (ref "R43")
      (value "10R0")
      (footprint "eagle-import:1206S")
      (libsource (lib "eagle-import") (part "RESISTOR_SM1206S"))
    )
    (comp (ref "R44")
      (value "4R99")
      (footprint "eagle-import:R2512")
      (libsource (lib "eagle-import") (part "R-US_R2512"))
    )
    (comp (ref "R45")
      (value "4R99")
      (footprint "eagle-import:R2512")
      (libsource (lib "eagle-import") (part "R-US_R2512"))
    )
    (comp (ref "R46")
      (value "10R0")
      (footprint "eagle-import:1206S")
      (libsource (lib "eagle-import") (part "RESISTOR_SM1206S"))
    )
    (comp (ref "R47")
      (value "4R99")
      (footprint "eagle-import:R2512")
      (libsource (lib "eagle-import") (part "R-US_R2512"))
    )
    (comp (ref "R48")
      (value "4.99K")
      (footprint "eagle-import:0805S")
      (libsource (lib "eagle-import") (part "RESISTOR_SM0805S"))
    )
    (comp (ref "R50")
      (value "1R00")
      (footprint "eagle-import:1206S")
      (libsource (lib "eagle-import") (part "RESISTOR_SM1206S"))
    )
    (comp (ref "R51")
      (value "0R0")
      (footprint "eagle-import:1206S")
      (libsource (lib "eagle-import") (part "RESISTOR_SM1206S"))
    )
    (comp (ref "R52")
      (value "0R0")
      (footprint "eagle-import:R1206")
      (libsource (lib "eagle-import") (part "R-US_R1206"))
    )
    (comp (ref "R53")
      (value "1R00")
      (footprint "eagle-import:1206S")
      (libsource (lib "eagle-import") (part "RESISTOR_SM1206S"))
    )
    (comp (ref "R54")
      (value "4.99K")
      (footprint "eagle-import:0805S")
      (libsource (lib "eagle-import") (part "RESISTOR_SM0805S"))
    )
    (comp (ref "R55")
      (value "0R0")
      (footprint "eagle-import:1206S")
      (libsource (lib "eagle-import") (part "RESISTOR_SM1206S"))
    )
    (comp (ref "R56")
      (value "4R99")
      (footprint "eagle-import:R2512")
      (libsource (lib "eagle-import") (part "R-US_R2512"))
    )
    (comp (ref "R57")
      (value "10R0")
      (footprint "eagle-import:1206S")
      (libsource (lib "eagle-import") (part "RESISTOR_SM1206S"))
    )
    (comp (ref "R58")
      (value "4R99")
      (footprint "eagle-import:R2512")
      (libsource (lib "eagle-import") (part "R-US_R2512"))
    )
    (comp (ref "R59")
      (value "4R99")
      (footprint "eagle-import:R2512")
      (libsource (lib "eagle-import") (part "R-US_R2512"))
    )
    (comp (ref "R60")
      (value "10R0")
      (footprint "eagle-import:1206S")
      (libsource (lib "eagle-import") (part "RESISTOR_SM1206S"))
    )
    (comp (ref "R61")
      (value "4R99")
      (footprint "eagle-import:R2512")
      (libsource (lib "eagle-import") (part "R-US_R2512"))
    )
    (comp (ref "R62")
      (value "0R0")
      (footprint "eagle-import:1206S")
      (libsource (lib "eagle-import") (part "RESISTOR_SM1206S"))
    )
    (comp (ref "R63")
      (value "4R99")
      (footprint "eagle-import:R2512")
      (libsource (lib "eagle-import") (part "R-US_R2512"))
    )
    (comp (ref "R64")
      (value "10R0")
      (footprint "eagle-import:1206S")
      (libsource (lib "eagle-import") (part "RESISTOR_SM1206S"))
    )
    (comp (ref "R65")
      (value "0R0")
      (footprint "eagle-import:1206S")
      (libsource (lib "eagle-import") (part "RESISTOR_SM1206S"))
    )
    (comp (ref "R66")
      (value "4R99")
      (footprint "eagle-import:R2512")
      (libsource (lib "eagle-import") (part "R-US_R2512"))
    )
    (comp (ref "R67")
      (value "10R0")
      (footprint "eagle-import:1206S")
      (libsource (lib "eagle-import") (part "RESISTOR_SM1206S"))
    )
    (comp (ref "R68")
      (value "0R0")
      (footprint "eagle-import:1206S")
      (libsource (lib "eagle-import") (part "RESISTOR_SM1206S"))
    )
    (comp (ref "RGB33")
      (value "LED_RGB_PADSUNPLUS")
      (footprint "eagle-import:SUNPLUS_RGB")
      (libsource (lib "eagle-import") (part "LED_RGB_PADSUNPLUS"))
    )
    (comp (ref "RGB34")
      (value "LED_RGB_PADSUNPLUS")
      (footprint "eagle-import:SUNPLUS_RGB")
      (libsource (lib "eagle-import") (part "LED_RGB_PADSUNPLUS"))
    )
    (comp (ref "RGB35")
      (value "LED_RGB_PADSUNPLUS")
      (footprint "eagle-import:SUNPLUS_RGB")
      (libsource (lib "eagle-import") (part "LED_RGB_PADSUNPLUS"))
    )
    (comp (ref "RGB36")
      (value "LED_RGB_PADSUNPLUS")
      (footprint "eagle-import:SUNPLUS_RGB")
      (libsource (lib "eagle-import") (part "LED_RGB_PADSUNPLUS"))
    )
    (comp (ref "RGB37")
      (value "LED_RGB_PADSUNPLUS")
      (footprint "eagle-import:SUNPLUS_RGB")
      (libsource (lib "eagle-import") (part "LED_RGB_PADSUNPLUS"))
    )
    (comp (ref "RGB38")
      (value "LED_RGB_PADSUNPLUS")
      (footprint "eagle-import:SUNPLUS_RGB")
      (libsource (lib "eagle-import") (part "LED_RGB_PADSUNPLUS"))
    )
    (comp (ref "RGB39")
      (value "LED_RGB_PADSUNPLUS")
      (footprint "eagle-import:SUNPLUS_RGB")
      (libsource (lib "eagle-import") (part "LED_RGB_PADSUNPLUS"))
    )
    (comp (ref "RGB40")
      (value "LED_RGB_PADSUNPLUS")
      (footprint "eagle-import:SUNPLUS_RGB")
      (libsource (lib "eagle-import") (part "LED_RGB_PADSUNPLUS"))
    )
    (comp (ref "RGB41")
      (value "LED_RGB_PADSUNPLUS")
      (footprint "eagle-import:SUNPLUS_RGB")
      (libsource (lib "eagle-import") (part "LED_RGB_PADSUNPLUS"))
    )
    (comp (ref "RGB42")
      (value "LED_RGB_PADSUNPLUS")
      (footprint "eagle-import:SUNPLUS_RGB")
      (libsource (lib "eagle-import") (part "LED_RGB_PADSUNPLUS"))
    )
    (comp (ref "RGB43")
      (value "LED_RGB_PADSUNPLUS")
      (footprint "eagle-import:SUNPLUS_RGB")
      (libsource (lib "eagle-import") (part "LED_RGB_PADSUNPLUS"))
    )
    (comp (ref "RGB44")
      (value "LED_RGB_PADSUNPLUS")
      (footprint "eagle-import:SUNPLUS_RGB")
      (libsource (lib "eagle-import") (part "LED_RGB_PADSUNPLUS"))
    )
    (comp (ref "RGB45")
      (value "LED_RGB_PADSUNPLUS")
      (footprint "eagle-import:SUNPLUS_RGB")
      (libsource (lib "eagle-import") (part "LED_RGB_PADSUNPLUS"))
    )
    (comp (ref "RGB46")
      (value "LED_RGB_PADSUNPLUS")
      (footprint "eagle-import:SUNPLUS_RGB")
      (libsource (lib "eagle-import") (part "LED_RGB_PADSUNPLUS"))
    )
    (comp (ref "RGB47")
      (value "LED_RGB_PADSUNPLUS")
      (footprint "eagle-import:SUNPLUS_RGB")
      (libsource (lib "eagle-import") (part "LED_RGB_PADSUNPLUS"))
    )
    (comp (ref "RGB48")
      (value "LED_RGB_PADSUNPLUS")
      (footprint "eagle-import:SUNPLUS_RGB")
      (libsource (lib "eagle-import") (part "LED_RGB_PADSUNPLUS"))
    )
    (comp (ref "RGB49")
      (value "LED_RGB_PADSUNPLUS")
      (footprint "eagle-import:SUNPLUS_RGB")
      (libsource (lib "eagle-import") (part "LED_RGB_PADSUNPLUS"))
    )
    (comp (ref "RGB50")
      (value "LED_RGB_PADSUNPLUS")
      (footprint "eagle-import:SUNPLUS_RGB")
      (libsource (lib "eagle-import") (part "LED_RGB_PADSUNPLUS"))
    )
    (comp (ref "RGB51")
      (value "LED_RGB_PADSUNPLUS")
      (footprint "eagle-import:SUNPLUS_RGB")
      (libsource (lib "eagle-import") (part "LED_RGB_PADSUNPLUS"))
    )
    (comp (ref "RGB52")
      (value "LED_RGB_PADSUNPLUS")
      (footprint "eagle-import:SUNPLUS_RGB")
      (libsource (lib "eagle-import") (part "LED_RGB_PADSUNPLUS"))
    )
    (comp (ref "RGB53")
      (value "LED_RGB_PADSUNPLUS")
      (footprint "eagle-import:SUNPLUS_RGB")
      (libsource (lib "eagle-import") (part "LED_RGB_PADSUNPLUS"))
    )
    (comp (ref "RGB54")
      (value "LED_RGB_PADSUNPLUS")
      (footprint "eagle-import:SUNPLUS_RGB")
      (libsource (lib "eagle-import") (part "LED_RGB_PADSUNPLUS"))
    )
    (comp (ref "RGB55")
      (value "LED_RGB_PADSUNPLUS")
      (footprint "eagle-import:SUNPLUS_RGB")
      (libsource (lib "eagle-import") (part "LED_RGB_PADSUNPLUS"))
    )
    (comp (ref "RGB56")
      (value "LED_RGB_PADSUNPLUS")
      (footprint "eagle-import:SUNPLUS_RGB")
      (libsource (lib "eagle-import") (part "LED_RGB_PADSUNPLUS"))
    )
    (comp (ref "RGB57")
      (value "LED_RGB_PADSUNPLUS")
      (footprint "eagle-import:SUNPLUS_RGB")
      (libsource (lib "eagle-import") (part "LED_RGB_PADSUNPLUS"))
    )
    (comp (ref "RGB58")
      (value "LED_RGB_PADSUNPLUS")
      (footprint "eagle-import:SUNPLUS_RGB")
      (libsource (lib "eagle-import") (part "LED_RGB_PADSUNPLUS"))
    )
    (comp (ref "RGB59")
      (value "LED_RGB_PADSUNPLUS")
      (footprint "eagle-import:SUNPLUS_RGB")
      (libsource (lib "eagle-import") (part "LED_RGB_PADSUNPLUS"))
    )
    (comp (ref "RGB60")
      (value "LED_RGB_PADSUNPLUS")
      (footprint "eagle-import:SUNPLUS_RGB")
      (libsource (lib "eagle-import") (part "LED_RGB_PADSUNPLUS"))
    )
    (comp (ref "RGB61")
      (value "LED_RGB_PADSUNPLUS")
      (footprint "eagle-import:SUNPLUS_RGB")
      (libsource (lib "eagle-import") (part "LED_RGB_PADSUNPLUS"))
    )
    (comp (ref "RGB62")
      (value "LED_RGB_PADSUNPLUS")
      (footprint "eagle-import:SUNPLUS_RGB")
      (libsource (lib "eagle-import") (part "LED_RGB_PADSUNPLUS"))
    )
    (comp (ref "RGB63")
      (value "LED_RGB_PADSUNPLUS")
      (footprint "eagle-import:SUNPLUS_RGB")
      (libsource (lib "eagle-import") (part "LED_RGB_PADSUNPLUS"))
    )
    (comp (ref "RGB64")
      (value "LED_RGB_PADSUNPLUS")
      (footprint "eagle-import:SUNPLUS_RGB")
      (libsource (lib "eagle-import") (part "LED_RGB_PADSUNPLUS"))
    )
    (comp (ref "U$19")
      (value "JFRC-LOGOLOGO_OP")
      (footprint "eagle-import:LOGO_BMP_OP")
      (libsource (lib "eagle-import") (part "JFRC-LOGOLOGO_OP"))
    )
    (comp (ref "U3")
      (value "AP8802")
      (footprint "eagle-import:SOIC8-EP")
      (libsource (lib "eagle-import") (part "AP8802"))
    )
    (comp (ref "U4")
      (value "AP8802")
      (footprint "eagle-import:SOIC8-EP")
      (libsource (lib "eagle-import") (part "AP8802"))
    )
  )
  (nets
    (net (code "1") (name "BLU1") (class "Default")
      (node (ref "P1") (pin "16") (pinfunction "16_16") (pintype "bidirectional"))
      (node (ref "Q1") (pin "4") (pinfunction "B2_4") (pintype "bidirectional"))
      (node (ref "R2") (pin "1") (pinfunction "1_1") (pintype "passive"))
    )
    (net (code "2") (name "BLU1F") (class "Default")
      (node (ref "P1") (pin "14") (pinfunction "14_14") (pintype "bidirectional"))
      (node (ref "Q1") (pin "3") (pinfunction "E2_3") (pintype "bidirectional"))
      (node (ref "R5") (pin "2") (pinfunction "2_2") (pintype "passive"))
    )
    (net (code "3") (name "BLU1K") (class "Default")
      (node (ref "Q1") (pin "7") (pinfunction "C1_7") (pintype "bidirectional"))
      (node (ref "Q1") (pin "78") (pinfunction "C1_78") (pintype "bidirectional"))
      (node (ref "Q1") (pin "8") (pinfunction "C1_8") (pintype "bidirectional"))
      (node (ref "RGB1") (pin "BC") (pinfunction "BC_BC") (pintype "bidirectional"))
    )
    (net (code "4") (name "BLU1K2") (class "Default")
      (node (ref "Q1") (pin "5") (pinfunction "C2_5") (pintype "bidirectional"))
      (node (ref "Q1") (pin "56") (pinfunction "C2_56") (pintype "bidirectional"))
      (node (ref "Q1") (pin "6") (pinfunction "C2_6") (pintype "bidirectional"))
      (node (ref "RGB9") (pin "BC") (pinfunction "BC_BC") (pintype "bidirectional"))
    )
    (net (code "5") (name "BLU2") (class "Default")
      (node (ref "P1") (pin "3") (pinfunction "3_3") (pintype "bidirectional"))
      (node (ref "Q4") (pin "2") (pinfunction "B1_2") (pintype "bidirectional"))
      (node (ref "R28") (pin "2") (pinfunction "2_2") (pintype "passive"))
    )
    (net (code "6") (name "BLU2F") (class "Default")
      (node (ref "P1") (pin "5") (pinfunction "5_5") (pintype "bidirectional"))
      (node (ref "Q4") (pin "1") (pinfunction "E1_1") (pintype "bidirectional"))
      (node (ref "R22") (pin "2") (pinfunction "2_2") (pintype "passive"))
    )
    (net (code "7") (name "BLU2K1") (class "Default")
      (node (ref "Q4") (pin "7") (pinfunction "C1_7") (pintype "bidirectional"))
      (node (ref "Q4") (pin "78") (pinfunction "C1_78") (pintype "bidirectional"))
      (node (ref "Q4") (pin "8") (pinfunction "C1_8") (pintype "bidirectional"))
      (node (ref "RGB17") (pin "BC") (pinfunction "BC_BC") (pintype "bidirectional"))
    )
    (net (code "8") (name "BLU2K2") (class "Default")
      (node (ref "Q4") (pin "5") (pinfunction "C2_5") (pintype "bidirectional"))
      (node (ref "Q4") (pin "56") (pinfunction "C2_56") (pintype "bidirectional"))
      (node (ref "Q4") (pin "6") (pinfunction "C2_6") (pintype "bidirectional"))
      (node (ref "RGB25") (pin "BC") (pinfunction "BC_BC") (pintype "bidirectional"))
    )
    (net (code "9") (name "BLU3") (class "Default")
      (node (ref "P2") (pin "16") (pinfunction "16_16") (pintype "bidirectional"))
      (node (ref "Q7") (pin "4") (pinfunction "B2_4") (pintype "bidirectional"))
      (node (ref "R36") (pin "1") (pinfunction "1_1") (pintype "passive"))
    )
    (net (code "10") (name "BLU3F") (class "Default")
      (node (ref "P2") (pin "14") (pinfunction "14_14") (pintype "bidirectional"))
      (node (ref "Q7") (pin "3") (pinfunction "E2_3") (pintype "bidirectional"))
      (node (ref "R39") (pin "2") (pinfunction "2_2") (pintype "passive"))
    )
    (net (code "11") (name "BLU4") (class "Default")
      (node (ref "P2") (pin "3") (pinfunction "3_3") (pintype "bidirectional"))
      (node (ref "Q10") (pin "2") (pinfunction "B1_2") (pintype "bidirectional"))
      (node (ref "R62") (pin "2") (pinfunction "2_2") (pintype "passive"))
    )
    (net (code "12") (name "BLU4F") (class "Default")
      (node (ref "P2") (pin "5") (pinfunction "5_5") (pintype "bidirectional"))
      (node (ref "Q10") (pin "1") (pinfunction "E1_1") (pintype "bidirectional"))
      (node (ref "R56") (pin "2") (pinfunction "2_2") (pintype "passive"))
    )
    (net (code "13") (name "GRN1") (class "Default")
      (node (ref "P1") (pin "15") (pinfunction "15_15") (pintype "bidirectional"))
      (node (ref "Q2") (pin "4") (pinfunction "B2_4") (pintype "bidirectional"))
      (node (ref "R6") (pin "1") (pinfunction "1_1") (pintype "passive"))
    )
    (net (code "14") (name "GRN1F") (class "Default")
      (node (ref "P1") (pin "13") (pinfunction "13_13") (pintype "bidirectional"))
      (node (ref "Q2") (pin "3") (pinfunction "E2_3") (pintype "bidirectional"))
      (node (ref "R10") (pin "2") (pinfunction "2_2") (pintype "passive"))
    )
    (net (code "15") (name "GRN1K") (class "Default")
      (node (ref "JMP1") (pin "1") (pinfunction "1_1") (pintype "bidirectional"))
      (node (ref "RGB1") (pin "GC") (pinfunction "GC_GC") (pintype "bidirectional"))
    )
    (net (code "16") (name "GRN1K2") (class "Default")
      (node (ref "Q2") (pin "5") (pinfunction "C2_5") (pintype "bidirectional"))
      (node (ref "Q2") (pin "56") (pinfunction "C2_56") (pintype "bidirectional"))
      (node (ref "Q2") (pin "6") (pinfunction "C2_6") (pintype "bidirectional"))
      (node (ref "RGB9") (pin "GC") (pinfunction "GC_GC") (pintype "bidirectional"))
    )
    (net (code "17") (name "GRN2") (class "Default")
      (node (ref "P1") (pin "2") (pinfunction "2_2") (pintype "bidirectional"))
      (node (ref "Q5") (pin "2") (pinfunction "B1_2") (pintype "bidirectional"))
      (node (ref "R31") (pin "2") (pinfunction "2_2") (pintype "passive"))
    )
    (net (code "18") (name "GRN2F") (class "Default")
      (node (ref "P1") (pin "1") (pinfunction "1_1") (pintype "bidirectional"))
      (node (ref "Q5") (pin "1") (pinfunction "E1_1") (pintype "bidirectional"))
      (node (ref "R25") (pin "2") (pinfunction "2_2") (pintype "passive"))
    )
    (net (code "19") (name "GRN2K1") (class "Default")
      (node (ref "JMP4") (pin "1") (pinfunction "1_1") (pintype "bidirectional"))
      (node (ref "RGB17") (pin "GC") (pinfunction "GC_GC") (pintype "bidirectional"))
    )
    (net (code "20") (name "GRN2K2") (class "Default")
      (node (ref "Q5") (pin "5") (pinfunction "C2_5") (pintype "bidirectional"))
      (node (ref "Q5") (pin "56") (pinfunction "C2_56") (pintype "bidirectional"))
      (node (ref "Q5") (pin "6") (pinfunction "C2_6") (pintype "bidirectional"))
      (node (ref "RGB25") (pin "GC") (pinfunction "GC_GC") (pintype "bidirectional"))
    )
    (net (code "21") (name "GRN3") (class "Default")
      (node (ref "P2") (pin "15") (pinfunction "15_15") (pintype "bidirectional"))
      (node (ref "Q8") (pin "4") (pinfunction "B2_4") (pintype "bidirectional"))
      (node (ref "R40") (pin "1") (pinfunction "1_1") (pintype "passive"))
    )
    (net (code "22") (name "GRN3F") (class "Default")
      (node (ref "P2") (pin "13") (pinfunction "13_13") (pintype "bidirectional"))
      (node (ref "Q8") (pin "3") (pinfunction "E2_3") (pintype "bidirectional"))
      (node (ref "R44") (pin "2") (pinfunction "2_2") (pintype "passive"))
    )
    (net (code "23") (name "GRN4") (class "Default")
      (node (ref "P2") (pin "2") (pinfunction "2_2") (pintype "bidirectional"))
      (node (ref "Q11") (pin "2") (pinfunction "B1_2") (pintype "bidirectional"))
      (node (ref "R65") (pin "2") (pinfunction "2_2") (pintype "passive"))
    )
    (net (code "24") (name "GRN4F") (class "Default")
      (node (ref "P2") (pin "1") (pinfunction "1_1") (pintype "bidirectional"))
      (node (ref "Q11") (pin "1") (pinfunction "E1_1") (pintype "bidirectional"))
      (node (ref "R59") (pin "2") (pinfunction "2_2") (pintype "passive"))
    )
    (net (code "25") (name "HS1") (class "Default")
      (node (ref "RGB2") (pin "T") (pinfunction "PAD_T") (pintype "bidirectional"))
      (node (ref "RGB3") (pin "T") (pinfunction "PAD_T") (pintype "bidirectional"))
      (node (ref "RGB4") (pin "T") (pinfunction "PAD_T") (pintype "bidirectional"))
      (node (ref "RGB5") (pin "T") (pinfunction "PAD_T") (pintype "bidirectional"))
      (node (ref "RGB6") (pin "T") (pinfunction "PAD_T") (pintype "bidirectional"))
      (node (ref "RGB7") (pin "T") (pinfunction "PAD_T") (pintype "bidirectional"))
    )
    (net (code "26") (name "HS2") (class "Default")
      (node (ref "RGB10") (pin "T") (pinfunction "PAD_T") (pintype "bidirectional"))
      (node (ref "RGB11") (pin "T") (pinfunction "PAD_T") (pintype "bidirectional"))
      (node (ref "RGB12") (pin "T") (pinfunction "PAD_T") (pintype "bidirectional"))
      (node (ref "RGB13") (pin "T") (pinfunction "PAD_T") (pintype "bidirectional"))
      (node (ref "RGB14") (pin "T") (pinfunction "PAD_T") (pintype "bidirectional"))
      (node (ref "RGB15") (pin "T") (pinfunction "PAD_T") (pintype "bidirectional"))
    )
    (net (code "27") (name "HS3") (class "Default")
      (node (ref "RGB18") (pin "T") (pinfunction "PAD_T") (pintype "bidirectional"))
      (node (ref "RGB19") (pin "T") (pinfunction "PAD_T") (pintype "bidirectional"))
      (node (ref "RGB20") (pin "T") (pinfunction "PAD_T") (pintype "bidirectional"))
      (node (ref "RGB21") (pin "T") (pinfunction "PAD_T") (pintype "bidirectional"))
      (node (ref "RGB22") (pin "T") (pinfunction "PAD_T") (pintype "bidirectional"))
      (node (ref "RGB23") (pin "T") (pinfunction "PAD_T") (pintype "bidirectional"))
    )
    (net (code "28") (name "HS4") (class "Default")
      (node (ref "RGB26") (pin "T") (pinfunction "PAD_T") (pintype "bidirectional"))
      (node (ref "RGB27") (pin "T") (pinfunction "PAD_T") (pintype "bidirectional"))
      (node (ref "RGB28") (pin "T") (pinfunction "PAD_T") (pintype "bidirectional"))
      (node (ref "RGB29") (pin "T") (pinfunction "PAD_T") (pintype "bidirectional"))
      (node (ref "RGB30") (pin "T") (pinfunction "PAD_T") (pintype "bidirectional"))
      (node (ref "RGB31") (pin "T") (pinfunction "PAD_T") (pintype "bidirectional"))
    )
    (net (code "29") (name "HS5") (class "Default")
      (node (ref "RGB34") (pin "T") (pinfunction "PAD_T") (pintype "bidirectional"))
      (node (ref "RGB35") (pin "T") (pinfunction "PAD_T") (pintype "bidirectional"))
      (node (ref "RGB36") (pin "T") (pinfunction "PAD_T") (pintype "bidirectional"))
      (node (ref "RGB37") (pin "T") (pinfunction "PAD_T") (pintype "bidirectional"))
      (node (ref "RGB38") (pin "T") (pinfunction "PAD_T") (pintype "bidirectional"))
      (node (ref "RGB39") (pin "T") (pinfunction "PAD_T") (pintype "bidirectional"))
    )
    (net (code "30") (name "HS6") (class "Default")
      (node (ref "RGB42") (pin "T") (pinfunction "PAD_T") (pintype "bidirectional"))
      (node (ref "RGB43") (pin "T") (pinfunction "PAD_T") (pintype "bidirectional"))
      (node (ref "RGB44") (pin "T") (pinfunction "PAD_T") (pintype "bidirectional"))
      (node (ref "RGB45") (pin "T") (pinfunction "PAD_T") (pintype "bidirectional"))
      (node (ref "RGB46") (pin "T") (pinfunction "PAD_T") (pintype "bidirectional"))
      (node (ref "RGB47") (pin "T") (pinfunction "PAD_T") (pintype "bidirectional"))
    )
    (net (code "31") (name "HS7") (class "Default")
      (node (ref "RGB50") (pin "T") (pinfunction "PAD_T") (pintype "bidirectional"))
      (node (ref "RGB51") (pin "T") (pinfunction "PAD_T") (pintype "bidirectional"))
      (node (ref "RGB52") (pin "T") (pinfunction "PAD_T") (pintype "bidirectional"))
      (node (ref "RGB53") (pin "T") (pinfunction "PAD_T") (pintype "bidirectional"))
      (node (ref "RGB54") (pin "T") (pinfunction "PAD_T") (pintype "bidirectional"))
      (node (ref "RGB55") (pin "T") (pinfunction "PAD_T") (pintype "bidirectional"))
    )
    (net (code "32") (name "HS8") (class "Default")
      (node (ref "RGB58") (pin "T") (pinfunction "PAD_T") (pintype "bidirectional"))
      (node (ref "RGB59") (pin "T") (pinfunction "PAD_T") (pintype "bidirectional"))
      (node (ref "RGB60") (pin "T") (pinfunction "PAD_T") (pintype "bidirectional"))
      (node (ref "RGB61") (pin "T") (pinfunction "PAD_T") (pintype "bidirectional"))
      (node (ref "RGB62") (pin "T") (pinfunction "PAD_T") (pintype "bidirectional"))
      (node (ref "RGB63") (pin "T") (pinfunction "PAD_T") (pintype "bidirectional"))
    )
    (net (code "33") (name "IGND") (class "Default")
      (node (ref "C11") (pin "2") (pinfunction "2_2") (pintype "passive"))
      (node (ref "C12") (pin "2") (pinfunction "2_2") (pintype "passive"))
      (node (ref "C16") (pin "2") (pinfunction "2_2") (pintype "passive"))
      (node (ref "C17") (pin "2") (pinfunction "2_2") (pintype "passive"))
      (node (ref "C22") (pin "2") (pinfunction "2_2") (pintype "passive"))
      (node (ref "C23") (pin "2") (pinfunction "2_2") (pintype "passive"))
      (node (ref "JMP16") (pin "1") (pinfunction "1_1") (pintype "bidirectional"))
      (node (ref "JMP16") (pin "2") (pinfunction "2_2") (pintype "bidirectional"))
      (node (ref "JMP17") (pin "1") (pinfunction "1_1") (pintype "bidirectional"))
      (node (ref "JMP17") (pin "2") (pinfunction "2_2") (pintype "bidirectional"))
      (node (ref "R48") (pin "1") (pinfunction "1_1") (pintype "passive"))
      (node (ref "R51") (pin "2") (pinfunction "2_2") (pintype "passive"))
      (node (ref "R54") (pin "1") (pinfunction "1_1") (pintype "passive"))
      (node (ref "U3") (pin "2") (pinfunction "GND_2") (pintype "bidirectional"))
      (node (ref "U3") (pin "7") (pinfunction "GND1_7") (pintype "bidirectional"))
      (node (ref "U3") (pin "EP") (pinfunction "EP_EP") (pintype "bidirectional"))
      (node (ref "U4") (pin "2") (pinfunction "GND_2") (pintype "bidirectional"))
      (node (ref "U4") (pin "7") (pinfunction "GND1_7") (pintype "bidirectional"))
      (node (ref "U4") (pin "EP") (pinfunction "EP_EP") (pintype "bidirectional"))
    )
    (net (code "34") (name "IGND1") (class "Default")
      (node (ref "C2") (pin "2") (pinfunction "2_2") (pintype "passive"))
      (node (ref "C20") (pin "2") (pinfunction "2_2") (pintype "passive"))
      (node (ref "C21") (pin "2") (pinfunction "2_2") (pintype "passive"))
      (node (ref "C3") (pin "2") (pinfunction "2_2") (pintype "passive"))
      (node (ref "C7") (pin "2") (pinfunction "2_2") (pintype "passive"))
      (node (ref "C8") (pin "2") (pinfunction "2_2") (pintype "passive"))
      (node (ref "JMP18") (pin "1") (pinfunction "1_1") (pintype "bidirectional"))
      (node (ref "JMP18") (pin "2") (pinfunction "2_2") (pintype "bidirectional"))
      (node (ref "JMP19") (pin "1") (pinfunction "1_1") (pintype "bidirectional"))
      (node (ref "JMP19") (pin "2") (pinfunction "2_2") (pintype "bidirectional"))
      (node (ref "R14") (pin "1") (pinfunction "1_1") (pintype "passive"))
      (node (ref "R17") (pin "2") (pinfunction "2_2") (pintype "passive"))
      (node (ref "R20") (pin "1") (pinfunction "1_1") (pintype "passive"))
      (node (ref "U1") (pin "2") (pinfunction "GND_2") (pintype "bidirectional"))
      (node (ref "U1") (pin "7") (pinfunction "GND1_7") (pintype "bidirectional"))
      (node (ref "U1") (pin "EP") (pinfunction "EP_EP") (pintype "bidirectional"))
      (node (ref "U2") (pin "2") (pinfunction "GND_2") (pintype "bidirectional"))
      (node (ref "U2") (pin "7") (pinfunction "GND1_7") (pintype "bidirectional"))
      (node (ref "U2") (pin "EP") (pinfunction "EP_EP") (pintype "bidirectional"))
    )
    (net (code "35") (name "IR_1") (class "Default")
      (node (ref "P1") (pin "9") (pinfunction "9_9") (pintype "bidirectional"))
      (node (ref "R14") (pin "2") (pinfunction "2_2") (pintype "passive"))
      (node (ref "U1") (pin "8") (pinfunction "CTRL_8") (pintype "bidirectional"))
    )
    (net (code "36") (name "IR_2") (class "Default")
      (node (ref "P1") (pin "7") (pinfunction "7_7") (pintype "bidirectional"))
      (node (ref "R20") (pin "2") (pinfunction "2_2") (pintype "passive"))
      (node (ref "U2") (pin "8") (pinfunction "CTRL_8") (pintype "bidirectional"))
    )
    (net (code "37") (name "IR_3") (class "Default")
      (node (ref "P2") (pin "9") (pinfunction "9_9") (pintype "bidirectional"))
      (node (ref "R48") (pin "2") (pinfunction "2_2") (pintype "passive"))
      (node (ref "U3") (pin "8") (pinfunction "CTRL_8") (pintype "bidirectional"))
    )
    (net (code "38") (name "IR_4") (class "Default")
      (node (ref "P2") (pin "7") (pinfunction "7_7") (pintype "bidirectional"))
      (node (ref "R54") (pin "2") (pinfunction "2_2") (pintype "passive"))
      (node (ref "U4") (pin "8") (pinfunction "CTRL_8") (pintype "bidirectional"))
    )
    (net (code "39") (name "IR_DRV3") (class "Default")
      (node (ref "C13") (pin "1") (pinfunction "1_1") (pintype "passive"))
      (node (ref "C14") (pin "1") (pinfunction "1_1") (pintype "passive"))
      (node (ref "D131") (pin "A") (pinfunction "A_A") (pintype "bidirectional"))
      (node (ref "D147") (pin "A") (pinfunction "A_A") (pintype "bidirectional"))
      (node (ref "D163") (pin "A") (pinfunction "A_A") (pintype "bidirectional"))
      (node (ref "D180") (pin "A") (pinfunction "A_A") (pintype "bidirectional"))
      (node (ref "R50") (pin "1") (pinfunction "1_1") (pintype "passive"))
      (node (ref "RGB33") (pin "T") (pinfunction "PAD_T") (pintype "bidirectional"))
      (node (ref "RGB41") (pin "T") (pinfunction "PAD_T") (pintype "bidirectional"))
      (node (ref "U3") (pin "1") (pinfunction "SET_1") (pintype "bidirectional"))
    )
    (net (code "40") (name "IR_DRV4") (class "Default")
      (node (ref "C15") (pin "1") (pinfunction "1_1") (pintype "passive"))
      (node (ref "C18") (pin "1") (pinfunction "1_1") (pintype "passive"))
      (node (ref "D196") (pin "A") (pinfunction "A_A") (pintype "bidirectional"))
      (node (ref "D213") (pin "A") (pinfunction "A_A") (pintype "bidirectional"))
      (node (ref "D229") (pin "A") (pinfunction "A_A") (pintype "bidirectional"))
      (node (ref "D245") (pin "A") (pinfunction "A_A") (pintype "bidirectional"))
      (node (ref "R53") (pin "1") (pinfunction "1_1") (pintype "passive"))
      (node (ref "RGB49") (pin "T") (pinfunction "PAD_T") (pintype "bidirectional"))
      (node (ref "RGB57") (pin "T") (pinfunction "PAD_T") (pintype "bidirectional"))
      (node (ref "U4") (pin "1") (pinfunction "SET_1") (pintype "bidirectional"))
    )
    (net (code "41") (name "IR_DRV_UL1") (class "Default")
      (node (ref "C4") (pin "1") (pinfunction "1_1") (pintype "passive"))
      (node (ref "C5") (pin "1") (pinfunction "1_1") (pintype "passive"))
      (node (ref "D1") (pin "A") (pinfunction "A_A") (pintype "bidirectional"))
      (node (ref "D17") (pin "A") (pinfunction "A_A") (pintype "bidirectional"))
      (node (ref "D33") (pin "A") (pinfunction "A_A") (pintype "bidirectional"))
      (node (ref "D50") (pin "A") (pinfunction "A_A") (pintype "bidirectional"))
      (node (ref "R16") (pin "1") (pinfunction "1_1") (pintype "passive"))
      (node (ref "RGB1") (pin "T") (pinfunction "PAD_T") (pintype "bidirectional"))
      (node (ref "RGB9") (pin "T") (pinfunction "PAD_T") (pintype "bidirectional"))
      (node (ref "U1") (pin "1") (pinfunction "SET_1") (pintype "bidirectional"))
    )
    (net (code "42") (name "IR_DRV_UL2") (class "Default")
      (node (ref "C6") (pin "1") (pinfunction "1_1") (pintype "passive"))
      (node (ref "C9") (pin "1") (pinfunction "1_1") (pintype "passive"))
      (node (ref "D115") (pin "A") (pinfunction "A_A") (pintype "bidirectional"))
      (node (ref "D66") (pin "A") (pinfunction "A_A") (pintype "bidirectional"))
      (node (ref "D83") (pin "A") (pinfunction "A_A") (pintype "bidirectional"))
      (node (ref "D99") (pin "A") (pinfunction "A_A") (pintype "bidirectional"))
      (node (ref "R19") (pin "1") (pinfunction "1_1") (pintype "passive"))
      (node (ref "RGB17") (pin "T") (pinfunction "PAD_T") (pintype "bidirectional"))
      (node (ref "RGB25") (pin "T") (pinfunction "PAD_T") (pintype "bidirectional"))
      (node (ref "U2") (pin "1") (pinfunction "SET_1") (pintype "bidirectional"))
    )
    (net (code "43") (name "IR_RET3") (class "Default")
      (node (ref "C13") (pin "2") (pinfunction "2_2") (pintype "passive"))
      (node (ref "C14") (pin "2") (pinfunction "2_2") (pintype "passive"))
      (node (ref "D146") (pin "C") (pinfunction "K_C") (pintype "bidirectional"))
      (node (ref "D162") (pin "C") (pinfunction "K_C") (pintype "bidirectional"))
      (node (ref "D178") (pin "C") (pinfunction "K_C") (pintype "bidirectional"))
      (node (ref "D195") (pin "C") (pinfunction "K_C") (pintype "bidirectional"))
      (node (ref "L3") (pin "1") (pinfunction "1_1") (pintype "passive"))
      (node (ref "RGB40") (pin "T") (pinfunction "PAD_T") (pintype "bidirectional"))
      (node (ref "RGB48") (pin "T") (pinfunction "PAD_T") (pintype "bidirectional"))
    )
    (net (code "44") (name "IR_RET_UL1") (class "Default")
      (node (ref "C4") (pin "2") (pinfunction "2_2") (pintype "passive"))
      (node (ref "C5") (pin "2") (pinfunction "2_2") (pintype "passive"))
      (node (ref "D16") (pin "C") (pinfunction "K_C") (pintype "bidirectional"))
      (node (ref "D32") (pin "C") (pinfunction "K_C") (pintype "bidirectional"))
      (node (ref "D48") (pin "C") (pinfunction "K_C") (pintype "bidirectional"))
      (node (ref "D65") (pin "C") (pinfunction "K_C") (pintype "bidirectional"))
      (node (ref "L1") (pin "1") (pinfunction "1_1") (pintype "passive"))
      (node (ref "RGB16") (pin "T") (pinfunction "PAD_T") (pintype "bidirectional"))
      (node (ref "RGB8") (pin "T") (pinfunction "PAD_T") (pintype "bidirectional"))
    )
    (net (code "45") (name "I_RET4") (class "Default")
      (node (ref "C15") (pin "2") (pinfunction "2_2") (pintype "passive"))
      (node (ref "D211") (pin "C") (pinfunction "K_C") (pintype "bidirectional"))
      (node (ref "D228") (pin "C") (pinfunction "K_C") (pintype "bidirectional"))
      (node (ref "D244") (pin "C") (pinfunction "K_C") (pintype "bidirectional"))
      (node (ref "D260") (pin "C") (pinfunction "K_C") (pintype "bidirectional"))
      (node (ref "R55") (pin "2") (pinfunction "2_2") (pintype "passive"))
      (node (ref "RGB56") (pin "T") (pinfunction "PAD_T") (pintype "bidirectional"))
      (node (ref "RGB64") (pin "T") (pinfunction "PAD_T") (pintype "bidirectional"))
    )
    (net (code "46") (name "LGND") (class "Default")
      (node (ref "C1") (pin "-") (pinfunction "-_-") (pintype "passive"))
      (node (ref "C10") (pin "-") (pinfunction "-_-") (pintype "passive"))
      (node (ref "C19") (pin "-") (pinfunction "-_-") (pintype "passive"))
      (node (ref "J1") (pin "2") (pinfunction "P$3_2") (pintype "bidirectional"))
      (node (ref "P1") (pin "10") (pinfunction "10_10") (pintype "bidirectional"))
      (node (ref "P1") (pin "8") (pinfunction "8_8") (pintype "bidirectional"))
      (node (ref "P2") (pin "10") (pinfunction "10_10") (pintype "bidirectional"))
      (node (ref "P2") (pin "8") (pinfunction "8_8") (pintype "bidirectional"))
      (node (ref "P4") (pin "1") (pinfunction "1_1") (pintype "bidirectional"))
      (node (ref "P4") (pin "3") (pinfunction "3_3") (pintype "bidirectional"))
      (node (ref "R10") (pin "1") (pinfunction "1_1") (pintype "passive"))
      (node (ref "R11") (pin "1") (pinfunction "1_1") (pintype "passive"))
      (node (ref "R13") (pin "1") (pinfunction "1_1") (pintype "passive"))
      (node (ref "R17") (pin "1") (pinfunction "1_1") (pintype "passive"))
      (node (ref "R22") (pin "1") (pinfunction "1_1") (pintype "passive"))
      (node (ref "R24") (pin "1") (pinfunction "1_1") (pintype "passive"))
      (node (ref "R25") (pin "1") (pinfunction "1_1") (pintype "passive"))
      (node (ref "R27") (pin "1") (pinfunction "1_1") (pintype "passive"))
      (node (ref "R29") (pin "1") (pinfunction "1_1") (pintype "passive"))
      (node (ref "R3") (pin "1") (pinfunction "1_1") (pintype "passive"))
      (node (ref "R32") (pin "1") (pinfunction "1_1") (pintype "passive"))
      (node (ref "R37") (pin "1") (pinfunction "1_1") (pintype "passive"))
      (node (ref "R39") (pin "1") (pinfunction "1_1") (pintype "passive"))
      (node (ref "R41") (pin "1") (pinfunction "1_1") (pintype "passive"))
      (node (ref "R44") (pin "1") (pinfunction "1_1") (pintype "passive"))
      (node (ref "R45") (pin "1") (pinfunction "1_1") (pintype "passive"))
      (node (ref "R47") (pin "1") (pinfunction "1_1") (pintype "passive"))
      (node (ref "R5") (pin "1") (pinfunction "1_1") (pintype "passive"))
      (node (ref "R51") (pin "1") (pinfunction "1_1") (pintype "passive"))
      (node (ref "R56") (pin "1") (pinfunction "1_1") (pintype "passive"))
      (node (ref "R58") (pin "1") (pinfunction "1_1") (pintype "passive"))
      (node (ref "R59") (pin "1") (pinfunction "1_1") (pintype "passive"))
      (node (ref "R61") (pin "1") (pinfunction "1_1") (pintype "passive"))
      (node (ref "R63") (pin "1") (pinfunction "1_1") (pintype "passive"))
      (node (ref "R66") (pin "1") (pinfunction "1_1") (pintype "passive"))
      (node (ref "R7") (pin "1") (pinfunction "1_1") (pintype "passive"))
    )
    (net (code "47") (name "N$343") (class "Default")
      (node (ref "C6") (pin "2") (pinfunction "2_2") (pintype "passive"))
      (node (ref "D114") (pin "C") (pinfunction "K_C") (pintype "bidirectional"))
      (node (ref "D130") (pin "C") (pinfunction "K_C") (pintype "bidirectional"))
      (node (ref "D81") (pin "C") (pinfunction "K_C") (pintype "bidirectional"))
      (node (ref "D98") (pin "C") (pinfunction "K_C") (pintype "bidirectional"))
      (node (ref "R21") (pin "2") (pinfunction "2_2") (pintype "passive"))
      (node (ref "RGB24") (pin "T") (pinfunction "PAD_T") (pintype "bidirectional"))
      (node (ref "RGB32") (pin "T") (pinfunction "PAD_T") (pintype "bidirectional"))
    )
    (net (code "48") (name "Net-(C9-Pad2)") (class "Default")
      (node (ref "C9") (pin "2") (pinfunction "2_2") (pintype "passive"))
      (node (ref "L2") (pin "1") (pinfunction "1_1") (pintype "passive"))
      (node (ref "R21") (pin "1") (pinfunction "1_1") (pintype "passive"))
    )
    (net (code "49") (name "Net-(C18-Pad2)") (class "Default")
      (node (ref "C18") (pin "2") (pinfunction "2_2") (pintype "passive"))
      (node (ref "L4") (pin "1") (pinfunction "1_1") (pintype "passive"))
      (node (ref "R55") (pin "1") (pinfunction "1_1") (pintype "passive"))
    )
    (net (code "50") (name "Net-(D1-K)") (class "Default")
      (node (ref "D1") (pin "C") (pinfunction "K_C") (pintype "bidirectional"))
      (node (ref "D2") (pin "A") (pinfunction "A_A") (pintype "bidirectional"))
    )
    (net (code "51") (name "Net-(D2-K)") (class "Default")
      (node (ref "D2") (pin "C") (pinfunction "K_C") (pintype "bidirectional"))
      (node (ref "D3") (pin "A") (pinfunction "A_A") (pintype "bidirectional"))
    )
    (net (code "52") (name "Net-(D3-K)") (class "Default")
      (node (ref "D3") (pin "C") (pinfunction "K_C") (pintype "bidirectional"))
      (node (ref "D4") (pin "A") (pinfunction "A_A") (pintype "bidirectional"))
    )
    (net (code "53") (name "Net-(D4-K)") (class "Default")
      (node (ref "D4") (pin "C") (pinfunction "K_C") (pintype "bidirectional"))
      (node (ref "D5") (pin "A") (pinfunction "A_A") (pintype "bidirectional"))
    )
    (net (code "54") (name "Net-(D5-K)") (class "Default")
      (node (ref "D5") (pin "C") (pinfunction "K_C") (pintype "bidirectional"))
      (node (ref "D6") (pin "A") (pinfunction "A_A") (pintype "bidirectional"))
    )
    (net (code "55") (name "Net-(D6-K)") (class "Default")
      (node (ref "D6") (pin "C") (pinfunction "K_C") (pintype "bidirectional"))
      (node (ref "D7") (pin "A") (pinfunction "A_A") (pintype "bidirectional"))
    )
    (net (code "56") (name "Net-(D7-K)") (class "Default")
      (node (ref "D7") (pin "C") (pinfunction "K_C") (pintype "bidirectional"))
      (node (ref "D8") (pin "A") (pinfunction "A_A") (pintype "bidirectional"))
    )
    (net (code "57") (name "Net-(D8-K)") (class "Default")
      (node (ref "D8") (pin "C") (pinfunction "K_C") (pintype "bidirectional"))
      (node (ref "R1") (pin "2") (pinfunction "2_2") (pintype "passive"))
    )
    (net (code "58") (name "Net-(D9-K)") (class "Default")
      (node (ref "D10") (pin "A") (pinfunction "A_A") (pintype "bidirectional"))
      (node (ref "D9") (pin "C") (pinfunction "K_C") (pintype "bidirectional"))
    )
    (net (code "59") (name "Net-(D9-PadA)") (class "Default")
      (node (ref "D9") (pin "A") (pinfunction "A_A") (pintype "bidirectional"))
      (node (ref "R1") (pin "1") (pinfunction "1_1") (pintype "passive"))
    )
    (net (code "60") (name "Net-(D10-K)") (class "Default")
      (node (ref "D10") (pin "C") (pinfunction "K_C") (pintype "bidirectional"))
      (node (ref "D11") (pin "A") (pinfunction "A_A") (pintype "bidirectional"))
    )
    (net (code "61") (name "Net-(D11-K)") (class "Default")
      (node (ref "D11") (pin "C") (pinfunction "K_C") (pintype "bidirectional"))
      (node (ref "D12") (pin "A") (pinfunction "A_A") (pintype "bidirectional"))
    )
    (net (code "62") (name "Net-(D12-K)") (class "Default")
      (node (ref "D12") (pin "C") (pinfunction "K_C") (pintype "bidirectional"))
      (node (ref "D13") (pin "A") (pinfunction "A_A") (pintype "bidirectional"))
    )
    (net (code "63") (name "Net-(D13-K)") (class "Default")
      (node (ref "D13") (pin "C") (pinfunction "K_C") (pintype "bidirectional"))
      (node (ref "D14") (pin "A") (pinfunction "A_A") (pintype "bidirectional"))
    )
    (net (code "64") (name "Net-(D14-K)") (class "Default")
      (node (ref "D14") (pin "C") (pinfunction "K_C") (pintype "bidirectional"))
      (node (ref "D15") (pin "A") (pinfunction "A_A") (pintype "bidirectional"))
    )
    (net (code "65") (name "Net-(D15-K)") (class "Default")
      (node (ref "D15") (pin "C") (pinfunction "K_C") (pintype "bidirectional"))
      (node (ref "D16") (pin "A") (pinfunction "A_A") (pintype "bidirectional"))
    )
    (net (code "66") (name "Net-(D17-K)") (class "Default")
      (node (ref "D17") (pin "C") (pinfunction "K_C") (pintype "bidirectional"))
      (node (ref "D18") (pin "A") (pinfunction "A_A") (pintype "bidirectional"))
    )
    (net (code "67") (name "Net-(D18-K)") (class "Default")
      (node (ref "D18") (pin "C") (pinfunction "K_C") (pintype "bidirectional"))
      (node (ref "D19") (pin "A") (pinfunction "A_A") (pintype "bidirectional"))
    )
    (net (code "68") (name "Net-(D19-K)") (class "Default")
      (node (ref "D19") (pin "C") (pinfunction "K_C") (pintype "bidirectional"))
      (node (ref "D20") (pin "A") (pinfunction "A_A") (pintype "bidirectional"))
    )
    (net (code "69") (name "Net-(D20-K)") (class "Default")
      (node (ref "D20") (pin "C") (pinfunction "K_C") (pintype "bidirectional"))
      (node (ref "D21") (pin "A") (pinfunction "A_A") (pintype "bidirectional"))
    )
    (net (code "70") (name "Net-(D21-K)") (class "Default")
      (node (ref "D21") (pin "C") (pinfunction "K_C") (pintype "bidirectional"))
      (node (ref "D22") (pin "A") (pinfunction "A_A") (pintype "bidirectional"))
    )
    (net (code "71") (name "Net-(D22-K)") (class "Default")
      (node (ref "D22") (pin "C") (pinfunction "K_C") (pintype "bidirectional"))
      (node (ref "D23") (pin "A") (pinfunction "A_A") (pintype "bidirectional"))
    )
    (net (code "72") (name "Net-(D23-K)") (class "Default")
      (node (ref "D23") (pin "C") (pinfunction "K_C") (pintype "bidirectional"))
      (node (ref "D24") (pin "A") (pinfunction "A_A") (pintype "bidirectional"))
    )
    (net (code "73") (name "Net-(D24-K)") (class "Default")
      (node (ref "D24") (pin "C") (pinfunction "K_C") (pintype "bidirectional"))
      (node (ref "R4") (pin "2") (pinfunction "2_2") (pintype "passive"))
    )
    (net (code "74") (name "Net-(D25-K)") (class "Default")
      (node (ref "D25") (pin "C") (pinfunction "K_C") (pintype "bidirectional"))
      (node (ref "D26") (pin "A") (pinfunction "A_A") (pintype "bidirectional"))
    )
    (net (code "75") (name "Net-(D25-PadA)") (class "Default")
      (node (ref "D25") (pin "A") (pinfunction "A_A") (pintype "bidirectional"))
      (node (ref "R4") (pin "1") (pinfunction "1_1") (pintype "passive"))
    )
    (net (code "76") (name "Net-(D26-K)") (class "Default")
      (node (ref "D26") (pin "C") (pinfunction "K_C") (pintype "bidirectional"))
      (node (ref "D27") (pin "A") (pinfunction "A_A") (pintype "bidirectional"))
    )
    (net (code "77") (name "Net-(D27-K)") (class "Default")
      (node (ref "D27") (pin "C") (pinfunction "K_C") (pintype "bidirectional"))
      (node (ref "D28") (pin "A") (pinfunction "A_A") (pintype "bidirectional"))
    )
    (net (code "78") (name "Net-(D28-K)") (class "Default")
      (node (ref "D28") (pin "C") (pinfunction "K_C") (pintype "bidirectional"))
      (node (ref "D29") (pin "A") (pinfunction "A_A") (pintype "bidirectional"))
    )
    (net (code "79") (name "Net-(D29-K)") (class "Default")
      (node (ref "D29") (pin "C") (pinfunction "K_C") (pintype "bidirectional"))
      (node (ref "D30") (pin "A") (pinfunction "A_A") (pintype "bidirectional"))
    )
    (net (code "80") (name "Net-(D30-K)") (class "Default")
      (node (ref "D30") (pin "C") (pinfunction "K_C") (pintype "bidirectional"))
      (node (ref "D31") (pin "A") (pinfunction "A_A") (pintype "bidirectional"))
    )
    (net (code "81") (name "Net-(D31-K)") (class "Default")
      (node (ref "D31") (pin "C") (pinfunction "K_C") (pintype "bidirectional"))
      (node (ref "D32") (pin "A") (pinfunction "A_A") (pintype "bidirectional"))
    )
    (net (code "82") (name "Net-(D33-K)") (class "Default")
      (node (ref "D33") (pin "C") (pinfunction "K_C") (pintype "bidirectional"))
      (node (ref "D34") (pin "A") (pinfunction "A_A") (pintype "bidirectional"))
    )
    (net (code "83") (name "Net-(D34-K)") (class "Default")
      (node (ref "D34") (pin "C") (pinfunction "K_C") (pintype "bidirectional"))
      (node (ref "D35") (pin "A") (pinfunction "A_A") (pintype "bidirectional"))
    )
    (net (code "84") (name "Net-(D35-K)") (class "Default")
      (node (ref "D35") (pin "C") (pinfunction "K_C") (pintype "bidirectional"))
      (node (ref "D36") (pin "A") (pinfunction "A_A") (pintype "bidirectional"))
    )
    (net (code "85") (name "Net-(D36-K)") (class "Default")
      (node (ref "D36") (pin "C") (pinfunction "K_C") (pintype "bidirectional"))
      (node (ref "D37") (pin "A") (pinfunction "A_A") (pintype "bidirectional"))
    )
    (net (code "86") (name "Net-(D37-K)") (class "Default")
      (node (ref "D37") (pin "C") (pinfunction "K_C") (pintype "bidirectional"))
      (node (ref "D38") (pin "A") (pinfunction "A_A") (pintype "bidirectional"))
    )
    (net (code "87") (name "Net-(D38-K)") (class "Default")
      (node (ref "D38") (pin "C") (pinfunction "K_C") (pintype "bidirectional"))
      (node (ref "D39") (pin "A") (pinfunction "A_A") (pintype "bidirectional"))
    )
    (net (code "88") (name "Net-(D39-K)") (class "Default")
      (node (ref "D39") (pin "C") (pinfunction "K_C") (pintype "bidirectional"))
      (node (ref "D40") (pin "A") (pinfunction "A_A") (pintype "bidirectional"))
    )
    (net (code "89") (name "Net-(D40-K)") (class "Default")
      (node (ref "D40") (pin "C") (pinfunction "K_C") (pintype "bidirectional"))
      (node (ref "R9") (pin "2") (pinfunction "2_2") (pintype "passive"))
    )
    (net (code "90") (name "Net-(D41-K)") (class "Default")
      (node (ref "D41") (pin "C") (pinfunction "K_C") (pintype "bidirectional"))
      (node (ref "D42") (pin "A") (pinfunction "A_A") (pintype "bidirectional"))
    )
    (net (code "91") (name "Net-(D41-PadA)") (class "Default")
      (node (ref "D41") (pin "A") (pinfunction "A_A") (pintype "bidirectional"))
      (node (ref "R9") (pin "1") (pinfunction "1_1") (pintype "passive"))
    )
    (net (code "92") (name "Net-(D42-K)") (class "Default")
      (node (ref "D42") (pin "C") (pinfunction "K_C") (pintype "bidirectional"))
      (node (ref "D43") (pin "A") (pinfunction "A_A") (pintype "bidirectional"))
    )
    (net (code "93") (name "Net-(D43-K)") (class "Default")
      (node (ref "D43") (pin "C") (pinfunction "K_C") (pintype "bidirectional"))
      (node (ref "D44") (pin "A") (pinfunction "A_A") (pintype "bidirectional"))
    )
    (net (code "94") (name "Net-(D44-K)") (class "Default")
      (node (ref "D44") (pin "C") (pinfunction "K_C") (pintype "bidirectional"))
      (node (ref "D45") (pin "A") (pinfunction "A_A") (pintype "bidirectional"))
    )
    (net (code "95") (name "Net-(D45-K)") (class "Default")
      (node (ref "D45") (pin "C") (pinfunction "K_C") (pintype "bidirectional"))
      (node (ref "D46") (pin "A") (pinfunction "A_A") (pintype "bidirectional"))
    )
    (net (code "96") (name "Net-(D46-K)") (class "Default")
      (node (ref "D46") (pin "C") (pinfunction "K_C") (pintype "bidirectional"))
      (node (ref "D47") (pin "A") (pinfunction "A_A") (pintype "bidirectional"))
    )
    (net (code "97") (name "Net-(D47-K)") (class "Default")
      (node (ref "D47") (pin "C") (pinfunction "K_C") (pintype "bidirectional"))
      (node (ref "D48") (pin "A") (pinfunction "A_A") (pintype "bidirectional"))
    )
    (net (code "98") (name "Net-(D50-K)") (class "Default")
      (node (ref "D50") (pin "C") (pinfunction "K_C") (pintype "bidirectional"))
      (node (ref "D51") (pin "A") (pinfunction "A_A") (pintype "bidirectional"))
    )
    (net (code "99") (name "Net-(D51-K)") (class "Default")
      (node (ref "D51") (pin "C") (pinfunction "K_C") (pintype "bidirectional"))
      (node (ref "D52") (pin "A") (pinfunction "A_A") (pintype "bidirectional"))
    )
    (net (code "100") (name "Net-(D52-K)") (class "Default")
      (node (ref "D52") (pin "C") (pinfunction "K_C") (pintype "bidirectional"))
      (node (ref "D53") (pin "A") (pinfunction "A_A") (pintype "bidirectional"))
    )
    (net (code "101") (name "Net-(D53-K)") (class "Default")
      (node (ref "D53") (pin "C") (pinfunction "K_C") (pintype "bidirectional"))
      (node (ref "D54") (pin "A") (pinfunction "A_A") (pintype "bidirectional"))
    )
    (net (code "102") (name "Net-(D54-K)") (class "Default")
      (node (ref "D54") (pin "C") (pinfunction "K_C") (pintype "bidirectional"))
      (node (ref "D55") (pin "A") (pinfunction "A_A") (pintype "bidirectional"))
    )
    (net (code "103") (name "Net-(D55-K)") (class "Default")
      (node (ref "D55") (pin "C") (pinfunction "K_C") (pintype "bidirectional"))
      (node (ref "D56") (pin "A") (pinfunction "A_A") (pintype "bidirectional"))
    )
    (net (code "104") (name "Net-(D56-K)") (class "Default")
      (node (ref "D56") (pin "C") (pinfunction "K_C") (pintype "bidirectional"))
      (node (ref "D57") (pin "A") (pinfunction "A_A") (pintype "bidirectional"))
    )
    (net (code "105") (name "Net-(D57-K)") (class "Default")
      (node (ref "D57") (pin "C") (pinfunction "K_C") (pintype "bidirectional"))
      (node (ref "R12") (pin "2") (pinfunction "2_2") (pintype "passive"))
    )
    (net (code "106") (name "Net-(D58-K)") (class "Default")
      (node (ref "D58") (pin "C") (pinfunction "K_C") (pintype "bidirectional"))
      (node (ref "D59") (pin "A") (pinfunction "A_A") (pintype "bidirectional"))
    )
    (net (code "107") (name "Net-(D58-PadA)") (class "Default")
      (node (ref "D58") (pin "A") (pinfunction "A_A") (pintype "bidirectional"))
      (node (ref "R12") (pin "1") (pinfunction "1_1") (pintype "passive"))
    )
    (net (code "108") (name "Net-(D59-K)") (class "Default")
      (node (ref "D59") (pin "C") (pinfunction "K_C") (pintype "bidirectional"))
      (node (ref "D60") (pin "A") (pinfunction "A_A") (pintype "bidirectional"))
    )
    (net (code "109") (name "Net-(D60-K)") (class "Default")
      (node (ref "D60") (pin "C") (pinfunction "K_C") (pintype "bidirectional"))
      (node (ref "D61") (pin "A") (pinfunction "A_A") (pintype "bidirectional"))
    )
    (net (code "110") (name "Net-(D61-K)") (class "Default")
      (node (ref "D61") (pin "C") (pinfunction "K_C") (pintype "bidirectional"))
      (node (ref "D62") (pin "A") (pinfunction "A_A") (pintype "bidirectional"))
    )
    (net (code "111") (name "Net-(D62-K)") (class "Default")
      (node (ref "D62") (pin "C") (pinfunction "K_C") (pintype "bidirectional"))
      (node (ref "D63") (pin "A") (pinfunction "A_A") (pintype "bidirectional"))
    )
    (net (code "112") (name "Net-(D63-K)") (class "Default")
      (node (ref "D63") (pin "C") (pinfunction "K_C") (pintype "bidirectional"))
      (node (ref "D64") (pin "A") (pinfunction "A_A") (pintype "bidirectional"))
    )
    (net (code "113") (name "Net-(D64-K)") (class "Default")
      (node (ref "D64") (pin "C") (pinfunction "K_C") (pintype "bidirectional"))
      (node (ref "D65") (pin "A") (pinfunction "A_A") (pintype "bidirectional"))
    )
    (net (code "114") (name "Net-(D66-K)") (class "Default")
      (node (ref "D66") (pin "C") (pinfunction "K_C") (pintype "bidirectional"))
      (node (ref "D67") (pin "A") (pinfunction "A_A") (pintype "bidirectional"))
    )
    (net (code "115") (name "Net-(D67-K)") (class "Default")
      (node (ref "D67") (pin "C") (pinfunction "K_C") (pintype "bidirectional"))
      (node (ref "D68") (pin "A") (pinfunction "A_A") (pintype "bidirectional"))
    )
    (net (code "116") (name "Net-(D68-K)") (class "Default")
      (node (ref "D68") (pin "C") (pinfunction "K_C") (pintype "bidirectional"))
      (node (ref "D69") (pin "A") (pinfunction "A_A") (pintype "bidirectional"))
    )
    (net (code "117") (name "Net-(D69-K)") (class "Default")
      (node (ref "D69") (pin "C") (pinfunction "K_C") (pintype "bidirectional"))
      (node (ref "D70") (pin "A") (pinfunction "A_A") (pintype "bidirectional"))
    )
    (net (code "118") (name "Net-(D70-K)") (class "Default")
      (node (ref "D70") (pin "C") (pinfunction "K_C") (pintype "bidirectional"))
      (node (ref "D71") (pin "A") (pinfunction "A_A") (pintype "bidirectional"))
    )
    (net (code "119") (name "Net-(D71-K)") (class "Default")
      (node (ref "D71") (pin "C") (pinfunction "K_C") (pintype "bidirectional"))
      (node (ref "D72") (pin "A") (pinfunction "A_A") (pintype "bidirectional"))
    )
    (net (code "120") (name "Net-(D72-K)") (class "Default")
      (node (ref "D72") (pin "C") (pinfunction "K_C") (pintype "bidirectional"))
      (node (ref "D73") (pin "A") (pinfunction "A_A") (pintype "bidirectional"))
    )
    (net (code "121") (name "Net-(D73-K)") (class "Default")
      (node (ref "D73") (pin "C") (pinfunction "K_C") (pintype "bidirectional"))
      (node (ref "R23") (pin "2") (pinfunction "2_2") (pintype "passive"))
    )
    (net (code "122") (name "Net-(D74-K)") (class "Default")
      (node (ref "D74") (pin "C") (pinfunction "K_C") (pintype "bidirectional"))
      (node (ref "D75") (pin "A") (pinfunction "A_A") (pintype "bidirectional"))
    )
    (net (code "123") (name "Net-(D74-PadA)") (class "Default")
      (node (ref "D74") (pin "A") (pinfunction "A_A") (pintype "bidirectional"))
      (node (ref "R23") (pin "1") (pinfunction "1_1") (pintype "passive"))
    )
    (net (code "124") (name "Net-(D75-K)") (class "Default")
      (node (ref "D75") (pin "C") (pinfunction "K_C") (pintype "bidirectional"))
      (node (ref "D76") (pin "A") (pinfunction "A_A") (pintype "bidirectional"))
    )
    (net (code "125") (name "Net-(D76-K)") (class "Default")
      (node (ref "D76") (pin "C") (pinfunction "K_C") (pintype "bidirectional"))
      (node (ref "D77") (pin "A") (pinfunction "A_A") (pintype "bidirectional"))
    )
    (net (code "126") (name "Net-(D77-K)") (class "Default")
      (node (ref "D77") (pin "C") (pinfunction "K_C") (pintype "bidirectional"))
      (node (ref "D78") (pin "A") (pinfunction "A_A") (pintype "bidirectional"))
    )
    (net (code "127") (name "Net-(D78-K)") (class "Default")
      (node (ref "D78") (pin "C") (pinfunction "K_C") (pintype "bidirectional"))
      (node (ref "D79") (pin "A") (pinfunction "A_A") (pintype "bidirectional"))
    )
    (net (code "128") (name "Net-(D79-K)") (class "Default")
      (node (ref "D79") (pin "C") (pinfunction "K_C") (pintype "bidirectional"))
      (node (ref "D80") (pin "A") (pinfunction "A_A") (pintype "bidirectional"))
    )
    (net (code "129") (name "Net-(D80-K)") (class "Default")
      (node (ref "D80") (pin "C") (pinfunction "K_C") (pintype "bidirectional"))
      (node (ref "D81") (pin "A") (pinfunction "A_A") (pintype "bidirectional"))
    )
    (net (code "130") (name "Net-(D83-K)") (class "Default")
      (node (ref "D83") (pin "C") (pinfunction "K_C") (pintype "bidirectional"))
      (node (ref "D84") (pin "A") (pinfunction "A_A") (pintype "bidirectional"))
    )
    (net (code "131") (name "Net-(D84-K)") (class "Default")
      (node (ref "D84") (pin "C") (pinfunction "K_C") (pintype "bidirectional"))
      (node (ref "D85") (pin "A") (pinfunction "A_A") (pintype "bidirectional"))
    )
    (net (code "132") (name "Net-(D85-K)") (class "Default")
      (node (ref "D85") (pin "C") (pinfunction "K_C") (pintype "bidirectional"))
      (node (ref "D86") (pin "A") (pinfunction "A_A") (pintype "bidirectional"))
    )
    (net (code "133") (name "Net-(D86-K)") (class "Default")
      (node (ref "D86") (pin "C") (pinfunction "K_C") (pintype "bidirectional"))
      (node (ref "D87") (pin "A") (pinfunction "A_A") (pintype "bidirectional"))
    )
    (net (code "134") (name "Net-(D87-K)") (class "Default")
      (node (ref "D87") (pin "C") (pinfunction "K_C") (pintype "bidirectional"))
      (node (ref "D88") (pin "A") (pinfunction "A_A") (pintype "bidirectional"))
    )
    (net (code "135") (name "Net-(D88-K)") (class "Default")
      (node (ref "D88") (pin "C") (pinfunction "K_C") (pintype "bidirectional"))
      (node (ref "D89") (pin "A") (pinfunction "A_A") (pintype "bidirectional"))
    )
    (net (code "136") (name "Net-(D89-K)") (class "Default")
      (node (ref "D89") (pin "C") (pinfunction "K_C") (pintype "bidirectional"))
      (node (ref "D90") (pin "A") (pinfunction "A_A") (pintype "bidirectional"))
    )
    (net (code "137") (name "Net-(D90-K)") (class "Default")
      (node (ref "D90") (pin "C") (pinfunction "K_C") (pintype "bidirectional"))
      (node (ref "R26") (pin "2") (pinfunction "2_2") (pintype "passive"))
    )
    (net (code "138") (name "Net-(D91-K)") (class "Default")
      (node (ref "D91") (pin "C") (pinfunction "K_C") (pintype "bidirectional"))
      (node (ref "D92") (pin "A") (pinfunction "A_A") (pintype "bidirectional"))
    )
    (net (code "139") (name "Net-(D91-PadA)") (class "Default")
      (node (ref "D91") (pin "A") (pinfunction "A_A") (pintype "bidirectional"))
      (node (ref "R26") (pin "1") (pinfunction "1_1") (pintype "passive"))
    )
    (net (code "140") (name "Net-(D92-K)") (class "Default")
      (node (ref "D92") (pin "C") (pinfunction "K_C") (pintype "bidirectional"))
      (node (ref "D93") (pin "A") (pinfunction "A_A") (pintype "bidirectional"))
    )
    (net (code "141") (name "Net-(D93-K)") (class "Default")
      (node (ref "D93") (pin "C") (pinfunction "K_C") (pintype "bidirectional"))
      (node (ref "D94") (pin "A") (pinfunction "A_A") (pintype "bidirectional"))
    )
    (net (code "142") (name "Net-(D94-K)") (class "Default")
      (node (ref "D94") (pin "C") (pinfunction "K_C") (pintype "bidirectional"))
      (node (ref "D95") (pin "A") (pinfunction "A_A") (pintype "bidirectional"))
    )
    (net (code "143") (name "Net-(D95-K)") (class "Default")
      (node (ref "D95") (pin "C") (pinfunction "K_C") (pintype "bidirectional"))
      (node (ref "D96") (pin "A") (pinfunction "A_A") (pintype "bidirectional"))
    )
    (net (code "144") (name "Net-(D96-K)") (class "Default")
      (node (ref "D96") (pin "C") (pinfunction "K_C") (pintype "bidirectional"))
      (node (ref "D97") (pin "A") (pinfunction "A_A") (pintype "bidirectional"))
    )
    (net (code "145") (name "Net-(D97-K)") (class "Default")
      (node (ref "D97") (pin "C") (pinfunction "K_C") (pintype "bidirectional"))
      (node (ref "D98") (pin "A") (pinfunction "A_A") (pintype "bidirectional"))
    )
    (net (code "146") (name "Net-(D99-K)") (class "Default")
      (node (ref "D100") (pin "A") (pinfunction "A_A") (pintype "bidirectional"))
      (node (ref "D99") (pin "C") (pinfunction "K_C") (pintype "bidirectional"))
    )
    (net (code "147") (name "Net-(D100-K)") (class "Default")
      (node (ref "D100") (pin "C") (pinfunction "K_C") (pintype "bidirectional"))
      (node (ref "D101") (pin "A") (pinfunction "A_A") (pintype "bidirectional"))
    )
    (net (code "148") (name "Net-(D101-K)") (class "Default")
      (node (ref "D101") (pin "C") (pinfunction "K_C") (pintype "bidirectional"))
      (node (ref "D102") (pin "A") (pinfunction "A_A") (pintype "bidirectional"))
    )
    (net (code "149") (name "Net-(D102-K)") (class "Default")
      (node (ref "D102") (pin "C") (pinfunction "K_C") (pintype "bidirectional"))
      (node (ref "D103") (pin "A") (pinfunction "A_A") (pintype "bidirectional"))
    )
    (net (code "150") (name "Net-(D103-K)") (class "Default")
      (node (ref "D103") (pin "C") (pinfunction "K_C") (pintype "bidirectional"))
      (node (ref "D104") (pin "A") (pinfunction "A_A") (pintype "bidirectional"))
    )
    (net (code "151") (name "Net-(D104-K)") (class "Default")
      (node (ref "D104") (pin "C") (pinfunction "K_C") (pintype "bidirectional"))
      (node (ref "D105") (pin "A") (pinfunction "A_A") (pintype "bidirectional"))
    )
    (net (code "152") (name "Net-(D105-K)") (class "Default")
      (node (ref "D105") (pin "C") (pinfunction "K_C") (pintype "bidirectional"))
      (node (ref "D106") (pin "A") (pinfunction "A_A") (pintype "bidirectional"))
    )
    (net (code "153") (name "Net-(D106-K)") (class "Default")
      (node (ref "D106") (pin "C") (pinfunction "K_C") (pintype "bidirectional"))
      (node (ref "R30") (pin "2") (pinfunction "2_2") (pintype "passive"))
    )
    (net (code "154") (name "Net-(D107-K)") (class "Default")
      (node (ref "D107") (pin "C") (pinfunction "K_C") (pintype "bidirectional"))
      (node (ref "D108") (pin "A") (pinfunction "A_A") (pintype "bidirectional"))
    )
    (net (code "155") (name "Net-(D107-PadA)") (class "Default")
      (node (ref "D107") (pin "A") (pinfunction "A_A") (pintype "bidirectional"))
      (node (ref "R30") (pin "1") (pinfunction "1_1") (pintype "passive"))
    )
    (net (code "156") (name "Net-(D108-K)") (class "Default")
      (node (ref "D108") (pin "C") (pinfunction "K_C") (pintype "bidirectional"))
      (node (ref "D109") (pin "A") (pinfunction "A_A") (pintype "bidirectional"))
    )
    (net (code "157") (name "Net-(D109-K)") (class "Default")
      (node (ref "D109") (pin "C") (pinfunction "K_C") (pintype "bidirectional"))
      (node (ref "D110") (pin "A") (pinfunction "A_A") (pintype "bidirectional"))
    )
    (net (code "158") (name "Net-(D110-K)") (class "Default")
      (node (ref "D110") (pin "C") (pinfunction "K_C") (pintype "bidirectional"))
      (node (ref "D111") (pin "A") (pinfunction "A_A") (pintype "bidirectional"))
    )
    (net (code "159") (name "Net-(D111-K)") (class "Default")
      (node (ref "D111") (pin "C") (pinfunction "K_C") (pintype "bidirectional"))
      (node (ref "D112") (pin "A") (pinfunction "A_A") (pintype "bidirectional"))
    )
    (net (code "160") (name "Net-(D112-K)") (class "Default")
      (node (ref "D112") (pin "C") (pinfunction "K_C") (pintype "bidirectional"))
      (node (ref "D113") (pin "A") (pinfunction "A_A") (pintype "bidirectional"))
    )
    (net (code "161") (name "Net-(D113-K)") (class "Default")
      (node (ref "D113") (pin "C") (pinfunction "K_C") (pintype "bidirectional"))
      (node (ref "D114") (pin "A") (pinfunction "A_A") (pintype "bidirectional"))
    )
    (net (code "162") (name "Net-(D115-K)") (class "Default")
      (node (ref "D115") (pin "C") (pinfunction "K_C") (pintype "bidirectional"))
      (node (ref "D116") (pin "A") (pinfunction "A_A") (pintype "bidirectional"))
    )
    (net (code "163") (name "Net-(D116-K)") (class "Default")
      (node (ref "D116") (pin "C") (pinfunction "K_C") (pintype "bidirectional"))
      (node (ref "D117") (pin "A") (pinfunction "A_A") (pintype "bidirectional"))
    )
    (net (code "164") (name "Net-(D117-K)") (class "Default")
      (node (ref "D117") (pin "C") (pinfunction "K_C") (pintype "bidirectional"))
      (node (ref "D118") (pin "A") (pinfunction "A_A") (pintype "bidirectional"))
    )
    (net (code "165") (name "Net-(D118-K)") (class "Default")
      (node (ref "D118") (pin "C") (pinfunction "K_C") (pintype "bidirectional"))
      (node (ref "D119") (pin "A") (pinfunction "A_A") (pintype "bidirectional"))
    )
    (net (code "166") (name "Net-(D119-K)") (class "Default")
      (node (ref "D119") (pin "C") (pinfunction "K_C") (pintype "bidirectional"))
      (node (ref "D120") (pin "A") (pinfunction "A_A") (pintype "bidirectional"))
    )
    (net (code "167") (name "Net-(D120-K)") (class "Default")
      (node (ref "D120") (pin "C") (pinfunction "K_C") (pintype "bidirectional"))
      (node (ref "D121") (pin "A") (pinfunction "A_A") (pintype "bidirectional"))
    )
    (net (code "168") (name "Net-(D121-K)") (class "Default")
      (node (ref "D121") (pin "C") (pinfunction "K_C") (pintype "bidirectional"))
      (node (ref "D122") (pin "A") (pinfunction "A_A") (pintype "bidirectional"))
    )
    (net (code "169") (name "Net-(D122-K)") (class "Default")
      (node (ref "D122") (pin "C") (pinfunction "K_C") (pintype "bidirectional"))
      (node (ref "R34") (pin "2") (pinfunction "2_2") (pintype "passive"))
    )
    (net (code "170") (name "Net-(D123-K)") (class "Default")
      (node (ref "D123") (pin "C") (pinfunction "K_C") (pintype "bidirectional"))
      (node (ref "D124") (pin "A") (pinfunction "A_A") (pintype "bidirectional"))
    )
    (net (code "171") (name "Net-(D123-PadA)") (class "Default")
      (node (ref "D123") (pin "A") (pinfunction "A_A") (pintype "bidirectional"))
      (node (ref "R34") (pin "1") (pinfunction "1_1") (pintype "passive"))
    )
    (net (code "172") (name "Net-(D124-K)") (class "Default")
      (node (ref "D124") (pin "C") (pinfunction "K_C") (pintype "bidirectional"))
      (node (ref "D125") (pin "A") (pinfunction "A_A") (pintype "bidirectional"))
    )
    (net (code "173") (name "Net-(D125-K)") (class "Default")
      (node (ref "D125") (pin "C") (pinfunction "K_C") (pintype "bidirectional"))
      (node (ref "D126") (pin "A") (pinfunction "A_A") (pintype "bidirectional"))
    )
    (net (code "174") (name "Net-(D126-K)") (class "Default")
      (node (ref "D126") (pin "C") (pinfunction "K_C") (pintype "bidirectional"))
      (node (ref "D127") (pin "A") (pinfunction "A_A") (pintype "bidirectional"))
    )
    (net (code "175") (name "Net-(D127-K)") (class "Default")
      (node (ref "D127") (pin "C") (pinfunction "K_C") (pintype "bidirectional"))
      (node (ref "D128") (pin "A") (pinfunction "A_A") (pintype "bidirectional"))
    )
    (net (code "176") (name "Net-(D128-K)") (class "Default")
      (node (ref "D128") (pin "C") (pinfunction "K_C") (pintype "bidirectional"))
      (node (ref "D129") (pin "A") (pinfunction "A_A") (pintype "bidirectional"))
    )
    (net (code "177") (name "Net-(D129-K)") (class "Default")
      (node (ref "D129") (pin "C") (pinfunction "K_C") (pintype "bidirectional"))
      (node (ref "D130") (pin "A") (pinfunction "A_A") (pintype "bidirectional"))
    )
    (net (code "178") (name "Net-(D131-K)") (class "Default")
      (node (ref "D131") (pin "C") (pinfunction "K_C") (pintype "bidirectional"))
      (node (ref "D132") (pin "A") (pinfunction "A_A") (pintype "bidirectional"))
    )
    (net (code "179") (name "Net-(D132-K)") (class "Default")
      (node (ref "D132") (pin "C") (pinfunction "K_C") (pintype "bidirectional"))
      (node (ref "D133") (pin "A") (pinfunction "A_A") (pintype "bidirectional"))
    )
    (net (code "180") (name "Net-(D133-K)") (class "Default")
      (node (ref "D133") (pin "C") (pinfunction "K_C") (pintype "bidirectional"))
      (node (ref "D134") (pin "A") (pinfunction "A_A") (pintype "bidirectional"))
    )
    (net (code "181") (name "Net-(D134-K)") (class "Default")
      (node (ref "D134") (pin "C") (pinfunction "K_C") (pintype "bidirectional"))
      (node (ref "D135") (pin "A") (pinfunction "A_A") (pintype "bidirectional"))
    )
    (net (code "182") (name "Net-(D135-K)") (class "Default")
      (node (ref "D135") (pin "C") (pinfunction "K_C") (pintype "bidirectional"))
      (node (ref "D136") (pin "A") (pinfunction "A_A") (pintype "bidirectional"))
    )
    (net (code "183") (name "Net-(D136-K)") (class "Default")
      (node (ref "D136") (pin "C") (pinfunction "K_C") (pintype "bidirectional"))
      (node (ref "D137") (pin "A") (pinfunction "A_A") (pintype "bidirectional"))
    )
    (net (code "184") (name "Net-(D137-K)") (class "Default")
      (node (ref "D137") (pin "C") (pinfunction "K_C") (pintype "bidirectional"))
      (node (ref "D138") (pin "A") (pinfunction "A_A") (pintype "bidirectional"))
    )
    (net (code "185") (name "Net-(D138-K)") (class "Default")
      (node (ref "D138") (pin "C") (pinfunction "K_C") (pintype "bidirectional"))
      (node (ref "R35") (pin "2") (pinfunction "2_2") (pintype "passive"))
    )
    (net (code "186") (name "Net-(D139-K)") (class "Default")
      (node (ref "D139") (pin "C") (pinfunction "K_C") (pintype "bidirectional"))
      (node (ref "D140") (pin "A") (pinfunction "A_A") (pintype "bidirectional"))
    )
    (net (code "187") (name "Net-(D139-PadA)") (class "Default")
      (node (ref "D139") (pin "A") (pinfunction "A_A") (pintype "bidirectional"))
      (node (ref "R35") (pin "1") (pinfunction "1_1") (pintype "passive"))
    )
    (net (code "188") (name "Net-(D140-K)") (class "Default")
      (node (ref "D140") (pin "C") (pinfunction "K_C") (pintype "bidirectional"))
      (node (ref "D141") (pin "A") (pinfunction "A_A") (pintype "bidirectional"))
    )
    (net (code "189") (name "Net-(D141-K)") (class "Default")
      (node (ref "D141") (pin "C") (pinfunction "K_C") (pintype "bidirectional"))
      (node (ref "D142") (pin "A") (pinfunction "A_A") (pintype "bidirectional"))
    )
    (net (code "190") (name "Net-(D142-K)") (class "Default")
      (node (ref "D142") (pin "C") (pinfunction "K_C") (pintype "bidirectional"))
      (node (ref "D143") (pin "A") (pinfunction "A_A") (pintype "bidirectional"))
    )
    (net (code "191") (name "Net-(D143-K)") (class "Default")
      (node (ref "D143") (pin "C") (pinfunction "K_C") (pintype "bidirectional"))
      (node (ref "D144") (pin "A") (pinfunction "A_A") (pintype "bidirectional"))
    )
    (net (code "192") (name "Net-(D144-K)") (class "Default")
      (node (ref "D144") (pin "C") (pinfunction "K_C") (pintype "bidirectional"))
      (node (ref "D145") (pin "A") (pinfunction "A_A") (pintype "bidirectional"))
    )
    (net (code "193") (name "Net-(D145-K)") (class "Default")
      (node (ref "D145") (pin "C") (pinfunction "K_C") (pintype "bidirectional"))
      (node (ref "D146") (pin "A") (pinfunction "A_A") (pintype "bidirectional"))
    )
    (net (code "194") (name "Net-(D147-K)") (class "Default")
      (node (ref "D147") (pin "C") (pinfunction "K_C") (pintype "bidirectional"))
      (node (ref "D148") (pin "A") (pinfunction "A_A") (pintype "bidirectional"))
    )
    (net (code "195") (name "Net-(D148-K)") (class "Default")
      (node (ref "D148") (pin "C") (pinfunction "K_C") (pintype "bidirectional"))
      (node (ref "D149") (pin "A") (pinfunction "A_A") (pintype "bidirectional"))
    )
    (net (code "196") (name "Net-(D149-K)") (class "Default")
      (node (ref "D149") (pin "C") (pinfunction "K_C") (pintype "bidirectional"))
      (node (ref "D150") (pin "A") (pinfunction "A_A") (pintype "bidirectional"))
    )
    (net (code "197") (name "Net-(D150-K)") (class "Default")
      (node (ref "D150") (pin "C") (pinfunction "K_C") (pintype "bidirectional"))
      (node (ref "D151") (pin "A") (pinfunction "A_A") (pintype "bidirectional"))
    )
    (net (code "198") (name "Net-(D151-K)") (class "Default")
      (node (ref "D151") (pin "C") (pinfunction "K_C") (pintype "bidirectional"))
      (node (ref "D152") (pin "A") (pinfunction "A_A") (pintype "bidirectional"))
    )
    (net (code "199") (name "Net-(D152-K)") (class "Default")
      (node (ref "D152") (pin "C") (pinfunction "K_C") (pintype "bidirectional"))
      (node (ref "D153") (pin "A") (pinfunction "A_A") (pintype "bidirectional"))
    )
    (net (code "200") (name "Net-(D153-K)") (class "Default")
      (node (ref "D153") (pin "C") (pinfunction "K_C") (pintype "bidirectional"))
      (node (ref "D154") (pin "A") (pinfunction "A_A") (pintype "bidirectional"))
    )
    (net (code "201") (name "Net-(D154-K)") (class "Default")
      (node (ref "D154") (pin "C") (pinfunction "K_C") (pintype "bidirectional"))
      (node (ref "R38") (pin "2") (pinfunction "2_2") (pintype "passive"))
    )
    (net (code "202") (name "Net-(D155-K)") (class "Default")
      (node (ref "D155") (pin "C") (pinfunction "K_C") (pintype "bidirectional"))
      (node (ref "D156") (pin "A") (pinfunction "A_A") (pintype "bidirectional"))
    )
    (net (code "203") (name "Net-(D155-PadA)") (class "Default")
      (node (ref "D155") (pin "A") (pinfunction "A_A") (pintype "bidirectional"))
      (node (ref "R38") (pin "1") (pinfunction "1_1") (pintype "passive"))
    )
    (net (code "204") (name "Net-(D156-K)") (class "Default")
      (node (ref "D156") (pin "C") (pinfunction "K_C") (pintype "bidirectional"))
      (node (ref "D157") (pin "A") (pinfunction "A_A") (pintype "bidirectional"))
    )
    (net (code "205") (name "Net-(D157-K)") (class "Default")
      (node (ref "D157") (pin "C") (pinfunction "K_C") (pintype "bidirectional"))
      (node (ref "D158") (pin "A") (pinfunction "A_A") (pintype "bidirectional"))
    )
    (net (code "206") (name "Net-(D158-K)") (class "Default")
      (node (ref "D158") (pin "C") (pinfunction "K_C") (pintype "bidirectional"))
      (node (ref "D159") (pin "A") (pinfunction "A_A") (pintype "bidirectional"))
    )
    (net (code "207") (name "Net-(D159-K)") (class "Default")
      (node (ref "D159") (pin "C") (pinfunction "K_C") (pintype "bidirectional"))
      (node (ref "D160") (pin "A") (pinfunction "A_A") (pintype "bidirectional"))
    )
    (net (code "208") (name "Net-(D160-K)") (class "Default")
      (node (ref "D160") (pin "C") (pinfunction "K_C") (pintype "bidirectional"))
      (node (ref "D161") (pin "A") (pinfunction "A_A") (pintype "bidirectional"))
    )
    (net (code "209") (name "Net-(D161-K)") (class "Default")
      (node (ref "D161") (pin "C") (pinfunction "K_C") (pintype "bidirectional"))
      (node (ref "D162") (pin "A") (pinfunction "A_A") (pintype "bidirectional"))
    )
    (net (code "210") (name "Net-(D163-K)") (class "Default")
      (node (ref "D163") (pin "C") (pinfunction "K_C") (pintype "bidirectional"))
      (node (ref "D164") (pin "A") (pinfunction "A_A") (pintype "bidirectional"))
    )
    (net (code "211") (name "Net-(D164-K)") (class "Default")
      (node (ref "D164") (pin "C") (pinfunction "K_C") (pintype "bidirectional"))
      (node (ref "D165") (pin "A") (pinfunction "A_A") (pintype "bidirectional"))
    )
    (net (code "212") (name "Net-(D165-K)") (class "Default")
      (node (ref "D165") (pin "C") (pinfunction "K_C") (pintype "bidirectional"))
      (node (ref "D166") (pin "A") (pinfunction "A_A") (pintype "bidirectional"))
    )
    (net (code "213") (name "Net-(D166-K)") (class "Default")
      (node (ref "D166") (pin "C") (pinfunction "K_C") (pintype "bidirectional"))
      (node (ref "D167") (pin "A") (pinfunction "A_A") (pintype "bidirectional"))
    )
    (net (code "214") (name "Net-(D167-K)") (class "Default")
      (node (ref "D167") (pin "C") (pinfunction "K_C") (pintype "bidirectional"))
      (node (ref "D168") (pin "A") (pinfunction "A_A") (pintype "bidirectional"))
    )
    (net (code "215") (name "Net-(D168-K)") (class "Default")
      (node (ref "D168") (pin "C") (pinfunction "K_C") (pintype "bidirectional"))
      (node (ref "D169") (pin "A") (pinfunction "A_A") (pintype "bidirectional"))
    )
    (net (code "216") (name "Net-(D169-K)") (class "Default")
      (node (ref "D169") (pin "C") (pinfunction "K_C") (pintype "bidirectional"))
      (node (ref "D170") (pin "A") (pinfunction "A_A") (pintype "bidirectional"))
    )
    (net (code "217") (name "Net-(D170-K)") (class "Default")
      (node (ref "D170") (pin "C") (pinfunction "K_C") (pintype "bidirectional"))
      (node (ref "R43") (pin "2") (pinfunction "2_2") (pintype "passive"))
    )
    (net (code "218") (name "Net-(D171-K)") (class "Default")
      (node (ref "D171") (pin "C") (pinfunction "K_C") (pintype "bidirectional"))
      (node (ref "D172") (pin "A") (pinfunction "A_A") (pintype "bidirectional"))
    )
    (net (code "219") (name "Net-(D171-PadA)") (class "Default")
      (node (ref "D171") (pin "A") (pinfunction "A_A") (pintype "bidirectional"))
      (node (ref "R43") (pin "1") (pinfunction "1_1") (pintype "passive"))
    )
    (net (code "220") (name "Net-(D172-K)") (class "Default")
      (node (ref "D172") (pin "C") (pinfunction "K_C") (pintype "bidirectional"))
      (node (ref "D173") (pin "A") (pinfunction "A_A") (pintype "bidirectional"))
    )
    (net (code "221") (name "Net-(D173-K)") (class "Default")
      (node (ref "D173") (pin "C") (pinfunction "K_C") (pintype "bidirectional"))
      (node (ref "D174") (pin "A") (pinfunction "A_A") (pintype "bidirectional"))
    )
    (net (code "222") (name "Net-(D174-K)") (class "Default")
      (node (ref "D174") (pin "C") (pinfunction "K_C") (pintype "bidirectional"))
      (node (ref "D175") (pin "A") (pinfunction "A_A") (pintype "bidirectional"))
    )
    (net (code "223") (name "Net-(D175-K)") (class "Default")
      (node (ref "D175") (pin "C") (pinfunction "K_C") (pintype "bidirectional"))
      (node (ref "D176") (pin "A") (pinfunction "A_A") (pintype "bidirectional"))
    )
    (net (code "224") (name "Net-(D176-K)") (class "Default")
      (node (ref "D176") (pin "C") (pinfunction "K_C") (pintype "bidirectional"))
      (node (ref "D177") (pin "A") (pinfunction "A_A") (pintype "bidirectional"))
    )
    (net (code "225") (name "Net-(D177-K)") (class "Default")
      (node (ref "D177") (pin "C") (pinfunction "K_C") (pintype "bidirectional"))
      (node (ref "D178") (pin "A") (pinfunction "A_A") (pintype "bidirectional"))
    )
    (net (code "226") (name "Net-(D180-K)") (class "Default")
      (node (ref "D180") (pin "C") (pinfunction "K_C") (pintype "bidirectional"))
      (node (ref "D181") (pin "A") (pinfunction "A_A") (pintype "bidirectional"))
    )
    (net (code "227") (name "Net-(D181-K)") (class "Default")
      (node (ref "D181") (pin "C") (pinfunction "K_C") (pintype "bidirectional"))
      (node (ref "D182") (pin "A") (pinfunction "A_A") (pintype "bidirectional"))
    )
    (net (code "228") (name "Net-(D182-K)") (class "Default")
      (node (ref "D182") (pin "C") (pinfunction "K_C") (pintype "bidirectional"))
      (node (ref "D183") (pin "A") (pinfunction "A_A") (pintype "bidirectional"))
    )
    (net (code "229") (name "Net-(D183-K)") (class "Default")
      (node (ref "D183") (pin "C") (pinfunction "K_C") (pintype "bidirectional"))
      (node (ref "D184") (pin "A") (pinfunction "A_A") (pintype "bidirectional"))
    )
    (net (code "230") (name "Net-(D184-K)") (class "Default")
      (node (ref "D184") (pin "C") (pinfunction "K_C") (pintype "bidirectional"))
      (node (ref "D185") (pin "A") (pinfunction "A_A") (pintype "bidirectional"))
    )
    (net (code "231") (name "Net-(D185-K)") (class "Default")
      (node (ref "D185") (pin "C") (pinfunction "K_C") (pintype "bidirectional"))
      (node (ref "D186") (pin "A") (pinfunction "A_A") (pintype "bidirectional"))
    )
    (net (code "232") (name "Net-(D186-K)") (class "Default")
      (node (ref "D186") (pin "C") (pinfunction "K_C") (pintype "bidirectional"))
      (node (ref "D187") (pin "A") (pinfunction "A_A") (pintype "bidirectional"))
    )
    (net (code "233") (name "Net-(D187-K)") (class "Default")
      (node (ref "D187") (pin "C") (pinfunction "K_C") (pintype "bidirectional"))
      (node (ref "R46") (pin "2") (pinfunction "2_2") (pintype "passive"))
    )
    (net (code "234") (name "Net-(D188-K)") (class "Default")
      (node (ref "D188") (pin "C") (pinfunction "K_C") (pintype "bidirectional"))
      (node (ref "D189") (pin "A") (pinfunction "A_A") (pintype "bidirectional"))
    )
    (net (code "235") (name "Net-(D188-PadA)") (class "Default")
      (node (ref "D188") (pin "A") (pinfunction "A_A") (pintype "bidirectional"))
      (node (ref "R46") (pin "1") (pinfunction "1_1") (pintype "passive"))
    )
    (net (code "236") (name "Net-(D189-K)") (class "Default")
      (node (ref "D189") (pin "C") (pinfunction "K_C") (pintype "bidirectional"))
      (node (ref "D190") (pin "A") (pinfunction "A_A") (pintype "bidirectional"))
    )
    (net (code "237") (name "Net-(D190-K)") (class "Default")
      (node (ref "D190") (pin "C") (pinfunction "K_C") (pintype "bidirectional"))
      (node (ref "D191") (pin "A") (pinfunction "A_A") (pintype "bidirectional"))
    )
    (net (code "238") (name "Net-(D191-K)") (class "Default")
      (node (ref "D191") (pin "C") (pinfunction "K_C") (pintype "bidirectional"))
      (node (ref "D192") (pin "A") (pinfunction "A_A") (pintype "bidirectional"))
    )
    (net (code "239") (name "Net-(D192-K)") (class "Default")
      (node (ref "D192") (pin "C") (pinfunction "K_C") (pintype "bidirectional"))
      (node (ref "D193") (pin "A") (pinfunction "A_A") (pintype "bidirectional"))
    )
    (net (code "240") (name "Net-(D193-K)") (class "Default")
      (node (ref "D193") (pin "C") (pinfunction "K_C") (pintype "bidirectional"))
      (node (ref "D194") (pin "A") (pinfunction "A_A") (pintype "bidirectional"))
    )
    (net (code "241") (name "Net-(D194-K)") (class "Default")
      (node (ref "D194") (pin "C") (pinfunction "K_C") (pintype "bidirectional"))
      (node (ref "D195") (pin "A") (pinfunction "A_A") (pintype "bidirectional"))
    )
    (net (code "242") (name "Net-(D196-K)") (class "Default")
      (node (ref "D196") (pin "C") (pinfunction "K_C") (pintype "bidirectional"))
      (node (ref "D197") (pin "A") (pinfunction "A_A") (pintype "bidirectional"))
    )
    (net (code "243") (name "Net-(D197-K)") (class "Default")
      (node (ref "D197") (pin "C") (pinfunction "K_C") (pintype "bidirectional"))
      (node (ref "D198") (pin "A") (pinfunction "A_A") (pintype "bidirectional"))
    )
    (net (code "244") (name "Net-(D198-K)") (class "Default")
      (node (ref "D198") (pin "C") (pinfunction "K_C") (pintype "bidirectional"))
      (node (ref "D199") (pin "A") (pinfunction "A_A") (pintype "bidirectional"))
    )
    (net (code "245") (name "Net-(D199-K)") (class "Default")
      (node (ref "D199") (pin "C") (pinfunction "K_C") (pintype "bidirectional"))
      (node (ref "D200") (pin "A") (pinfunction "A_A") (pintype "bidirectional"))
    )
    (net (code "246") (name "Net-(D200-K)") (class "Default")
      (node (ref "D200") (pin "C") (pinfunction "K_C") (pintype "bidirectional"))
      (node (ref "D201") (pin "A") (pinfunction "A_A") (pintype "bidirectional"))
    )
    (net (code "247") (name "Net-(D201-K)") (class "Default")
      (node (ref "D201") (pin "C") (pinfunction "K_C") (pintype "bidirectional"))
      (node (ref "D202") (pin "A") (pinfunction "A_A") (pintype "bidirectional"))
    )
    (net (code "248") (name "Net-(D202-K)") (class "Default")
      (node (ref "D202") (pin "C") (pinfunction "K_C") (pintype "bidirectional"))
      (node (ref "D203") (pin "A") (pinfunction "A_A") (pintype "bidirectional"))
    )
    (net (code "249") (name "Net-(D203-K)") (class "Default")
      (node (ref "D203") (pin "C") (pinfunction "K_C") (pintype "bidirectional"))
      (node (ref "R57") (pin "2") (pinfunction "2_2") (pintype "passive"))
    )
    (net (code "250") (name "Net-(D204-K)") (class "Default")
      (node (ref "D204") (pin "C") (pinfunction "K_C") (pintype "bidirectional"))
      (node (ref "D205") (pin "A") (pinfunction "A_A") (pintype "bidirectional"))
    )
    (net (code "251") (name "Net-(D204-PadA)") (class "Default")
      (node (ref "D204") (pin "A") (pinfunction "A_A") (pintype "bidirectional"))
      (node (ref "R57") (pin "1") (pinfunction "1_1") (pintype "passive"))
    )
    (net (code "252") (name "Net-(D205-K)") (class "Default")
      (node (ref "D205") (pin "C") (pinfunction "K_C") (pintype "bidirectional"))
      (node (ref "D206") (pin "A") (pinfunction "A_A") (pintype "bidirectional"))
    )
    (net (code "253") (name "Net-(D206-K)") (class "Default")
      (node (ref "D206") (pin "C") (pinfunction "K_C") (pintype "bidirectional"))
      (node (ref "D207") (pin "A") (pinfunction "A_A") (pintype "bidirectional"))
    )
    (net (code "254") (name "Net-(D207-K)") (class "Default")
      (node (ref "D207") (pin "C") (pinfunction "K_C") (pintype "bidirectional"))
      (node (ref "D208") (pin "A") (pinfunction "A_A") (pintype "bidirectional"))
    )
    (net (code "255") (name "Net-(D208-K)") (class "Default")
      (node (ref "D208") (pin "C") (pinfunction "K_C") (pintype "bidirectional"))
      (node (ref "D209") (pin "A") (pinfunction "A_A") (pintype "bidirectional"))
    )
    (net (code "256") (name "Net-(D209-K)") (class "Default")
      (node (ref "D209") (pin "C") (pinfunction "K_C") (pintype "bidirectional"))
      (node (ref "D210") (pin "A") (pinfunction "A_A") (pintype "bidirectional"))
    )
    (net (code "257") (name "Net-(D210-K)") (class "Default")
      (node (ref "D210") (pin "C") (pinfunction "K_C") (pintype "bidirectional"))
      (node (ref "D211") (pin "A") (pinfunction "A_A") (pintype "bidirectional"))
    )
    (net (code "258") (name "Net-(D213-K)") (class "Default")
      (node (ref "D213") (pin "C") (pinfunction "K_C") (pintype "bidirectional"))
      (node (ref "D214") (pin "A") (pinfunction "A_A") (pintype "bidirectional"))
    )
    (net (code "259") (name "Net-(D214-K)") (class "Default")
      (node (ref "D214") (pin "C") (pinfunction "K_C") (pintype "bidirectional"))
      (node (ref "D215") (pin "A") (pinfunction "A_A") (pintype "bidirectional"))
    )
    (net (code "260") (name "Net-(D215-K)") (class "Default")
      (node (ref "D215") (pin "C") (pinfunction "K_C") (pintype "bidirectional"))
      (node (ref "D216") (pin "A") (pinfunction "A_A") (pintype "bidirectional"))
    )
    (net (code "261") (name "Net-(D216-K)") (class "Default")
      (node (ref "D216") (pin "C") (pinfunction "K_C") (pintype "bidirectional"))
      (node (ref "D217") (pin "A") (pinfunction "A_A") (pintype "bidirectional"))
    )
    (net (code "262") (name "Net-(D217-K)") (class "Default")
      (node (ref "D217") (pin "C") (pinfunction "K_C") (pintype "bidirectional"))
      (node (ref "D218") (pin "A") (pinfunction "A_A") (pintype "bidirectional"))
    )
    (net (code "263") (name "Net-(D218-K)") (class "Default")
      (node (ref "D218") (pin "C") (pinfunction "K_C") (pintype "bidirectional"))
      (node (ref "D219") (pin "A") (pinfunction "A_A") (pintype "bidirectional"))
    )
    (net (code "264") (name "Net-(D219-K)") (class "Default")
      (node (ref "D219") (pin "C") (pinfunction "K_C") (pintype "bidirectional"))
      (node (ref "D220") (pin "A") (pinfunction "A_A") (pintype "bidirectional"))
    )
    (net (code "265") (name "Net-(D220-K)") (class "Default")
      (node (ref "D220") (pin "C") (pinfunction "K_C") (pintype "bidirectional"))
      (node (ref "R60") (pin "2") (pinfunction "2_2") (pintype "passive"))
    )
    (net (code "266") (name "Net-(D221-K)") (class "Default")
      (node (ref "D221") (pin "C") (pinfunction "K_C") (pintype "bidirectional"))
      (node (ref "D222") (pin "A") (pinfunction "A_A") (pintype "bidirectional"))
    )
    (net (code "267") (name "Net-(D221-PadA)") (class "Default")
      (node (ref "D221") (pin "A") (pinfunction "A_A") (pintype "bidirectional"))
      (node (ref "R60") (pin "1") (pinfunction "1_1") (pintype "passive"))
    )
    (net (code "268") (name "Net-(D222-K)") (class "Default")
      (node (ref "D222") (pin "C") (pinfunction "K_C") (pintype "bidirectional"))
      (node (ref "D223") (pin "A") (pinfunction "A_A") (pintype "bidirectional"))
    )
    (net (code "269") (name "Net-(D223-K)") (class "Default")
      (node (ref "D223") (pin "C") (pinfunction "K_C") (pintype "bidirectional"))
      (node (ref "D224") (pin "A") (pinfunction "A_A") (pintype "bidirectional"))
    )
    (net (code "270") (name "Net-(D224-K)") (class "Default")
      (node (ref "D224") (pin "C") (pinfunction "K_C") (pintype "bidirectional"))
      (node (ref "D225") (pin "A") (pinfunction "A_A") (pintype "bidirectional"))
    )
    (net (code "271") (name "Net-(D225-K)") (class "Default")
      (node (ref "D225") (pin "C") (pinfunction "K_C") (pintype "bidirectional"))
      (node (ref "D226") (pin "A") (pinfunction "A_A") (pintype "bidirectional"))
    )
    (net (code "272") (name "Net-(D226-K)") (class "Default")
      (node (ref "D226") (pin "C") (pinfunction "K_C") (pintype "bidirectional"))
      (node (ref "D227") (pin "A") (pinfunction "A_A") (pintype "bidirectional"))
    )
    (net (code "273") (name "Net-(D227-K)") (class "Default")
      (node (ref "D227") (pin "C") (pinfunction "K_C") (pintype "bidirectional"))
      (node (ref "D228") (pin "A") (pinfunction "A_A") (pintype "bidirectional"))
    )
    (net (code "274") (name "Net-(D229-K)") (class "Default")
      (node (ref "D229") (pin "C") (pinfunction "K_C") (pintype "bidirectional"))
      (node (ref "D230") (pin "A") (pinfunction "A_A") (pintype "bidirectional"))
    )
    (net (code "275") (name "Net-(D230-K)") (class "Default")
      (node (ref "D230") (pin "C") (pinfunction "K_C") (pintype "bidirectional"))
      (node (ref "D231") (pin "A") (pinfunction "A_A") (pintype "bidirectional"))
    )
    (net (code "276") (name "Net-(D231-K)") (class "Default")
      (node (ref "D231") (pin "C") (pinfunction "K_C") (pintype "bidirectional"))
      (node (ref "D232") (pin "A") (pinfunction "A_A") (pintype "bidirectional"))
    )
    (net (code "277") (name "Net-(D232-K)") (class "Default")
      (node (ref "D232") (pin "C") (pinfunction "K_C") (pintype "bidirectional"))
      (node (ref "D233") (pin "A") (pinfunction "A_A") (pintype "bidirectional"))
    )
    (net (code "278") (name "Net-(D233-K)") (class "Default")
      (node (ref "D233") (pin "C") (pinfunction "K_C") (pintype "bidirectional"))
      (node (ref "D234") (pin "A") (pinfunction "A_A") (pintype "bidirectional"))
    )
    (net (code "279") (name "Net-(D234-K)") (class "Default")
      (node (ref "D234") (pin "C") (pinfunction "K_C") (pintype "bidirectional"))
      (node (ref "D235") (pin "A") (pinfunction "A_A") (pintype "bidirectional"))
    )
    (net (code "280") (name "Net-(D235-K)") (class "Default")
      (node (ref "D235") (pin "C") (pinfunction "K_C") (pintype "bidirectional"))
      (node (ref "D236") (pin "A") (pinfunction "A_A") (pintype "bidirectional"))
    )
    (net (code "281") (name "Net-(D236-K)") (class "Default")
      (node (ref "D236") (pin "C") (pinfunction "K_C") (pintype "bidirectional"))
      (node (ref "R64") (pin "2") (pinfunction "2_2") (pintype "passive"))
    )
    (net (code "282") (name "Net-(D237-K)") (class "Default")
      (node (ref "D237") (pin "C") (pinfunction "K_C") (pintype "bidirectional"))
      (node (ref "D238") (pin "A") (pinfunction "A_A") (pintype "bidirectional"))
    )
    (net (code "283") (name "Net-(D237-PadA)") (class "Default")
      (node (ref "D237") (pin "A") (pinfunction "A_A") (pintype "bidirectional"))
      (node (ref "R64") (pin "1") (pinfunction "1_1") (pintype "passive"))
    )
    (net (code "284") (name "Net-(D238-K)") (class "Default")
      (node (ref "D238") (pin "C") (pinfunction "K_C") (pintype "bidirectional"))
      (node (ref "D239") (pin "A") (pinfunction "A_A") (pintype "bidirectional"))
    )
    (net (code "285") (name "Net-(D239-K)") (class "Default")
      (node (ref "D239") (pin "C") (pinfunction "K_C") (pintype "bidirectional"))
      (node (ref "D240") (pin "A") (pinfunction "A_A") (pintype "bidirectional"))
    )
    (net (code "286") (name "Net-(D240-K)") (class "Default")
      (node (ref "D240") (pin "C") (pinfunction "K_C") (pintype "bidirectional"))
      (node (ref "D241") (pin "A") (pinfunction "A_A") (pintype "bidirectional"))
    )
    (net (code "287") (name "Net-(D241-K)") (class "Default")
      (node (ref "D241") (pin "C") (pinfunction "K_C") (pintype "bidirectional"))
      (node (ref "D242") (pin "A") (pinfunction "A_A") (pintype "bidirectional"))
    )
    (net (code "288") (name "Net-(D242-K)") (class "Default")
      (node (ref "D242") (pin "C") (pinfunction "K_C") (pintype "bidirectional"))
      (node (ref "D243") (pin "A") (pinfunction "A_A") (pintype "bidirectional"))
    )
    (net (code "289") (name "Net-(D243-K)") (class "Default")
      (node (ref "D243") (pin "C") (pinfunction "K_C") (pintype "bidirectional"))
      (node (ref "D244") (pin "A") (pinfunction "A_A") (pintype "bidirectional"))
    )
    (net (code "290") (name "Net-(D245-K)") (class "Default")
      (node (ref "D245") (pin "C") (pinfunction "K_C") (pintype "bidirectional"))
      (node (ref "D246") (pin "A") (pinfunction "A_A") (pintype "bidirectional"))
    )
    (net (code "291") (name "Net-(D246-K)") (class "Default")
      (node (ref "D246") (pin "C") (pinfunction "K_C") (pintype "bidirectional"))
      (node (ref "D247") (pin "A") (pinfunction "A_A") (pintype "bidirectional"))
    )
    (net (code "292") (name "Net-(D247-K)") (class "Default")
      (node (ref "D247") (pin "C") (pinfunction "K_C") (pintype "bidirectional"))
      (node (ref "D248") (pin "A") (pinfunction "A_A") (pintype "bidirectional"))
    )
    (net (code "293") (name "Net-(D248-K)") (class "Default")
      (node (ref "D248") (pin "C") (pinfunction "K_C") (pintype "bidirectional"))
      (node (ref "D249") (pin "A") (pinfunction "A_A") (pintype "bidirectional"))
    )
    (net (code "294") (name "Net-(D249-K)") (class "Default")
      (node (ref "D249") (pin "C") (pinfunction "K_C") (pintype "bidirectional"))
      (node (ref "D250") (pin "A") (pinfunction "A_A") (pintype "bidirectional"))
    )
    (net (code "295") (name "Net-(D250-K)") (class "Default")
      (node (ref "D250") (pin "C") (pinfunction "K_C") (pintype "bidirectional"))
      (node (ref "D251") (pin "A") (pinfunction "A_A") (pintype "bidirectional"))
    )
    (net (code "296") (name "Net-(D251-K)") (class "Default")
      (node (ref "D251") (pin "C") (pinfunction "K_C") (pintype "bidirectional"))
      (node (ref "D252") (pin "A") (pinfunction "A_A") (pintype "bidirectional"))
    )
    (net (code "297") (name "Net-(D252-K)") (class "Default")
      (node (ref "D252") (pin "C") (pinfunction "K_C") (pintype "bidirectional"))
      (node (ref "R67") (pin "2") (pinfunction "2_2") (pintype "passive"))
    )
    (net (code "298") (name "Net-(D253-K)") (class "Default")
      (node (ref "D253") (pin "C") (pinfunction "K_C") (pintype "bidirectional"))
      (node (ref "D254") (pin "A") (pinfunction "A_A") (pintype "bidirectional"))
    )
    (net (code "299") (name "Net-(D253-PadA)") (class "Default")
      (node (ref "D253") (pin "A") (pinfunction "A_A") (pintype "bidirectional"))
      (node (ref "R67") (pin "1") (pinfunction "1_1") (pintype "passive"))
    )
    (net (code "300") (name "Net-(D254-K)") (class "Default")
      (node (ref "D254") (pin "C") (pinfunction "K_C") (pintype "bidirectional"))
      (node (ref "D255") (pin "A") (pinfunction "A_A") (pintype "bidirectional"))
    )
    (net (code "301") (name "Net-(D255-K)") (class "Default")
      (node (ref "D255") (pin "C") (pinfunction "K_C") (pintype "bidirectional"))
      (node (ref "D256") (pin "A") (pinfunction "A_A") (pintype "bidirectional"))
    )
    (net (code "302") (name "Net-(D256-K)") (class "Default")
      (node (ref "D256") (pin "C") (pinfunction "K_C") (pintype "bidirectional"))
      (node (ref "D257") (pin "A") (pinfunction "A_A") (pintype "bidirectional"))
    )
    (net (code "303") (name "Net-(D257-K)") (class "Default")
      (node (ref "D257") (pin "C") (pinfunction "K_C") (pintype "bidirectional"))
      (node (ref "D258") (pin "A") (pinfunction "A_A") (pintype "bidirectional"))
    )
    (net (code "304") (name "Net-(D258-K)") (class "Default")
      (node (ref "D258") (pin "C") (pinfunction "K_C") (pintype "bidirectional"))
      (node (ref "D259") (pin "A") (pinfunction "A_A") (pintype "bidirectional"))
    )
    (net (code "305") (name "Net-(D259-K)") (class "Default")
      (node (ref "D259") (pin "C") (pinfunction "K_C") (pintype "bidirectional"))
      (node (ref "D260") (pin "A") (pinfunction "A_A") (pintype "bidirectional"))
    )
    (net (code "306") (name "Net-(JMP1-Pad2)") (class "Default")
      (node (ref "JMP1") (pin "2") (pinfunction "2_2") (pintype "bidirectional"))
      (node (ref "Q2") (pin "7") (pinfunction "C1_7") (pintype "bidirectional"))
      (node (ref "Q2") (pin "78") (pinfunction "C1_78") (pintype "bidirectional"))
      (node (ref "Q2") (pin "8") (pinfunction "C1_8") (pintype "bidirectional"))
    )
    (net (code "307") (name "Net-(JMP2-Pad2)") (class "Default")
      (node (ref "JMP2") (pin "2") (pinfunction "2_2") (pintype "bidirectional"))
      (node (ref "Q3") (pin "7") (pinfunction "C1_7") (pintype "bidirectional"))
      (node (ref "Q3") (pin "78") (pinfunction "C1_78") (pintype "bidirectional"))
      (node (ref "Q3") (pin "8") (pinfunction "C1_8") (pintype "bidirectional"))
    )
    (net (code "308") (name "Net-(JMP4-Pad2)") (class "Default")
      (node (ref "JMP4") (pin "2") (pinfunction "2_2") (pintype "bidirectional"))
      (node (ref "Q5") (pin "7") (pinfunction "C1_7") (pintype "bidirectional"))
      (node (ref "Q5") (pin "78") (pinfunction "C1_78") (pintype "bidirectional"))
      (node (ref "Q5") (pin "8") (pinfunction "C1_8") (pintype "bidirectional"))
    )
    (net (code "309") (name "Net-(JMP5-Pad1)") (class "Default")
      (node (ref "JMP5") (pin "1") (pinfunction "1_1") (pintype "bidirectional"))
      (node (ref "JMP7") (pin "2") (pinfunction "2_2") (pintype "bidirectional"))
    )
    (net (code "310") (name "Net-(JMP6-Pad2)") (class "Default")
      (node (ref "JMP6") (pin "2") (pinfunction "2_2") (pintype "bidirectional"))
      (node (ref "Q6") (pin "7") (pinfunction "C1_7") (pintype "bidirectional"))
      (node (ref "Q6") (pin "78") (pinfunction "C1_78") (pintype "bidirectional"))
      (node (ref "Q6") (pin "8") (pinfunction "C1_8") (pintype "bidirectional"))
    )
    (net (code "311") (name "Net-(JMP9-Pad1)") (class "Default")
      (node (ref "JMP9") (pin "1") (pinfunction "1_1") (pintype "bidirectional"))
      (node (ref "RGB33") (pin "GC") (pinfunction "GC_GC") (pintype "bidirectional"))
    )
    (net (code "312") (name "Net-(JMP9-Pad2)") (class "Default")
      (node (ref "JMP9") (pin "2") (pinfunction "2_2") (pintype "bidirectional"))
      (node (ref "Q8") (pin "7") (pinfunction "C1_7") (pintype "bidirectional"))
      (node (ref "Q8") (pin "78") (pinfunction "C1_78") (pintype "bidirectional"))
      (node (ref "Q8") (pin "8") (pinfunction "C1_8") (pintype "bidirectional"))
    )
    (net (code "313") (name "Net-(JMP10-Pad2)") (class "Default")
      (node (ref "JMP10") (pin "2") (pinfunction "2_2") (pintype "bidirectional"))
      (node (ref "Q9") (pin "7") (pinfunction "C1_7") (pintype "bidirectional"))
      (node (ref "Q9") (pin "78") (pinfunction "C1_78") (pintype "bidirectional"))
      (node (ref "Q9") (pin "8") (pinfunction "C1_8") (pintype "bidirectional"))
    )
    (net (code "314") (name "Net-(JMP12-Pad1)") (class "Default")
      (node (ref "JMP12") (pin "1") (pinfunction "1_1") (pintype "bidirectional"))
      (node (ref "RGB49") (pin "GC") (pinfunction "GC_GC") (pintype "bidirectional"))
    )
    (net (code "315") (name "Net-(JMP12-Pad2)") (class "Default")
      (node (ref "JMP12") (pin "2") (pinfunction "2_2") (pintype "bidirectional"))
      (node (ref "Q11") (pin "7") (pinfunction "C1_7") (pintype "bidirectional"))
      (node (ref "Q11") (pin "78") (pinfunction "C1_78") (pintype "bidirectional"))
      (node (ref "Q11") (pin "8") (pinfunction "C1_8") (pintype "bidirectional"))
    )
    (net (code "316") (name "Net-(JMP13-Pad1)") (class "Default")
      (node (ref "JMP13") (pin "1") (pinfunction "1_1") (pintype "bidirectional"))
      (node (ref "RGB49") (pin "RC") (pinfunction "RC_RC") (pintype "bidirectional"))
    )
    (net (code "317") (name "Net-(JMP13-Pad2)") (class "Default")
      (node (ref "JMP13") (pin "2") (pinfunction "2_2") (pintype "bidirectional"))
      (node (ref "Q12") (pin "7") (pinfunction "C1_7") (pintype "bidirectional"))
      (node (ref "Q12") (pin "78") (pinfunction "C1_78") (pintype "bidirectional"))
      (node (ref "Q12") (pin "8") (pinfunction "C1_8") (pintype "bidirectional"))
    )
    (net (code "318") (name "Net-(Q1-B1)") (class "Default")
      (node (ref "Q1") (pin "2") (pinfunction "B1_2") (pintype "bidirectional"))
      (node (ref "R2") (pin "2") (pinfunction "2_2") (pintype "passive"))
    )
    (net (code "319") (name "Net-(Q1-E1)") (class "Default")
      (node (ref "Q1") (pin "1") (pinfunction "E1_1") (pintype "bidirectional"))
      (node (ref "R3") (pin "2") (pinfunction "2_2") (pintype "passive"))
    )
    (net (code "320") (name "Net-(Q2-B1)") (class "Default")
      (node (ref "Q2") (pin "2") (pinfunction "B1_2") (pintype "bidirectional"))
      (node (ref "R6") (pin "2") (pinfunction "2_2") (pintype "passive"))
    )
    (net (code "321") (name "Net-(Q2-E1)") (class "Default")
      (node (ref "Q2") (pin "1") (pinfunction "E1_1") (pintype "bidirectional"))
      (node (ref "R7") (pin "2") (pinfunction "2_2") (pintype "passive"))
    )
    (net (code "322") (name "Net-(Q3-B2)") (class "Default")
      (node (ref "Q3") (pin "4") (pinfunction "B2_4") (pintype "bidirectional"))
      (node (ref "R8") (pin "1") (pinfunction "1_1") (pintype "passive"))
    )
    (net (code "323") (name "Net-(Q3-E2)") (class "Default")
      (node (ref "Q3") (pin "3") (pinfunction "E2_3") (pintype "bidirectional"))
      (node (ref "R13") (pin "2") (pinfunction "2_2") (pintype "passive"))
    )
    (net (code "324") (name "Net-(Q4-B2)") (class "Default")
      (node (ref "Q4") (pin "4") (pinfunction "B2_4") (pintype "bidirectional"))
      (node (ref "R28") (pin "1") (pinfunction "1_1") (pintype "passive"))
    )
    (net (code "325") (name "Net-(Q4-E2)") (class "Default")
      (node (ref "Q4") (pin "3") (pinfunction "E2_3") (pintype "bidirectional"))
      (node (ref "R24") (pin "2") (pinfunction "2_2") (pintype "passive"))
    )
    (net (code "326") (name "Net-(Q5-B2)") (class "Default")
      (node (ref "Q5") (pin "4") (pinfunction "B2_4") (pintype "bidirectional"))
      (node (ref "R31") (pin "1") (pinfunction "1_1") (pintype "passive"))
    )
    (net (code "327") (name "Net-(Q5-E2)") (class "Default")
      (node (ref "Q5") (pin "3") (pinfunction "E2_3") (pintype "bidirectional"))
      (node (ref "R27") (pin "2") (pinfunction "2_2") (pintype "passive"))
    )
    (net (code "328") (name "Net-(Q6-B2)") (class "Default")
      (node (ref "Q6") (pin "4") (pinfunction "B2_4") (pintype "bidirectional"))
      (node (ref "R33") (pin "1") (pinfunction "1_1") (pintype "passive"))
    )
    (net (code "329") (name "Net-(Q6-E2)") (class "Default")
      (node (ref "Q6") (pin "3") (pinfunction "E2_3") (pintype "bidirectional"))
      (node (ref "R32") (pin "2") (pinfunction "2_2") (pintype "passive"))
    )
    (net (code "330") (name "Net-(Q7-B1)") (class "Default")
      (node (ref "Q7") (pin "2") (pinfunction "B1_2") (pintype "bidirectional"))
      (node (ref "R36") (pin "2") (pinfunction "2_2") (pintype "passive"))
    )
    (net (code "331") (name "Net-(Q7-C1-Pad7)") (class "Default")
      (node (ref "Q7") (pin "7") (pinfunction "C1_7") (pintype "bidirectional"))
      (node (ref "Q7") (pin "78") (pinfunction "C1_78") (pintype "bidirectional"))
      (node (ref "Q7") (pin "8") (pinfunction "C1_8") (pintype "bidirectional"))
      (node (ref "RGB33") (pin "BC") (pinfunction "BC_BC") (pintype "bidirectional"))
    )
    (net (code "332") (name "Net-(Q7-C2-Pad5)") (class "Default")
      (node (ref "Q7") (pin "5") (pinfunction "C2_5") (pintype "bidirectional"))
      (node (ref "Q7") (pin "56") (pinfunction "C2_56") (pintype "bidirectional"))
      (node (ref "Q7") (pin "6") (pinfunction "C2_6") (pintype "bidirectional"))
      (node (ref "RGB41") (pin "BC") (pinfunction "BC_BC") (pintype "bidirectional"))
    )
    (net (code "333") (name "Net-(Q7-E1)") (class "Default")
      (node (ref "Q7") (pin "1") (pinfunction "E1_1") (pintype "bidirectional"))
      (node (ref "R37") (pin "2") (pinfunction "2_2") (pintype "passive"))
    )
    (net (code "334") (name "Net-(Q8-B1)") (class "Default")
      (node (ref "Q8") (pin "2") (pinfunction "B1_2") (pintype "bidirectional"))
      (node (ref "R40") (pin "2") (pinfunction "2_2") (pintype "passive"))
    )
    (net (code "335") (name "Net-(Q8-C2-Pad5)") (class "Default")
      (node (ref "Q8") (pin "5") (pinfunction "C2_5") (pintype "bidirectional"))
      (node (ref "Q8") (pin "56") (pinfunction "C2_56") (pintype "bidirectional"))
      (node (ref "Q8") (pin "6") (pinfunction "C2_6") (pintype "bidirectional"))
      (node (ref "RGB41") (pin "GC") (pinfunction "GC_GC") (pintype "bidirectional"))
    )
    (net (code "336") (name "Net-(Q8-E1)") (class "Default")
      (node (ref "Q8") (pin "1") (pinfunction "E1_1") (pintype "bidirectional"))
      (node (ref "R41") (pin "2") (pinfunction "2_2") (pintype "passive"))
    )
    (net (code "337") (name "Net-(Q9-B2)") (class "Default")
      (node (ref "Q9") (pin "4") (pinfunction "B2_4") (pintype "bidirectional"))
      (node (ref "R42") (pin "1") (pinfunction "1_1") (pintype "passive"))
    )
    (net (code "338") (name "Net-(Q9-C2-Pad5)") (class "Default")
      (node (ref "Q9") (pin "5") (pinfunction "C2_5") (pintype "bidirectional"))
      (node (ref "Q9") (pin "56") (pinfunction "C2_56") (pintype "bidirectional"))
      (node (ref "Q9") (pin "6") (pinfunction "C2_6") (pintype "bidirectional"))
      (node (ref "RGB41") (pin "RC") (pinfunction "RC_RC") (pintype "bidirectional"))
    )
    (net (code "339") (name "Net-(Q9-E2)") (class "Default")
      (node (ref "Q9") (pin "3") (pinfunction "E2_3") (pintype "bidirectional"))
      (node (ref "R47") (pin "2") (pinfunction "2_2") (pintype "passive"))
    )
    (net (code "340") (name "Net-(Q10-B2)") (class "Default")
      (node (ref "Q10") (pin "4") (pinfunction "B2_4") (pintype "bidirectional"))
      (node (ref "R62") (pin "1") (pinfunction "1_1") (pintype "passive"))
    )
    (net (code "341") (name "Net-(Q10-C1-Pad7)") (class "Default")
      (node (ref "Q10") (pin "7") (pinfunction "C1_7") (pintype "bidirectional"))
      (node (ref "Q10") (pin "78") (pinfunction "C1_78") (pintype "bidirectional"))
      (node (ref "Q10") (pin "8") (pinfunction "C1_8") (pintype "bidirectional"))
      (node (ref "RGB49") (pin "BC") (pinfunction "BC_BC") (pintype "bidirectional"))
    )
    (net (code "342") (name "Net-(Q10-C2-Pad5)") (class "Default")
      (node (ref "Q10") (pin "5") (pinfunction "C2_5") (pintype "bidirectional"))
      (node (ref "Q10") (pin "56") (pinfunction "C2_56") (pintype "bidirectional"))
      (node (ref "Q10") (pin "6") (pinfunction "C2_6") (pintype "bidirectional"))
      (node (ref "RGB57") (pin "BC") (pinfunction "BC_BC") (pintype "bidirectional"))
    )
    (net (code "343") (name "Net-(Q10-E2)") (class "Default")
      (node (ref "Q10") (pin "3") (pinfunction "E2_3") (pintype "bidirectional"))
      (node (ref "R58") (pin "2") (pinfunction "2_2") (pintype "passive"))
    )
    (net (code "344") (name "Net-(Q11-B2)") (class "Default")
      (node (ref "Q11") (pin "4") (pinfunction "B2_4") (pintype "bidirectional"))
      (node (ref "R65") (pin "1") (pinfunction "1_1") (pintype "passive"))
    )
    (net (code "345") (name "Net-(Q11-C2-Pad5)") (class "Default")
      (node (ref "Q11") (pin "5") (pinfunction "C2_5") (pintype "bidirectional"))
      (node (ref "Q11") (pin "56") (pinfunction "C2_56") (pintype "bidirectional"))
      (node (ref "Q11") (pin "6") (pinfunction "C2_6") (pintype "bidirectional"))
      (node (ref "RGB57") (pin "GC") (pinfunction "GC_GC") (pintype "bidirectional"))
    )
    (net (code "346") (name "Net-(Q11-E2)") (class "Default")
      (node (ref "Q11") (pin "3") (pinfunction "E2_3") (pintype "bidirectional"))
      (node (ref "R61") (pin "2") (pinfunction "2_2") (pintype "passive"))
    )
    (net (code "347") (name "Net-(Q12-B2)") (class "Default")
      (node (ref "Q12") (pin "4") (pinfunction "B2_4") (pintype "bidirectional"))
      (node (ref "R68") (pin "1") (pinfunction "1_1") (pintype "passive"))
    )
    (net (code "348") (name "Net-(Q12-C2-Pad5)") (class "Default")
      (node (ref "Q12") (pin "5") (pinfunction "C2_5") (pintype "bidirectional"))
      (node (ref "Q12") (pin "56") (pinfunction "C2_56") (pintype "bidirectional"))
      (node (ref "Q12") (pin "6") (pinfunction "C2_6") (pintype "bidirectional"))
      (node (ref "RGB57") (pin "RC") (pinfunction "RC_RC") (pintype "bidirectional"))
    )
    (net (code "349") (name "Net-(Q12-E2)") (class "Default")
      (node (ref "Q12") (pin "3") (pinfunction "E2_3") (pintype "bidirectional"))
      (node (ref "R66") (pin "2") (pinfunction "2_2") (pintype "passive"))
    )
    (net (code "350") (name "Net-(RGB1-PadBA)") (class "Default")
      (node (ref "RGB1") (pin "BA") (pinfunction "BA_BA") (pintype "bidirectional"))
      (node (ref "RGB2") (pin "BC") (pinfunction "BC_BC") (pintype "bidirectional"))
    )
    (net (code "351") (name "Net-(RGB1-PadGA)") (class "Default")
      (node (ref "RGB1") (pin "GA") (pinfunction "GA_GA") (pintype "bidirectional"))
      (node (ref "RGB2") (pin "GC") (pinfunction "GC_GC") (pintype "bidirectional"))
    )
    (net (code "352") (name "Net-(RGB1-PadRA)") (class "Default")
      (node (ref "RGB1") (pin "RA") (pinfunction "RA_RA") (pintype "bidirectional"))
      (node (ref "RGB2") (pin "RC") (pinfunction "RC_RC") (pintype "bidirectional"))
    )
    (net (code "353") (name "Net-(RGB2-PadBA)") (class "Default")
      (node (ref "RGB2") (pin "BA") (pinfunction "BA_BA") (pintype "bidirectional"))
      (node (ref "RGB3") (pin "BC") (pinfunction "BC_BC") (pintype "bidirectional"))
    )
    (net (code "354") (name "Net-(RGB2-PadGA)") (class "Default")
      (node (ref "RGB2") (pin "GA") (pinfunction "GA_GA") (pintype "bidirectional"))
      (node (ref "RGB3") (pin "GC") (pinfunction "GC_GC") (pintype "bidirectional"))
    )
    (net (code "355") (name "Net-(RGB2-PadRA)") (class "Default")
      (node (ref "RGB2") (pin "RA") (pinfunction "RA_RA") (pintype "bidirectional"))
      (node (ref "RGB3") (pin "RC") (pinfunction "RC_RC") (pintype "bidirectional"))
    )
    (net (code "356") (name "Net-(RGB3-PadBA)") (class "Default")
      (node (ref "RGB3") (pin "BA") (pinfunction "BA_BA") (pintype "bidirectional"))
      (node (ref "RGB4") (pin "BC") (pinfunction "BC_BC") (pintype "bidirectional"))
    )
    (net (code "357") (name "Net-(RGB3-PadGA)") (class "Default")
      (node (ref "RGB3") (pin "GA") (pinfunction "GA_GA") (pintype "bidirectional"))
      (node (ref "RGB4") (pin "GC") (pinfunction "GC_GC") (pintype "bidirectional"))
    )
    (net (code "358") (name "Net-(RGB3-PadRA)") (class "Default")
      (node (ref "RGB3") (pin "RA") (pinfunction "RA_RA") (pintype "bidirectional"))
      (node (ref "RGB4") (pin "RC") (pinfunction "RC_RC") (pintype "bidirectional"))
    )
    (net (code "359") (name "Net-(RGB4-PadBA)") (class "Default")
      (node (ref "RGB4") (pin "BA") (pinfunction "BA_BA") (pintype "bidirectional"))
      (node (ref "RGB5") (pin "BC") (pinfunction "BC_BC") (pintype "bidirectional"))
    )
    (net (code "360") (name "Net-(RGB4-PadGA)") (class "Default")
      (node (ref "RGB4") (pin "GA") (pinfunction "GA_GA") (pintype "bidirectional"))
      (node (ref "RGB5") (pin "GC") (pinfunction "GC_GC") (pintype "bidirectional"))
    )
    (net (code "361") (name "Net-(RGB4-PadRA)") (class "Default")
      (node (ref "RGB4") (pin "RA") (pinfunction "RA_RA") (pintype "bidirectional"))
      (node (ref "RGB5") (pin "RC") (pinfunction "RC_RC") (pintype "bidirectional"))
    )
    (net (code "362") (name "Net-(RGB5-PadBA)") (class "Default")
      (node (ref "RGB5") (pin "BA") (pinfunction "BA_BA") (pintype "bidirectional"))
      (node (ref "RGB6") (pin "BC") (pinfunction "BC_BC") (pintype "bidirectional"))
    )
    (net (code "363") (name "Net-(RGB5-PadGA)") (class "Default")
      (node (ref "RGB5") (pin "GA") (pinfunction "GA_GA") (pintype "bidirectional"))
      (node (ref "RGB6") (pin "GC") (pinfunction "GC_GC") (pintype "bidirectional"))
    )
    (net (code "364") (name "Net-(RGB5-PadRA)") (class "Default")
      (node (ref "RGB5") (pin "RA") (pinfunction "RA_RA") (pintype "bidirectional"))
      (node (ref "RGB6") (pin "RC") (pinfunction "RC_RC") (pintype "bidirectional"))
    )
    (net (code "365") (name "Net-(RGB6-PadBA)") (class "Default")
      (node (ref "RGB6") (pin "BA") (pinfunction "BA_BA") (pintype "bidirectional"))
      (node (ref "RGB7") (pin "BC") (pinfunction "BC_BC") (pintype "bidirectional"))
    )
    (net (code "366") (name "Net-(RGB6-PadGA)") (class "Default")
      (node (ref "RGB6") (pin "GA") (pinfunction "GA_GA") (pintype "bidirectional"))
      (node (ref "RGB7") (pin "GC") (pinfunction "GC_GC") (pintype "bidirectional"))
    )
    (net (code "367") (name "Net-(RGB6-PadRA)") (class "Default")
      (node (ref "RGB6") (pin "RA") (pinfunction "RA_RA") (pintype "bidirectional"))
      (node (ref "RGB7") (pin "RC") (pinfunction "RC_RC") (pintype "bidirectional"))
    )
    (net (code "368") (name "Net-(RGB7-PadBA)") (class "Default")
      (node (ref "RGB7") (pin "BA") (pinfunction "BA_BA") (pintype "bidirectional"))
      (node (ref "RGB8") (pin "BC") (pinfunction "BC_BC") (pintype "bidirectional"))
    )
    (net (code "369") (name "Net-(RGB7-PadGA)") (class "Default")
      (node (ref "RGB7") (pin "GA") (pinfunction "GA_GA") (pintype "bidirectional"))
      (node (ref "RGB8") (pin "GC") (pinfunction "GC_GC") (pintype "bidirectional"))
    )
    (net (code "370") (name "Net-(RGB7-PadRA)") (class "Default")
      (node (ref "RGB7") (pin "RA") (pinfunction "RA_RA") (pintype "bidirectional"))
      (node (ref "RGB8") (pin "RC") (pinfunction "RC_RC") (pintype "bidirectional"))
    )
    (net (code "371") (name "Net-(RGB10-PadBA)") (class "Default")
      (node (ref "RGB10") (pin "BA") (pinfunction "BA_BA") (pintype "bidirectional"))
      (node (ref "RGB11") (pin "BC") (pinfunction "BC_BC") (pintype "bidirectional"))
    )
    (net (code "372") (name "Net-(RGB10-PadBC)") (class "Default")
      (node (ref "RGB10") (pin "BC") (pinfunction "BC_BC") (pintype "bidirectional"))
      (node (ref "RGB9") (pin "BA") (pinfunction "BA_BA") (pintype "bidirectional"))
    )
    (net (code "373") (name "Net-(RGB10-PadGA)") (class "Default")
      (node (ref "RGB10") (pin "GA") (pinfunction "GA_GA") (pintype "bidirectional"))
      (node (ref "RGB11") (pin "GC") (pinfunction "GC_GC") (pintype "bidirectional"))
    )
    (net (code "374") (name "Net-(RGB10-PadGC)") (class "Default")
      (node (ref "RGB10") (pin "GC") (pinfunction "GC_GC") (pintype "bidirectional"))
      (node (ref "RGB9") (pin "GA") (pinfunction "GA_GA") (pintype "bidirectional"))
    )
    (net (code "375") (name "Net-(RGB10-PadRA)") (class "Default")
      (node (ref "RGB10") (pin "RA") (pinfunction "RA_RA") (pintype "bidirectional"))
      (node (ref "RGB11") (pin "RC") (pinfunction "RC_RC") (pintype "bidirectional"))
    )
    (net (code "376") (name "Net-(RGB10-PadRC)") (class "Default")
      (node (ref "RGB10") (pin "RC") (pinfunction "RC_RC") (pintype "bidirectional"))
      (node (ref "RGB9") (pin "RA") (pinfunction "RA_RA") (pintype "bidirectional"))
    )
    (net (code "377") (name "Net-(RGB11-PadBA)") (class "Default")
      (node (ref "RGB11") (pin "BA") (pinfunction "BA_BA") (pintype "bidirectional"))
      (node (ref "RGB12") (pin "BC") (pinfunction "BC_BC") (pintype "bidirectional"))
    )
    (net (code "378") (name "Net-(RGB11-PadGA)") (class "Default")
      (node (ref "RGB11") (pin "GA") (pinfunction "GA_GA") (pintype "bidirectional"))
      (node (ref "RGB12") (pin "GC") (pinfunction "GC_GC") (pintype "bidirectional"))
    )
    (net (code "379") (name "Net-(RGB11-PadRA)") (class "Default")
      (node (ref "RGB11") (pin "RA") (pinfunction "RA_RA") (pintype "bidirectional"))
      (node (ref "RGB12") (pin "RC") (pinfunction "RC_RC") (pintype "bidirectional"))
    )
    (net (code "380") (name "Net-(RGB12-PadBA)") (class "Default")
      (node (ref "RGB12") (pin "BA") (pinfunction "BA_BA") (pintype "bidirectional"))
      (node (ref "RGB13") (pin "BC") (pinfunction "BC_BC") (pintype "bidirectional"))
    )
    (net (code "381") (name "Net-(RGB12-PadGA)") (class "Default")
      (node (ref "RGB12") (pin "GA") (pinfunction "GA_GA") (pintype "bidirectional"))
      (node (ref "RGB13") (pin "GC") (pinfunction "GC_GC") (pintype "bidirectional"))
    )
    (net (code "382") (name "Net-(RGB12-PadRA)") (class "Default")
      (node (ref "RGB12") (pin "RA") (pinfunction "RA_RA") (pintype "bidirectional"))
      (node (ref "RGB13") (pin "RC") (pinfunction "RC_RC") (pintype "bidirectional"))
    )
    (net (code "383") (name "Net-(RGB13-PadBA)") (class "Default")
      (node (ref "RGB13") (pin "BA") (pinfunction "BA_BA") (pintype "bidirectional"))
      (node (ref "RGB14") (pin "BC") (pinfunction "BC_BC") (pintype "bidirectional"))
    )
    (net (code "384") (name "Net-(RGB13-PadGA)") (class "Default")
      (node (ref "RGB13") (pin "GA") (pinfunction "GA_GA") (pintype "bidirectional"))
      (node (ref "RGB14") (pin "GC") (pinfunction "GC_GC") (pintype "bidirectional"))
    )
    (net (code "385") (name "Net-(RGB13-PadRA)") (class "Default")
      (node (ref "RGB13") (pin "RA") (pinfunction "RA_RA") (pintype "bidirectional"))
      (node (ref "RGB14") (pin "RC") (pinfunction "RC_RC") (pintype "bidirectional"))
    )
    (net (code "386") (name "Net-(RGB14-PadBA)") (class "Default")
      (node (ref "RGB14") (pin "BA") (pinfunction "BA_BA") (pintype "bidirectional"))
      (node (ref "RGB15") (pin "BC") (pinfunction "BC_BC") (pintype "bidirectional"))
    )
    (net (code "387") (name "Net-(RGB14-PadGA)") (class "Default")
      (node (ref "RGB14") (pin "GA") (pinfunction "GA_GA") (pintype "bidirectional"))
      (node (ref "RGB15") (pin "GC") (pinfunction "GC_GC") (pintype "bidirectional"))
    )
    (net (code "388") (name "Net-(RGB14-PadRA)") (class "Default")
      (node (ref "RGB14") (pin "RA") (pinfunction "RA_RA") (pintype "bidirectional"))
      (node (ref "RGB15") (pin "RC") (pinfunction "RC_RC") (pintype "bidirectional"))
    )
    (net (code "389") (name "Net-(RGB15-PadBA)") (class "Default")
      (node (ref "RGB15") (pin "BA") (pinfunction "BA_BA") (pintype "bidirectional"))
      (node (ref "RGB16") (pin "BC") (pinfunction "BC_BC") (pintype "bidirectional"))
    )
    (net (code "390") (name "Net-(RGB15-PadGA)") (class "Default")
      (node (ref "RGB15") (pin "GA") (pinfunction "GA_GA") (pintype "bidirectional"))
      (node (ref "RGB16") (pin "GC") (pinfunction "GC_GC") (pintype "bidirectional"))
    )
    (net (code "391") (name "Net-(RGB15-PadRA)") (class "Default")
      (node (ref "RGB15") (pin "RA") (pinfunction "RA_RA") (pintype "bidirectional"))
      (node (ref "RGB16") (pin "RC") (pinfunction "RC_RC") (pintype "bidirectional"))
    )
    (net (code "392") (name "Net-(RGB17-PadBA)") (class "Default")
      (node (ref "RGB17") (pin "BA") (pinfunction "BA_BA") (pintype "bidirectional"))
      (node (ref "RGB18") (pin "BC") (pinfunction "BC_BC") (pintype "bidirectional"))
    )
    (net (code "393") (name "Net-(RGB17-PadGA)") (class "Default")
      (node (ref "RGB17") (pin "GA") (pinfunction "GA_GA") (pintype "bidirectional"))
      (node (ref "RGB18") (pin "GC") (pinfunction "GC_GC") (pintype "bidirectional"))
    )
    (net (code "394") (name "Net-(RGB17-PadRA)") (class "Default")
      (node (ref "RGB17") (pin "RA") (pinfunction "RA_RA") (pintype "bidirectional"))
      (node (ref "RGB18") (pin "RC") (pinfunction "RC_RC") (pintype "bidirectional"))
    )
    (net (code "395") (name "Net-(RGB18-PadBA)") (class "Default")
      (node (ref "RGB18") (pin "BA") (pinfunction "BA_BA") (pintype "bidirectional"))
      (node (ref "RGB19") (pin "BC") (pinfunction "BC_BC") (pintype "bidirectional"))
    )
    (net (code "396") (name "Net-(RGB18-PadGA)") (class "Default")
      (node (ref "RGB18") (pin "GA") (pinfunction "GA_GA") (pintype "bidirectional"))
      (node (ref "RGB19") (pin "GC") (pinfunction "GC_GC") (pintype "bidirectional"))
    )
    (net (code "397") (name "Net-(RGB18-PadRA)") (class "Default")
      (node (ref "RGB18") (pin "RA") (pinfunction "RA_RA") (pintype "bidirectional"))
      (node (ref "RGB19") (pin "RC") (pinfunction "RC_RC") (pintype "bidirectional"))
    )
    (net (code "398") (name "Net-(RGB19-PadBA)") (class "Default")
      (node (ref "RGB19") (pin "BA") (pinfunction "BA_BA") (pintype "bidirectional"))
      (node (ref "RGB20") (pin "BC") (pinfunction "BC_BC") (pintype "bidirectional"))
    )
    (net (code "399") (name "Net-(RGB19-PadGA)") (class "Default")
      (node (ref "RGB19") (pin "GA") (pinfunction "GA_GA") (pintype "bidirectional"))
      (node (ref "RGB20") (pin "GC") (pinfunction "GC_GC") (pintype "bidirectional"))
    )
    (net (code "400") (name "Net-(RGB19-PadRA)") (class "Default")
      (node (ref "RGB19") (pin "RA") (pinfunction "RA_RA") (pintype "bidirectional"))
      (node (ref "RGB20") (pin "RC") (pinfunction "RC_RC") (pintype "bidirectional"))
    )
    (net (code "401") (name "Net-(RGB20-PadBA)") (class "Default")
      (node (ref "RGB20") (pin "BA") (pinfunction "BA_BA") (pintype "bidirectional"))
      (node (ref "RGB21") (pin "BC") (pinfunction "BC_BC") (pintype "bidirectional"))
    )
    (net (code "402") (name "Net-(RGB20-PadGA)") (class "Default")
      (node (ref "RGB20") (pin "GA") (pinfunction "GA_GA") (pintype "bidirectional"))
      (node (ref "RGB21") (pin "GC") (pinfunction "GC_GC") (pintype "bidirectional"))
    )
    (net (code "403") (name "Net-(RGB20-PadRA)") (class "Default")
      (node (ref "RGB20") (pin "RA") (pinfunction "RA_RA") (pintype "bidirectional"))
      (node (ref "RGB21") (pin "RC") (pinfunction "RC_RC") (pintype "bidirectional"))
    )
    (net (code "404") (name "Net-(RGB21-PadBA)") (class "Default")
      (node (ref "RGB21") (pin "BA") (pinfunction "BA_BA") (pintype "bidirectional"))
      (node (ref "RGB22") (pin "BC") (pinfunction "BC_BC") (pintype "bidirectional"))
    )
    (net (code "405") (name "Net-(RGB21-PadGA)") (class "Default")
      (node (ref "RGB21") (pin "GA") (pinfunction "GA_GA") (pintype "bidirectional"))
      (node (ref "RGB22") (pin "GC") (pinfunction "GC_GC") (pintype "bidirectional"))
    )
    (net (code "406") (name "Net-(RGB21-PadRA)") (class "Default")
      (node (ref "RGB21") (pin "RA") (pinfunction "RA_RA") (pintype "bidirectional"))
      (node (ref "RGB22") (pin "RC") (pinfunction "RC_RC") (pintype "bidirectional"))
    )
    (net (code "407") (name "Net-(RGB22-PadBA)") (class "Default")
      (node (ref "RGB22") (pin "BA") (pinfunction "BA_BA") (pintype "bidirectional"))
      (node (ref "RGB23") (pin "BC") (pinfunction "BC_BC") (pintype "bidirectional"))
    )
    (net (code "408") (name "Net-(RGB22-PadGA)") (class "Default")
      (node (ref "RGB22") (pin "GA") (pinfunction "GA_GA") (pintype "bidirectional"))
      (node (ref "RGB23") (pin "GC") (pinfunction "GC_GC") (pintype "bidirectional"))
    )
    (net (code "409") (name "Net-(RGB22-PadRA)") (class "Default")
      (node (ref "RGB22") (pin "RA") (pinfunction "RA_RA") (pintype "bidirectional"))
      (node (ref "RGB23") (pin "RC") (pinfunction "RC_RC") (pintype "bidirectional"))
    )
    (net (code "410") (name "Net-(RGB23-PadBA)") (class "Default")
      (node (ref "RGB23") (pin "BA") (pinfunction "BA_BA") (pintype "bidirectional"))
      (node (ref "RGB24") (pin "BC") (pinfunction "BC_BC") (pintype "bidirectional"))
    )
    (net (code "411") (name "Net-(RGB23-PadGA)") (class "Default")
      (node (ref "RGB23") (pin "GA") (pinfunction "GA_GA") (pintype "bidirectional"))
      (node (ref "RGB24") (pin "GC") (pinfunction "GC_GC") (pintype "bidirectional"))
    )
    (net (code "412") (name "Net-(RGB23-PadRA)") (class "Default")
      (node (ref "RGB23") (pin "RA") (pinfunction "RA_RA") (pintype "bidirectional"))
      (node (ref "RGB24") (pin "RC") (pinfunction "RC_RC") (pintype "bidirectional"))
    )
    (net (code "413") (name "Net-(RGB25-PadBA)") (class "Default")
      (node (ref "RGB25") (pin "BA") (pinfunction "BA_BA") (pintype "bidirectional"))
      (node (ref "RGB26") (pin "BC") (pinfunction "BC_BC") (pintype "bidirectional"))
    )
    (net (code "414") (name "Net-(RGB25-PadGA)") (class "Default")
      (node (ref "RGB25") (pin "GA") (pinfunction "GA_GA") (pintype "bidirectional"))
      (node (ref "RGB26") (pin "GC") (pinfunction "GC_GC") (pintype "bidirectional"))
    )
    (net (code "415") (name "Net-(RGB25-PadRA)") (class "Default")
      (node (ref "RGB25") (pin "RA") (pinfunction "RA_RA") (pintype "bidirectional"))
      (node (ref "RGB26") (pin "RC") (pinfunction "RC_RC") (pintype "bidirectional"))
    )
    (net (code "416") (name "Net-(RGB26-PadBA)") (class "Default")
      (node (ref "RGB26") (pin "BA") (pinfunction "BA_BA") (pintype "bidirectional"))
      (node (ref "RGB27") (pin "BC") (pinfunction "BC_BC") (pintype "bidirectional"))
    )
    (net (code "417") (name "Net-(RGB26-PadGA)") (class "Default")
      (node (ref "RGB26") (pin "GA") (pinfunction "GA_GA") (pintype "bidirectional"))
      (node (ref "RGB27") (pin "GC") (pinfunction "GC_GC") (pintype "bidirectional"))
    )
    (net (code "418") (name "Net-(RGB26-PadRA)") (class "Default")
      (node (ref "RGB26") (pin "RA") (pinfunction "RA_RA") (pintype "bidirectional"))
      (node (ref "RGB27") (pin "RC") (pinfunction "RC_RC") (pintype "bidirectional"))
    )
    (net (code "419") (name "Net-(RGB27-PadBA)") (class "Default")
      (node (ref "RGB27") (pin "BA") (pinfunction "BA_BA") (pintype "bidirectional"))
      (node (ref "RGB28") (pin "BC") (pinfunction "BC_BC") (pintype "bidirectional"))
    )
    (net (code "420") (name "Net-(RGB27-PadGA)") (class "Default")
      (node (ref "RGB27") (pin "GA") (pinfunction "GA_GA") (pintype "bidirectional"))
      (node (ref "RGB28") (pin "GC") (pinfunction "GC_GC") (pintype "bidirectional"))
    )
    (net (code "421") (name "Net-(RGB27-PadRA)") (class "Default")
      (node (ref "RGB27") (pin "RA") (pinfunction "RA_RA") (pintype "bidirectional"))
      (node (ref "RGB28") (pin "RC") (pinfunction "RC_RC") (pintype "bidirectional"))
    )
    (net (code "422") (name "Net-(RGB28-PadBA)") (class "Default")
      (node (ref "RGB28") (pin "BA") (pinfunction "BA_BA") (pintype "bidirectional"))
      (node (ref "RGB29") (pin "BC") (pinfunction "BC_BC") (pintype "bidirectional"))
    )
    (net (code "423") (name "Net-(RGB28-PadGA)") (class "Default")
      (node (ref "RGB28") (pin "GA") (pinfunction "GA_GA") (pintype "bidirectional"))
      (node (ref "RGB29") (pin "GC") (pinfunction "GC_GC") (pintype "bidirectional"))
    )
    (net (code "424") (name "Net-(RGB28-PadRA)") (class "Default")
      (node (ref "RGB28") (pin "RA") (pinfunction "RA_RA") (pintype "bidirectional"))
      (node (ref "RGB29") (pin "RC") (pinfunction "RC_RC") (pintype "bidirectional"))
    )
    (net (code "425") (name "Net-(RGB29-PadBA)") (class "Default")
      (node (ref "RGB29") (pin "BA") (pinfunction "BA_BA") (pintype "bidirectional"))
      (node (ref "RGB30") (pin "BC") (pinfunction "BC_BC") (pintype "bidirectional"))
    )
    (net (code "426") (name "Net-(RGB29-PadGA)") (class "Default")
      (node (ref "RGB29") (pin "GA") (pinfunction "GA_GA") (pintype "bidirectional"))
      (node (ref "RGB30") (pin "GC") (pinfunction "GC_GC") (pintype "bidirectional"))
    )
    (net (code "427") (name "Net-(RGB29-PadRA)") (class "Default")
      (node (ref "RGB29") (pin "RA") (pinfunction "RA_RA") (pintype "bidirectional"))
      (node (ref "RGB30") (pin "RC") (pinfunction "RC_RC") (pintype "bidirectional"))
    )
    (net (code "428") (name "Net-(RGB30-PadBA)") (class "Default")
      (node (ref "RGB30") (pin "BA") (pinfunction "BA_BA") (pintype "bidirectional"))
      (node (ref "RGB31") (pin "BC") (pinfunction "BC_BC") (pintype "bidirectional"))
    )
    (net (code "429") (name "Net-(RGB30-PadGA)") (class "Default")
      (node (ref "RGB30") (pin "GA") (pinfunction "GA_GA") (pintype "bidirectional"))
      (node (ref "RGB31") (pin "GC") (pinfunction "GC_GC") (pintype "bidirectional"))
    )
    (net (code "430") (name "Net-(RGB30-PadRA)") (class "Default")
      (node (ref "RGB30") (pin "RA") (pinfunction "RA_RA") (pintype "bidirectional"))
      (node (ref "RGB31") (pin "RC") (pinfunction "RC_RC") (pintype "bidirectional"))
    )
    (net (code "431") (name "Net-(RGB31-PadBA)") (class "Default")
      (node (ref "RGB31") (pin "BA") (pinfunction "BA_BA") (pintype "bidirectional"))
      (node (ref "RGB32") (pin "BC") (pinfunction "BC_BC") (pintype "bidirectional"))
    )
    (net (code "432") (name "Net-(RGB31-PadGA)") (class "Default")
      (node (ref "RGB31") (pin "GA") (pinfunction "GA_GA") (pintype "bidirectional"))
      (node (ref "RGB32") (pin "GC") (pinfunction "GC_GC") (pintype "bidirectional"))
    )
    (net (code "433") (name "Net-(RGB31-PadRA)") (class "Default")
      (node (ref "RGB31") (pin "RA") (pinfunction "RA_RA") (pintype "bidirectional"))
      (node (ref "RGB32") (pin "RC") (pinfunction "RC_RC") (pintype "bidirectional"))
    )
    (net (code "434") (name "Net-(RGB33-PadBA)") (class "Default")
      (node (ref "RGB33") (pin "BA") (pinfunction "BA_BA") (pintype "bidirectional"))
      (node (ref "RGB34") (pin "BC") (pinfunction "BC_BC") (pintype "bidirectional"))
    )
    (net (code "435") (name "Net-(RGB33-PadGA)") (class "Default")
      (node (ref "RGB33") (pin "GA") (pinfunction "GA_GA") (pintype "bidirectional"))
      (node (ref "RGB34") (pin "GC") (pinfunction "GC_GC") (pintype "bidirectional"))
    )
    (net (code "436") (name "Net-(RGB33-PadRA)") (class "Default")
      (node (ref "RGB33") (pin "RA") (pinfunction "RA_RA") (pintype "bidirectional"))
      (node (ref "RGB34") (pin "RC") (pinfunction "RC_RC") (pintype "bidirectional"))
    )
    (net (code "437") (name "Net-(RGB34-PadBA)") (class "Default")
      (node (ref "RGB34") (pin "BA") (pinfunction "BA_BA") (pintype "bidirectional"))
      (node (ref "RGB35") (pin "BC") (pinfunction "BC_BC") (pintype "bidirectional"))
    )
    (net (code "438") (name "Net-(RGB34-PadGA)") (class "Default")
      (node (ref "RGB34") (pin "GA") (pinfunction "GA_GA") (pintype "bidirectional"))
      (node (ref "RGB35") (pin "GC") (pinfunction "GC_GC") (pintype "bidirectional"))
    )
    (net (code "439") (name "Net-(RGB34-PadRA)") (class "Default")
      (node (ref "RGB34") (pin "RA") (pinfunction "RA_RA") (pintype "bidirectional"))
      (node (ref "RGB35") (pin "RC") (pinfunction "RC_RC") (pintype "bidirectional"))
    )
    (net (code "440") (name "Net-(RGB35-PadBA)") (class "Default")
      (node (ref "RGB35") (pin "BA") (pinfunction "BA_BA") (pintype "bidirectional"))
      (node (ref "RGB36") (pin "BC") (pinfunction "BC_BC") (pintype "bidirectional"))
    )
    (net (code "441") (name "Net-(RGB35-PadGA)") (class "Default")
      (node (ref "RGB35") (pin "GA") (pinfunction "GA_GA") (pintype "bidirectional"))
      (node (ref "RGB36") (pin "GC") (pinfunction "GC_GC") (pintype "bidirectional"))
    )
    (net (code "442") (name "Net-(RGB35-PadRA)") (class "Default")
      (node (ref "RGB35") (pin "RA") (pinfunction "RA_RA") (pintype "bidirectional"))
      (node (ref "RGB36") (pin "RC") (pinfunction "RC_RC") (pintype "bidirectional"))
    )
    (net (code "443") (name "Net-(RGB36-PadBA)") (class "Default")
      (node (ref "RGB36") (pin "BA") (pinfunction "BA_BA") (pintype "bidirectional"))
      (node (ref "RGB37") (pin "BC") (pinfunction "BC_BC") (pintype "bidirectional"))
    )
    (net (code "444") (name "Net-(RGB36-PadGA)") (class "Default")
      (node (ref "RGB36") (pin "GA") (pinfunction "GA_GA") (pintype "bidirectional"))
      (node (ref "RGB37") (pin "GC") (pinfunction "GC_GC") (pintype "bidirectional"))
    )
    (net (code "445") (name "Net-(RGB36-PadRA)") (class "Default")
      (node (ref "RGB36") (pin "RA") (pinfunction "RA_RA") (pintype "bidirectional"))
      (node (ref "RGB37") (pin "RC") (pinfunction "RC_RC") (pintype "bidirectional"))
    )
    (net (code "446") (name "Net-(RGB37-PadBA)") (class "Default")
      (node (ref "RGB37") (pin "BA") (pinfunction "BA_BA") (pintype "bidirectional"))
      (node (ref "RGB38") (pin "BC") (pinfunction "BC_BC") (pintype "bidirectional"))
    )
    (net (code "447") (name "Net-(RGB37-PadGA)") (class "Default")
      (node (ref "RGB37") (pin "GA") (pinfunction "GA_GA") (pintype "bidirectional"))
      (node (ref "RGB38") (pin "GC") (pinfunction "GC_GC") (pintype "bidirectional"))
    )
    (net (code "448") (name "Net-(RGB37-PadRA)") (class "Default")
      (node (ref "RGB37") (pin "RA") (pinfunction "RA_RA") (pintype "bidirectional"))
      (node (ref "RGB38") (pin "RC") (pinfunction "RC_RC") (pintype "bidirectional"))
    )
    (net (code "449") (name "Net-(RGB38-PadBA)") (class "Default")
      (node (ref "RGB38") (pin "BA") (pinfunction "BA_BA") (pintype "bidirectional"))
      (node (ref "RGB39") (pin "BC") (pinfunction "BC_BC") (pintype "bidirectional"))
    )
    (net (code "450") (name "Net-(RGB38-PadGA)") (class "Default")
      (node (ref "RGB38") (pin "GA") (pinfunction "GA_GA") (pintype "bidirectional"))
      (node (ref "RGB39") (pin "GC") (pinfunction "GC_GC") (pintype "bidirectional"))
    )
    (net (code "451") (name "Net-(RGB38-PadRA)") (class "Default")
      (node (ref "RGB38") (pin "RA") (pinfunction "RA_RA") (pintype "bidirectional"))
      (node (ref "RGB39") (pin "RC") (pinfunction "RC_RC") (pintype "bidirectional"))
    )
    (net (code "452") (name "Net-(RGB39-PadBA)") (class "Default")
      (node (ref "RGB39") (pin "BA") (pinfunction "BA_BA") (pintype "bidirectional"))
      (node (ref "RGB40") (pin "BC") (pinfunction "BC_BC") (pintype "bidirectional"))
    )
    (net (code "453") (name "Net-(RGB39-PadGA)") (class "Default")
      (node (ref "RGB39") (pin "GA") (pinfunction "GA_GA") (pintype "bidirectional"))
      (node (ref "RGB40") (pin "GC") (pinfunction "GC_GC") (pintype "bidirectional"))
    )
    (net (code "454") (name "Net-(RGB39-PadRA)") (class "Default")
      (node (ref "RGB39") (pin "RA") (pinfunction "RA_RA") (pintype "bidirectional"))
      (node (ref "RGB40") (pin "RC") (pinfunction "RC_RC") (pintype "bidirectional"))
    )
    (net (code "455") (name "Net-(RGB41-PadBA)") (class "Default")
      (node (ref "RGB41") (pin "BA") (pinfunction "BA_BA") (pintype "bidirectional"))
      (node (ref "RGB42") (pin "BC") (pinfunction "BC_BC") (pintype "bidirectional"))
    )
    (net (code "456") (name "Net-(RGB41-PadGA)") (class "Default")
      (node (ref "RGB41") (pin "GA") (pinfunction "GA_GA") (pintype "bidirectional"))
      (node (ref "RGB42") (pin "GC") (pinfunction "GC_GC") (pintype "bidirectional"))
    )
    (net (code "457") (name "Net-(RGB41-PadRA)") (class "Default")
      (node (ref "RGB41") (pin "RA") (pinfunction "RA_RA") (pintype "bidirectional"))
      (node (ref "RGB42") (pin "RC") (pinfunction "RC_RC") (pintype "bidirectional"))
    )
    (net (code "458") (name "Net-(RGB42-PadBA)") (class "Default")
      (node (ref "RGB42") (pin "BA") (pinfunction "BA_BA") (pintype "bidirectional"))
      (node (ref "RGB43") (pin "BC") (pinfunction "BC_BC") (pintype "bidirectional"))
    )
    (net (code "459") (name "Net-(RGB42-PadGA)") (class "Default")
      (node (ref "RGB42") (pin "GA") (pinfunction "GA_GA") (pintype "bidirectional"))
      (node (ref "RGB43") (pin "GC") (pinfunction "GC_GC") (pintype "bidirectional"))
    )
    (net (code "460") (name "Net-(RGB42-PadRA)") (class "Default")
      (node (ref "RGB42") (pin "RA") (pinfunction "RA_RA") (pintype "bidirectional"))
      (node (ref "RGB43") (pin "RC") (pinfunction "RC_RC") (pintype "bidirectional"))
    )
    (net (code "461") (name "Net-(RGB43-PadBA)") (class "Default")
      (node (ref "RGB43") (pin "BA") (pinfunction "BA_BA") (pintype "bidirectional"))
      (node (ref "RGB44") (pin "BC") (pinfunction "BC_BC") (pintype "bidirectional"))
    )
    (net (code "462") (name "Net-(RGB43-PadGA)") (class "Default")
      (node (ref "RGB43") (pin "GA") (pinfunction "GA_GA") (pintype "bidirectional"))
      (node (ref "RGB44") (pin "GC") (pinfunction "GC_GC") (pintype "bidirectional"))
    )
    (net (code "463") (name "Net-(RGB43-PadRA)") (class "Default")
      (node (ref "RGB43") (pin "RA") (pinfunction "RA_RA") (pintype "bidirectional"))
      (node (ref "RGB44") (pin "RC") (pinfunction "RC_RC") (pintype "bidirectional"))
    )
    (net (code "464") (name "Net-(RGB44-PadBA)") (class "Default")
      (node (ref "RGB44") (pin "BA") (pinfunction "BA_BA") (pintype "bidirectional"))
      (node (ref "RGB45") (pin "BC") (pinfunction "BC_BC") (pintype "bidirectional"))
    )
    (net (code "465") (name "Net-(RGB44-PadGA)") (class "Default")
      (node (ref "RGB44") (pin "GA") (pinfunction "GA_GA") (pintype "bidirectional"))
      (node (ref "RGB45") (pin "GC") (pinfunction "GC_GC") (pintype "bidirectional"))
    )
    (net (code "466") (name "Net-(RGB44-PadRA)") (class "Default")
      (node (ref "RGB44") (pin "RA") (pinfunction "RA_RA") (pintype "bidirectional"))
      (node (ref "RGB45") (pin "RC") (pinfunction "RC_RC") (pintype "bidirectional"))
    )
    (net (code "467") (name "Net-(RGB45-PadBA)") (class "Default")
      (node (ref "RGB45") (pin "BA") (pinfunction "BA_BA") (pintype "bidirectional"))
      (node (ref "RGB46") (pin "BC") (pinfunction "BC_BC") (pintype "bidirectional"))
    )
    (net (code "468") (name "Net-(RGB45-PadGA)") (class "Default")
      (node (ref "RGB45") (pin "GA") (pinfunction "GA_GA") (pintype "bidirectional"))
      (node (ref "RGB46") (pin "GC") (pinfunction "GC_GC") (pintype "bidirectional"))
    )
    (net (code "469") (name "Net-(RGB45-PadRA)") (class "Default")
      (node (ref "RGB45") (pin "RA") (pinfunction "RA_RA") (pintype "bidirectional"))
      (node (ref "RGB46") (pin "RC") (pinfunction "RC_RC") (pintype "bidirectional"))
    )
    (net (code "470") (name "Net-(RGB46-PadBA)") (class "Default")
      (node (ref "RGB46") (pin "BA") (pinfunction "BA_BA") (pintype "bidirectional"))
      (node (ref "RGB47") (pin "BC") (pinfunction "BC_BC") (pintype "bidirectional"))
    )
    (net (code "471") (name "Net-(RGB46-PadGA)") (class "Default")
      (node (ref "RGB46") (pin "GA") (pinfunction "GA_GA") (pintype "bidirectional"))
      (node (ref "RGB47") (pin "GC") (pinfunction "GC_GC") (pintype "bidirectional"))
    )
    (net (code "472") (name "Net-(RGB46-PadRA)") (class "Default")
      (node (ref "RGB46") (pin "RA") (pinfunction "RA_RA") (pintype "bidirectional"))
      (node (ref "RGB47") (pin "RC") (pinfunction "RC_RC") (pintype "bidirectional"))
    )
    (net (code "473") (name "Net-(RGB47-PadBA)") (class "Default")
      (node (ref "RGB47") (pin "BA") (pinfunction "BA_BA") (pintype "bidirectional"))
      (node (ref "RGB48") (pin "BC") (pinfunction "BC_BC") (pintype "bidirectional"))
    )
    (net (code "474") (name "Net-(RGB47-PadGA)") (class "Default")
      (node (ref "RGB47") (pin "GA") (pinfunction "GA_GA") (pintype "bidirectional"))
      (node (ref "RGB48") (pin "GC") (pinfunction "GC_GC") (pintype "bidirectional"))
    )
    (net (code "475") (name "Net-(RGB47-PadRA)") (class "Default")
      (node (ref "RGB47") (pin "RA") (pinfunction "RA_RA") (pintype "bidirectional"))
      (node (ref "RGB48") (pin "RC") (pinfunction "RC_RC") (pintype "bidirectional"))
    )
    (net (code "476") (name "Net-(RGB49-PadBA)") (class "Default")
      (node (ref "RGB49") (pin "BA") (pinfunction "BA_BA") (pintype "bidirectional"))
      (node (ref "RGB50") (pin "BC") (pinfunction "BC_BC") (pintype "bidirectional"))
    )
    (net (code "477") (name "Net-(RGB49-PadGA)") (class "Default")
      (node (ref "RGB49") (pin "GA") (pinfunction "GA_GA") (pintype "bidirectional"))
      (node (ref "RGB50") (pin "GC") (pinfunction "GC_GC") (pintype "bidirectional"))
    )
    (net (code "478") (name "Net-(RGB49-PadRA)") (class "Default")
      (node (ref "RGB49") (pin "RA") (pinfunction "RA_RA") (pintype "bidirectional"))
      (node (ref "RGB50") (pin "RC") (pinfunction "RC_RC") (pintype "bidirectional"))
    )
    (net (code "479") (name "Net-(RGB50-PadBA)") (class "Default")
      (node (ref "RGB50") (pin "BA") (pinfunction "BA_BA") (pintype "bidirectional"))
      (node (ref "RGB51") (pin "BC") (pinfunction "BC_BC") (pintype "bidirectional"))
    )
    (net (code "480") (name "Net-(RGB50-PadGA)") (class "Default")
      (node (ref "RGB50") (pin "GA") (pinfunction "GA_GA") (pintype "bidirectional"))
      (node (ref "RGB51") (pin "GC") (pinfunction "GC_GC") (pintype "bidirectional"))
    )
    (net (code "481") (name "Net-(RGB50-PadRA)") (class "Default")
      (node (ref "RGB50") (pin "RA") (pinfunction "RA_RA") (pintype "bidirectional"))
      (node (ref "RGB51") (pin "RC") (pinfunction "RC_RC") (pintype "bidirectional"))
    )
    (net (code "482") (name "Net-(RGB51-PadBA)") (class "Default")
      (node (ref "RGB51") (pin "BA") (pinfunction "BA_BA") (pintype "bidirectional"))
      (node (ref "RGB52") (pin "BC") (pinfunction "BC_BC") (pintype "bidirectional"))
    )
    (net (code "483") (name "Net-(RGB51-PadGA)") (class "Default")
      (node (ref "RGB51") (pin "GA") (pinfunction "GA_GA") (pintype "bidirectional"))
      (node (ref "RGB52") (pin "GC") (pinfunction "GC_GC") (pintype "bidirectional"))
    )
    (net (code "484") (name "Net-(RGB51-PadRA)") (class "Default")
      (node (ref "RGB51") (pin "RA") (pinfunction "RA_RA") (pintype "bidirectional"))
      (node (ref "RGB52") (pin "RC") (pinfunction "RC_RC") (pintype "bidirectional"))
    )
    (net (code "485") (name "Net-(RGB52-PadBA)") (class "Default")
      (node (ref "RGB52") (pin "BA") (pinfunction "BA_BA") (pintype "bidirectional"))
      (node (ref "RGB53") (pin "BC") (pinfunction "BC_BC") (pintype "bidirectional"))
    )
    (net (code "486") (name "Net-(RGB52-PadGA)") (class "Default")
      (node (ref "RGB52") (pin "GA") (pinfunction "GA_GA") (pintype "bidirectional"))
      (node (ref "RGB53") (pin "GC") (pinfunction "GC_GC") (pintype "bidirectional"))
    )
    (net (code "487") (name "Net-(RGB52-PadRA)") (class "Default")
      (node (ref "RGB52") (pin "RA") (pinfunction "RA_RA") (pintype "bidirectional"))
      (node (ref "RGB53") (pin "RC") (pinfunction "RC_RC") (pintype "bidirectional"))
    )
    (net (code "488") (name "Net-(RGB53-PadBA)") (class "Default")
      (node (ref "RGB53") (pin "BA") (pinfunction "BA_BA") (pintype "bidirectional"))
      (node (ref "RGB54") (pin "BC") (pinfunction "BC_BC") (pintype "bidirectional"))
    )
    (net (code "489") (name "Net-(RGB53-PadGA)") (class "Default")
      (node (ref "RGB53") (pin "GA") (pinfunction "GA_GA") (pintype "bidirectional"))
      (node (ref "RGB54") (pin "GC") (pinfunction "GC_GC") (pintype "bidirectional"))
    )
    (net (code "490") (name "Net-(RGB53-PadRA)") (class "Default")
      (node (ref "RGB53") (pin "RA") (pinfunction "RA_RA") (pintype "bidirectional"))
      (node (ref "RGB54") (pin "RC") (pinfunction "RC_RC") (pintype "bidirectional"))
    )
    (net (code "491") (name "Net-(RGB54-PadBA)") (class "Default")
      (node (ref "RGB54") (pin "BA") (pinfunction "BA_BA") (pintype "bidirectional"))
      (node (ref "RGB55") (pin "BC") (pinfunction "BC_BC") (pintype "bidirectional"))
    )
    (net (code "492") (name "Net-(RGB54-PadGA)") (class "Default")
      (node (ref "RGB54") (pin "GA") (pinfunction "GA_GA") (pintype "bidirectional"))
      (node (ref "RGB55") (pin "GC") (pinfunction "GC_GC") (pintype "bidirectional"))
    )
    (net (code "493") (name "Net-(RGB54-PadRA)") (class "Default")
      (node (ref "RGB54") (pin "RA") (pinfunction "RA_RA") (pintype "bidirectional"))
      (node (ref "RGB55") (pin "RC") (pinfunction "RC_RC") (pintype "bidirectional"))
    )
    (net (code "494") (name "Net-(RGB55-PadBA)") (class "Default")
      (node (ref "RGB55") (pin "BA") (pinfunction "BA_BA") (pintype "bidirectional"))
      (node (ref "RGB56") (pin "BC") (pinfunction "BC_BC") (pintype "bidirectional"))
    )
    (net (code "495") (name "Net-(RGB55-PadGA)") (class "Default")
      (node (ref "RGB55") (pin "GA") (pinfunction "GA_GA") (pintype "bidirectional"))
      (node (ref "RGB56") (pin "GC") (pinfunction "GC_GC") (pintype "bidirectional"))
    )
    (net (code "496") (name "Net-(RGB55-PadRA)") (class "Default")
      (node (ref "RGB55") (pin "RA") (pinfunction "RA_RA") (pintype "bidirectional"))
      (node (ref "RGB56") (pin "RC") (pinfunction "RC_RC") (pintype "bidirectional"))
    )
    (net (code "497") (name "Net-(RGB57-PadBA)") (class "Default")
      (node (ref "RGB57") (pin "BA") (pinfunction "BA_BA") (pintype "bidirectional"))
      (node (ref "RGB58") (pin "BC") (pinfunction "BC_BC") (pintype "bidirectional"))
    )
    (net (code "498") (name "Net-(RGB57-PadGA)") (class "Default")
      (node (ref "RGB57") (pin "GA") (pinfunction "GA_GA") (pintype "bidirectional"))
      (node (ref "RGB58") (pin "GC") (pinfunction "GC_GC") (pintype "bidirectional"))
    )
    (net (code "499") (name "Net-(RGB57-PadRA)") (class "Default")
      (node (ref "RGB57") (pin "RA") (pinfunction "RA_RA") (pintype "bidirectional"))
      (node (ref "RGB58") (pin "RC") (pinfunction "RC_RC") (pintype "bidirectional"))
    )
    (net (code "500") (name "Net-(RGB58-PadBA)") (class "Default")
      (node (ref "RGB58") (pin "BA") (pinfunction "BA_BA") (pintype "bidirectional"))
      (node (ref "RGB59") (pin "BC") (pinfunction "BC_BC") (pintype "bidirectional"))
    )
    (net (code "501") (name "Net-(RGB58-PadGA)") (class "Default")
      (node (ref "RGB58") (pin "GA") (pinfunction "GA_GA") (pintype "bidirectional"))
      (node (ref "RGB59") (pin "GC") (pinfunction "GC_GC") (pintype "bidirectional"))
    )
    (net (code "502") (name "Net-(RGB58-PadRA)") (class "Default")
      (node (ref "RGB58") (pin "RA") (pinfunction "RA_RA") (pintype "bidirectional"))
      (node (ref "RGB59") (pin "RC") (pinfunction "RC_RC") (pintype "bidirectional"))
    )
    (net (code "503") (name "Net-(RGB59-PadBA)") (class "Default")
      (node (ref "RGB59") (pin "BA") (pinfunction "BA_BA") (pintype "bidirectional"))
      (node (ref "RGB60") (pin "BC") (pinfunction "BC_BC") (pintype "bidirectional"))
    )
    (net (code "504") (name "Net-(RGB59-PadGA)") (class "Default")
      (node (ref "RGB59") (pin "GA") (pinfunction "GA_GA") (pintype "bidirectional"))
      (node (ref "RGB60") (pin "GC") (pinfunction "GC_GC") (pintype "bidirectional"))
    )
    (net (code "505") (name "Net-(RGB59-PadRA)") (class "Default")
      (node (ref "RGB59") (pin "RA") (pinfunction "RA_RA") (pintype "bidirectional"))
      (node (ref "RGB60") (pin "RC") (pinfunction "RC_RC") (pintype "bidirectional"))
    )
    (net (code "506") (name "Net-(RGB60-PadBA)") (class "Default")
      (node (ref "RGB60") (pin "BA") (pinfunction "BA_BA") (pintype "bidirectional"))
      (node (ref "RGB61") (pin "BC") (pinfunction "BC_BC") (pintype "bidirectional"))
    )
    (net (code "507") (name "Net-(RGB60-PadGA)") (class "Default")
      (node (ref "RGB60") (pin "GA") (pinfunction "GA_GA") (pintype "bidirectional"))
      (node (ref "RGB61") (pin "GC") (pinfunction "GC_GC") (pintype "bidirectional"))
    )
    (net (code "508") (name "Net-(RGB60-PadRA)") (class "Default")
      (node (ref "RGB60") (pin "RA") (pinfunction "RA_RA") (pintype "bidirectional"))
      (node (ref "RGB61") (pin "RC") (pinfunction "RC_RC") (pintype "bidirectional"))
    )
    (net (code "509") (name "Net-(RGB61-PadBA)") (class "Default")
      (node (ref "RGB61") (pin "BA") (pinfunction "BA_BA") (pintype "bidirectional"))
      (node (ref "RGB62") (pin "BC") (pinfunction "BC_BC") (pintype "bidirectional"))
    )
    (net (code "510") (name "Net-(RGB61-PadGA)") (class "Default")
      (node (ref "RGB61") (pin "GA") (pinfunction "GA_GA") (pintype "bidirectional"))
      (node (ref "RGB62") (pin "GC") (pinfunction "GC_GC") (pintype "bidirectional"))
    )
    (net (code "511") (name "Net-(RGB61-PadRA)") (class "Default")
      (node (ref "RGB61") (pin "RA") (pinfunction "RA_RA") (pintype "bidirectional"))
      (node (ref "RGB62") (pin "RC") (pinfunction "RC_RC") (pintype "bidirectional"))
    )
    (net (code "512") (name "Net-(RGB62-PadBA)") (class "Default")
      (node (ref "RGB62") (pin "BA") (pinfunction "BA_BA") (pintype "bidirectional"))
      (node (ref "RGB63") (pin "BC") (pinfunction "BC_BC") (pintype "bidirectional"))
    )
    (net (code "513") (name "Net-(RGB62-PadGA)") (class "Default")
      (node (ref "RGB62") (pin "GA") (pinfunction "GA_GA") (pintype "bidirectional"))
      (node (ref "RGB63") (pin "GC") (pinfunction "GC_GC") (pintype "bidirectional"))
    )
    (net (code "514") (name "Net-(RGB62-PadRA)") (class "Default")
      (node (ref "RGB62") (pin "RA") (pinfunction "RA_RA") (pintype "bidirectional"))
      (node (ref "RGB63") (pin "RC") (pinfunction "RC_RC") (pintype "bidirectional"))
    )
    (net (code "515") (name "Net-(RGB63-PadBA)") (class "Default")
      (node (ref "RGB63") (pin "BA") (pinfunction "BA_BA") (pintype "bidirectional"))
      (node (ref "RGB64") (pin "BC") (pinfunction "BC_BC") (pintype "bidirectional"))
    )
    (net (code "516") (name "Net-(RGB63-PadGA)") (class "Default")
      (node (ref "RGB63") (pin "GA") (pinfunction "GA_GA") (pintype "bidirectional"))
      (node (ref "RGB64") (pin "GC") (pinfunction "GC_GC") (pintype "bidirectional"))
    )
    (net (code "517") (name "Net-(RGB63-PadRA)") (class "Default")
      (node (ref "RGB63") (pin "RA") (pinfunction "RA_RA") (pintype "bidirectional"))
      (node (ref "RGB64") (pin "RC") (pinfunction "RC_RC") (pintype "bidirectional"))
    )
    (net (code "518") (name "Net-(U1-SW)") (class "Default")
      (node (ref "D49") (pin "A") (pinfunction "A_A") (pintype "bidirectional"))
      (node (ref "L1") (pin "2") (pinfunction "2_2") (pintype "passive"))
      (node (ref "U1") (pin "5") (pinfunction "SW_5") (pintype "bidirectional"))
      (node (ref "U1") (pin "6") (pinfunction "SW1_6") (pintype "bidirectional"))
    )
    (net (code "519") (name "Net-(U2-SW)") (class "Default")
      (node (ref "D82") (pin "A") (pinfunction "A_A") (pintype "bidirectional"))
      (node (ref "L2") (pin "2") (pinfunction "2_2") (pintype "passive"))
      (node (ref "U2") (pin "5") (pinfunction "SW_5") (pintype "bidirectional"))
      (node (ref "U2") (pin "6") (pinfunction "SW1_6") (pintype "bidirectional"))
    )
    (net (code "520") (name "Net-(U3-SW)") (class "Default")
      (node (ref "D179") (pin "A") (pinfunction "A_A") (pintype "bidirectional"))
      (node (ref "L3") (pin "2") (pinfunction "2_2") (pintype "passive"))
      (node (ref "U3") (pin "5") (pinfunction "SW_5") (pintype "bidirectional"))
      (node (ref "U3") (pin "6") (pinfunction "SW1_6") (pintype "bidirectional"))
    )
    (net (code "521") (name "Net-(U4-SW)") (class "Default")
      (node (ref "D212") (pin "A") (pinfunction "A_A") (pintype "bidirectional"))
      (node (ref "L4") (pin "2") (pinfunction "2_2") (pintype "passive"))
      (node (ref "U4") (pin "5") (pinfunction "SW_5") (pintype "bidirectional"))
      (node (ref "U4") (pin "6") (pinfunction "SW1_6") (pintype "bidirectional"))
    )
    (net (code "522") (name "RED1") (class "Default")
      (node (ref "P1") (pin "11") (pinfunction "11_11") (pintype "bidirectional"))
      (node (ref "Q3") (pin "2") (pinfunction "B1_2") (pintype "bidirectional"))
      (node (ref "R8") (pin "2") (pinfunction "2_2") (pintype "passive"))
    )
    (net (code "523") (name "RED1F") (class "Default")
      (node (ref "P1") (pin "12") (pinfunction "12_12") (pintype "bidirectional"))
      (node (ref "Q3") (pin "1") (pinfunction "E1_1") (pintype "bidirectional"))
      (node (ref "R11") (pin "2") (pinfunction "2_2") (pintype "passive"))
    )
    (net (code "524") (name "RED1K") (class "Default")
      (node (ref "JMP2") (pin "1") (pinfunction "1_1") (pintype "bidirectional"))
      (node (ref "RGB1") (pin "RC") (pinfunction "RC_RC") (pintype "bidirectional"))
    )
    (net (code "525") (name "RED1K2") (class "Default")
      (node (ref "Q3") (pin "5") (pinfunction "C2_5") (pintype "bidirectional"))
      (node (ref "Q3") (pin "56") (pinfunction "C2_56") (pintype "bidirectional"))
      (node (ref "Q3") (pin "6") (pinfunction "C2_6") (pintype "bidirectional"))
      (node (ref "RGB9") (pin "RC") (pinfunction "RC_RC") (pintype "bidirectional"))
    )
    (net (code "526") (name "RED2") (class "Default")
      (node (ref "P1") (pin "6") (pinfunction "6_6") (pintype "bidirectional"))
      (node (ref "Q6") (pin "2") (pinfunction "B1_2") (pintype "bidirectional"))
      (node (ref "R33") (pin "2") (pinfunction "2_2") (pintype "passive"))
    )
    (net (code "527") (name "RED2F") (class "Default")
      (node (ref "P1") (pin "4") (pinfunction "4_4") (pintype "bidirectional"))
      (node (ref "Q6") (pin "1") (pinfunction "E1_1") (pintype "bidirectional"))
      (node (ref "R29") (pin "2") (pinfunction "2_2") (pintype "passive"))
    )
    (net (code "528") (name "RED2K1") (class "Default")
      (node (ref "JMP6") (pin "1") (pinfunction "1_1") (pintype "bidirectional"))
      (node (ref "RGB17") (pin "RC") (pinfunction "RC_RC") (pintype "bidirectional"))
    )
    (net (code "529") (name "RED2K2") (class "Default")
      (node (ref "Q6") (pin "5") (pinfunction "C2_5") (pintype "bidirectional"))
      (node (ref "Q6") (pin "56") (pinfunction "C2_56") (pintype "bidirectional"))
      (node (ref "Q6") (pin "6") (pinfunction "C2_6") (pintype "bidirectional"))
      (node (ref "RGB25") (pin "RC") (pinfunction "RC_RC") (pintype "bidirectional"))
    )
    (net (code "530") (name "RED3") (class "Default")
      (node (ref "P2") (pin "11") (pinfunction "11_11") (pintype "bidirectional"))
      (node (ref "Q9") (pin "2") (pinfunction "B1_2") (pintype "bidirectional"))
      (node (ref "R42") (pin "2") (pinfunction "2_2") (pintype "passive"))
    )
    (net (code "531") (name "RED3F") (class "Default")
      (node (ref "P2") (pin "12") (pinfunction "12_12") (pintype "bidirectional"))
      (node (ref "Q9") (pin "1") (pinfunction "E1_1") (pintype "bidirectional"))
      (node (ref "R45") (pin "2") (pinfunction "2_2") (pintype "passive"))
    )
    (net (code "532") (name "RED3K") (class "Default")
      (node (ref "JMP10") (pin "1") (pinfunction "1_1") (pintype "bidirectional"))
      (node (ref "RGB33") (pin "RC") (pinfunction "RC_RC") (pintype "bidirectional"))
    )
    (net (code "533") (name "RED4") (class "Default")
      (node (ref "P2") (pin "6") (pinfunction "6_6") (pintype "bidirectional"))
      (node (ref "Q12") (pin "2") (pinfunction "B1_2") (pintype "bidirectional"))
      (node (ref "R68") (pin "2") (pinfunction "2_2") (pintype "passive"))
    )
    (net (code "534") (name "RED4F") (class "Default")
      (node (ref "P2") (pin "4") (pinfunction "4_4") (pintype "bidirectional"))
      (node (ref "Q12") (pin "1") (pinfunction "E1_1") (pintype "bidirectional"))
      (node (ref "R63") (pin "2") (pinfunction "2_2") (pintype "passive"))
    )
    (net (code "535") (name "VIR1") (class "Default")
      (node (ref "C2") (pin "1") (pinfunction "1_1") (pintype "passive"))
      (node (ref "C20") (pin "1") (pinfunction "1_1") (pintype "passive"))
      (node (ref "C21") (pin "1") (pinfunction "1_1") (pintype "passive"))
      (node (ref "C3") (pin "1") (pinfunction "1_1") (pintype "passive"))
      (node (ref "C7") (pin "1") (pinfunction "1_1") (pintype "passive"))
      (node (ref "C8") (pin "1") (pinfunction "1_1") (pintype "passive"))
      (node (ref "D49") (pin "K") (pinfunction "K_K") (pintype "bidirectional"))
      (node (ref "D82") (pin "K") (pinfunction "K_K") (pintype "bidirectional"))
      (node (ref "JMP14") (pin "1") (pinfunction "1_1") (pintype "bidirectional"))
      (node (ref "JMP14") (pin "2") (pinfunction "2_2") (pintype "bidirectional"))
      (node (ref "JMP15") (pin "1") (pinfunction "1_1") (pintype "bidirectional"))
      (node (ref "JMP15") (pin "2") (pinfunction "2_2") (pintype "bidirectional"))
      (node (ref "JMP5") (pin "2") (pinfunction "2_2") (pintype "bidirectional"))
      (node (ref "R16") (pin "2") (pinfunction "2_2") (pintype "passive"))
      (node (ref "R18") (pin "1") (pinfunction "1_1") (pintype "passive"))
      (node (ref "R18") (pin "2") (pinfunction "2_2") (pintype "passive"))
      (node (ref "R19") (pin "2") (pinfunction "2_2") (pintype "passive"))
      (node (ref "U1") (pin "4") (pinfunction "VIN_4") (pintype "bidirectional"))
      (node (ref "U2") (pin "4") (pinfunction "VIN_4") (pintype "bidirectional"))
    )
    (net (code "536") (name "V_IR") (class "Default")
      (node (ref "C11") (pin "1") (pinfunction "1_1") (pintype "passive"))
      (node (ref "C12") (pin "1") (pinfunction "1_1") (pintype "passive"))
      (node (ref "C16") (pin "1") (pinfunction "1_1") (pintype "passive"))
      (node (ref "C17") (pin "1") (pinfunction "1_1") (pintype "passive"))
      (node (ref "C22") (pin "1") (pinfunction "1_1") (pintype "passive"))
      (node (ref "C23") (pin "1") (pinfunction "1_1") (pintype "passive"))
      (node (ref "D179") (pin "K") (pinfunction "K_K") (pintype "bidirectional"))
      (node (ref "D212") (pin "K") (pinfunction "K_K") (pintype "bidirectional"))
      (node (ref "JMP11") (pin "1") (pinfunction "1_1") (pintype "bidirectional"))
      (node (ref "JMP11") (pin "2") (pinfunction "2_2") (pintype "bidirectional"))
      (node (ref "JMP3") (pin "1") (pinfunction "1_1") (pintype "bidirectional"))
      (node (ref "JMP3") (pin "2") (pinfunction "2_2") (pintype "bidirectional"))
      (node (ref "JMP8") (pin "2") (pinfunction "2_2") (pintype "bidirectional"))
      (node (ref "R50") (pin "2") (pinfunction "2_2") (pintype "passive"))
      (node (ref "R52") (pin "1") (pinfunction "1_1") (pintype "passive"))
      (node (ref "R52") (pin "2") (pinfunction "2_2") (pintype "passive"))
      (node (ref "R53") (pin "2") (pinfunction "2_2") (pintype "passive"))
      (node (ref "U3") (pin "4") (pinfunction "VIN_4") (pintype "bidirectional"))
      (node (ref "U4") (pin "4") (pinfunction "VIN_4") (pintype "bidirectional"))
    )
    (net (code "537") (name "V_RGB") (class "Default")
      (node (ref "C1") (pin "+") (pinfunction "+_+") (pintype "passive"))
      (node (ref "C10") (pin "+") (pinfunction "+_+") (pintype "passive"))
      (node (ref "C19") (pin "+") (pinfunction "+_+") (pintype "passive"))
      (node (ref "J1") (pin "1A") (pinfunction "P$1_1A") (pintype "bidirectional"))
      (node (ref "J1") (pin "1B") (pinfunction "P$1_1B") (pintype "bidirectional"))
      (node (ref "JMP7") (pin "1") (pinfunction "1_1") (pintype "bidirectional"))
      (node (ref "JMP8") (pin "1") (pinfunction "1_1") (pintype "bidirectional"))
      (node (ref "P4") (pin "2") (pinfunction "2_2") (pintype "bidirectional"))
      (node (ref "P4") (pin "4") (pinfunction "4_4") (pintype "bidirectional"))
      (node (ref "RGB16") (pin "BA") (pinfunction "BA_BA") (pintype "bidirectional"))
      (node (ref "RGB16") (pin "GA") (pinfunction "GA_GA") (pintype "bidirectional"))
      (node (ref "RGB16") (pin "RA") (pinfunction "RA_RA") (pintype "bidirectional"))
      (node (ref "RGB24") (pin "BA") (pinfunction "BA_BA") (pintype "bidirectional"))
      (node (ref "RGB24") (pin "GA") (pinfunction "GA_GA") (pintype "bidirectional"))
      (node (ref "RGB24") (pin "RA") (pinfunction "RA_RA") (pintype "bidirectional"))
      (node (ref "RGB32") (pin "BA") (pinfunction "BA_BA") (pintype "bidirectional"))
      (node (ref "RGB32") (pin "GA") (pinfunction "GA_GA") (pintype "bidirectional"))
      (node (ref "RGB32") (pin "RA") (pinfunction "RA_RA") (pintype "bidirectional"))
      (node (ref "RGB40") (pin "BA") (pinfunction "BA_BA") (pintype "bidirectional"))
      (node (ref "RGB40") (pin "GA") (pinfunction "GA_GA") (pintype "bidirectional"))
      (node (ref "RGB40") (pin "RA") (pinfunction "RA_RA") (pintype "bidirectional"))
      (node (ref "RGB48") (pin "BA") (pinfunction "BA_BA") (pintype "bidirectional"))
      (node (ref "RGB48") (pin "GA") (pinfunction "GA_GA") (pintype "bidirectional"))
      (node (ref "RGB48") (pin "RA") (pinfunction "RA_RA") (pintype "bidirectional"))
      (node (ref "RGB56") (pin "BA") (pinfunction "BA_BA") (pintype "bidirectional"))
      (node (ref "RGB56") (pin "GA") (pinfunction "GA_GA") (pintype "bidirectional"))
      (node (ref "RGB56") (pin "RA") (pinfunction "RA_RA") (pintype "bidirectional"))
      (node (ref "RGB64") (pin "BA") (pinfunction "BA_BA") (pintype "bidirectional"))
      (node (ref "RGB64") (pin "GA") (pinfunction "GA_GA") (pintype "bidirectional"))
      (node (ref "RGB64") (pin "RA") (pinfunction "RA_RA") (pintype "bidirectional"))
      (node (ref "RGB8") (pin "BA") (pinfunction "BA_BA") (pintype "bidirectional"))
      (node (ref "RGB8") (pin "GA") (pinfunction "GA_GA") (pintype "bidirectional"))
      (node (ref "RGB8") (pin "RA") (pinfunction "RA_RA") (pintype "bidirectional"))
    )
    (net (code "538") (name "unconnected-(J1-P$2-Pad3)") (class "Default")
      (node (ref "J1") (pin "3") (pinfunction "P$2_3") (pintype "bidirectional"))
    )
    (net (code "539") (name "unconnected-(P4-Pad5)") (class "Default")
      (node (ref "P4") (pin "5") (pinfunction "5_5") (pintype "bidirectional"))
    )
    (net (code "540") (name "unconnected-(P4-Pad6)") (class "Default")
      (node (ref "P4") (pin "6") (pinfunction "6_6") (pintype "bidirectional"))
    )
    (net (code "541") (name "unconnected-(U1-N{slash}C-Pad3)") (class "Default")
      (node (ref "U1") (pin "3") (pinfunction "N/C_3") (pintype "bidirectional"))
    )
    (net (code "542") (name "unconnected-(U2-N{slash}C-Pad3)") (class "Default")
      (node (ref "U2") (pin "3") (pinfunction "N/C_3") (pintype "bidirectional"))
    )
    (net (code "543") (name "unconnected-(U3-N{slash}C-Pad3)") (class "Default")
      (node (ref "U3") (pin "3") (pinfunction "N/C_3") (pintype "bidirectional"))
    )
    (net (code "544") (name "unconnected-(U4-N{slash}C-Pad3)") (class "Default")
      (node (ref "U4") (pin "3") (pinfunction "N/C_3") (pintype "bidirectional"))
    )
  )
)
